# Sheet1.net
KiCad netlist of a schematic drawn in Altium Designer
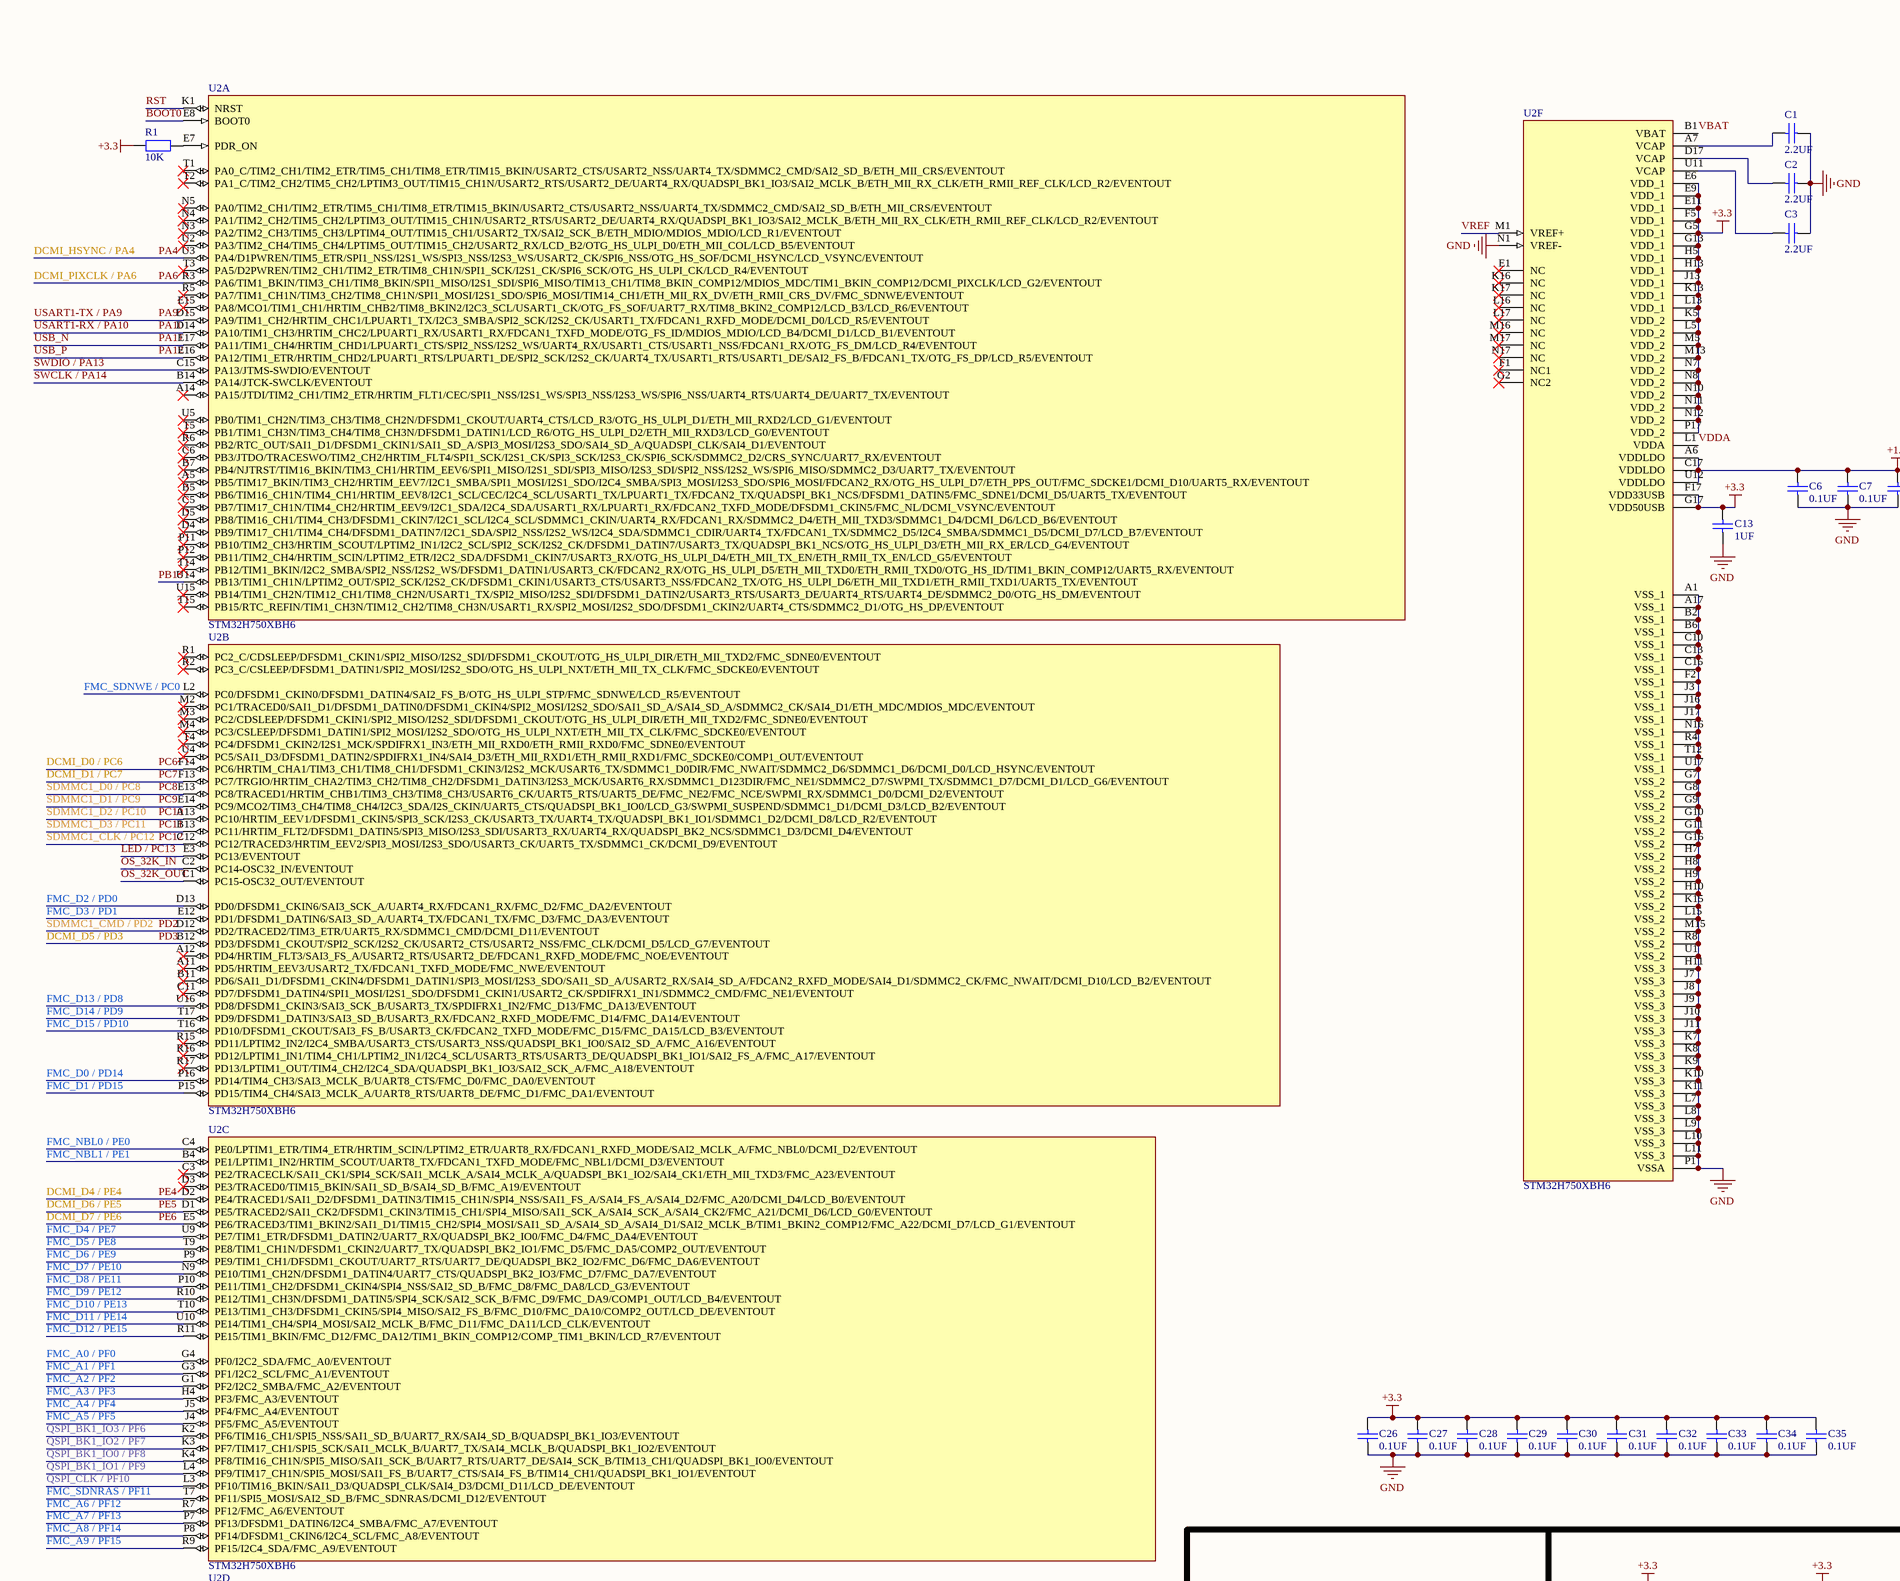
[diagram p0: Sheet1.SchDoc, top left]
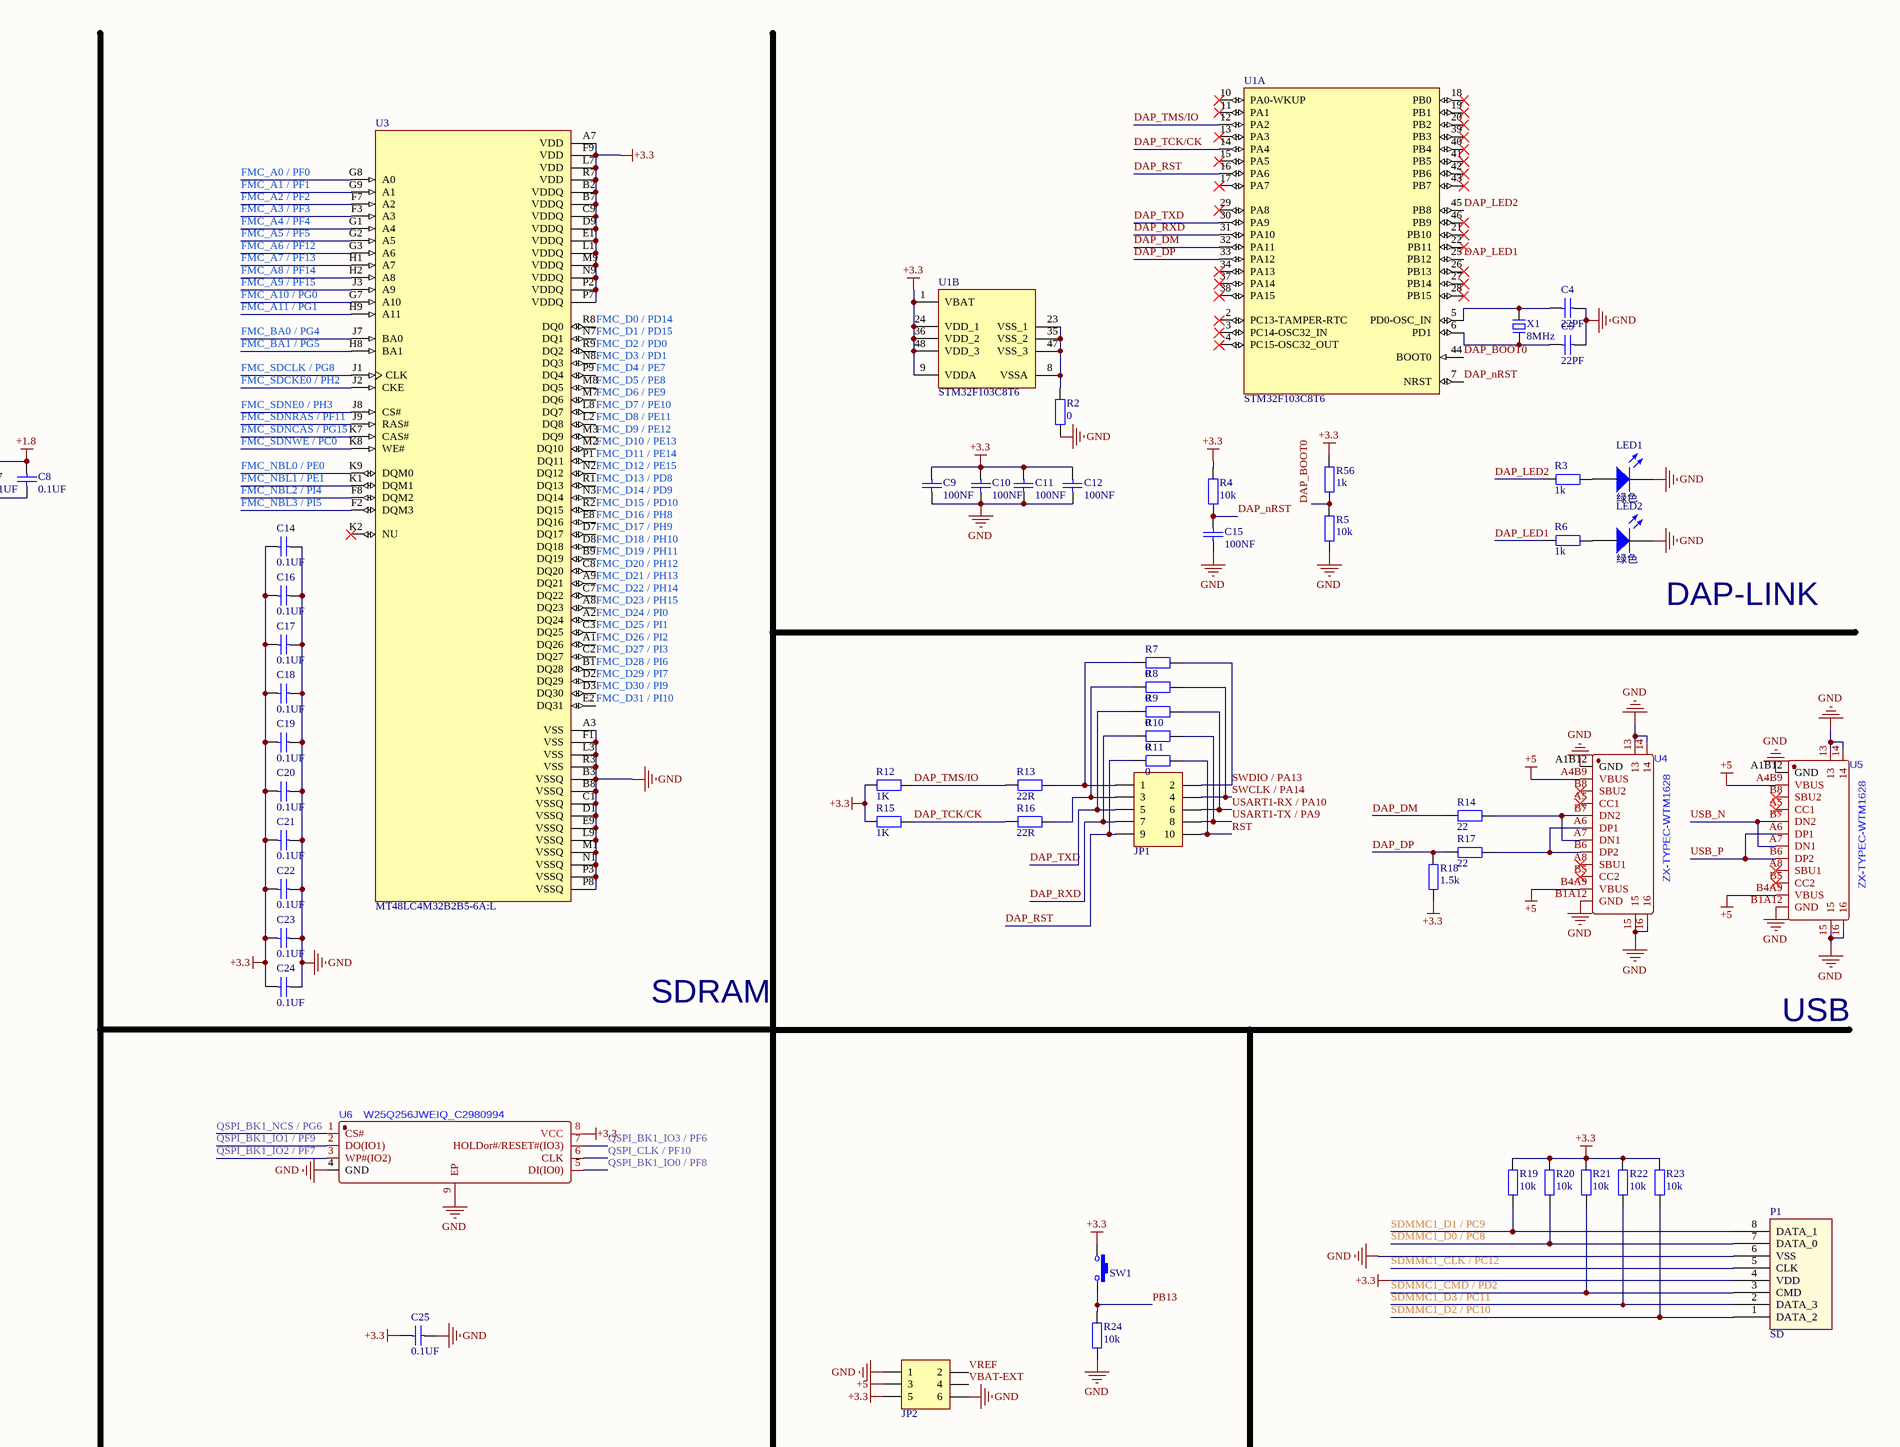
[diagram p1: Sheet1.SchDoc, top right]
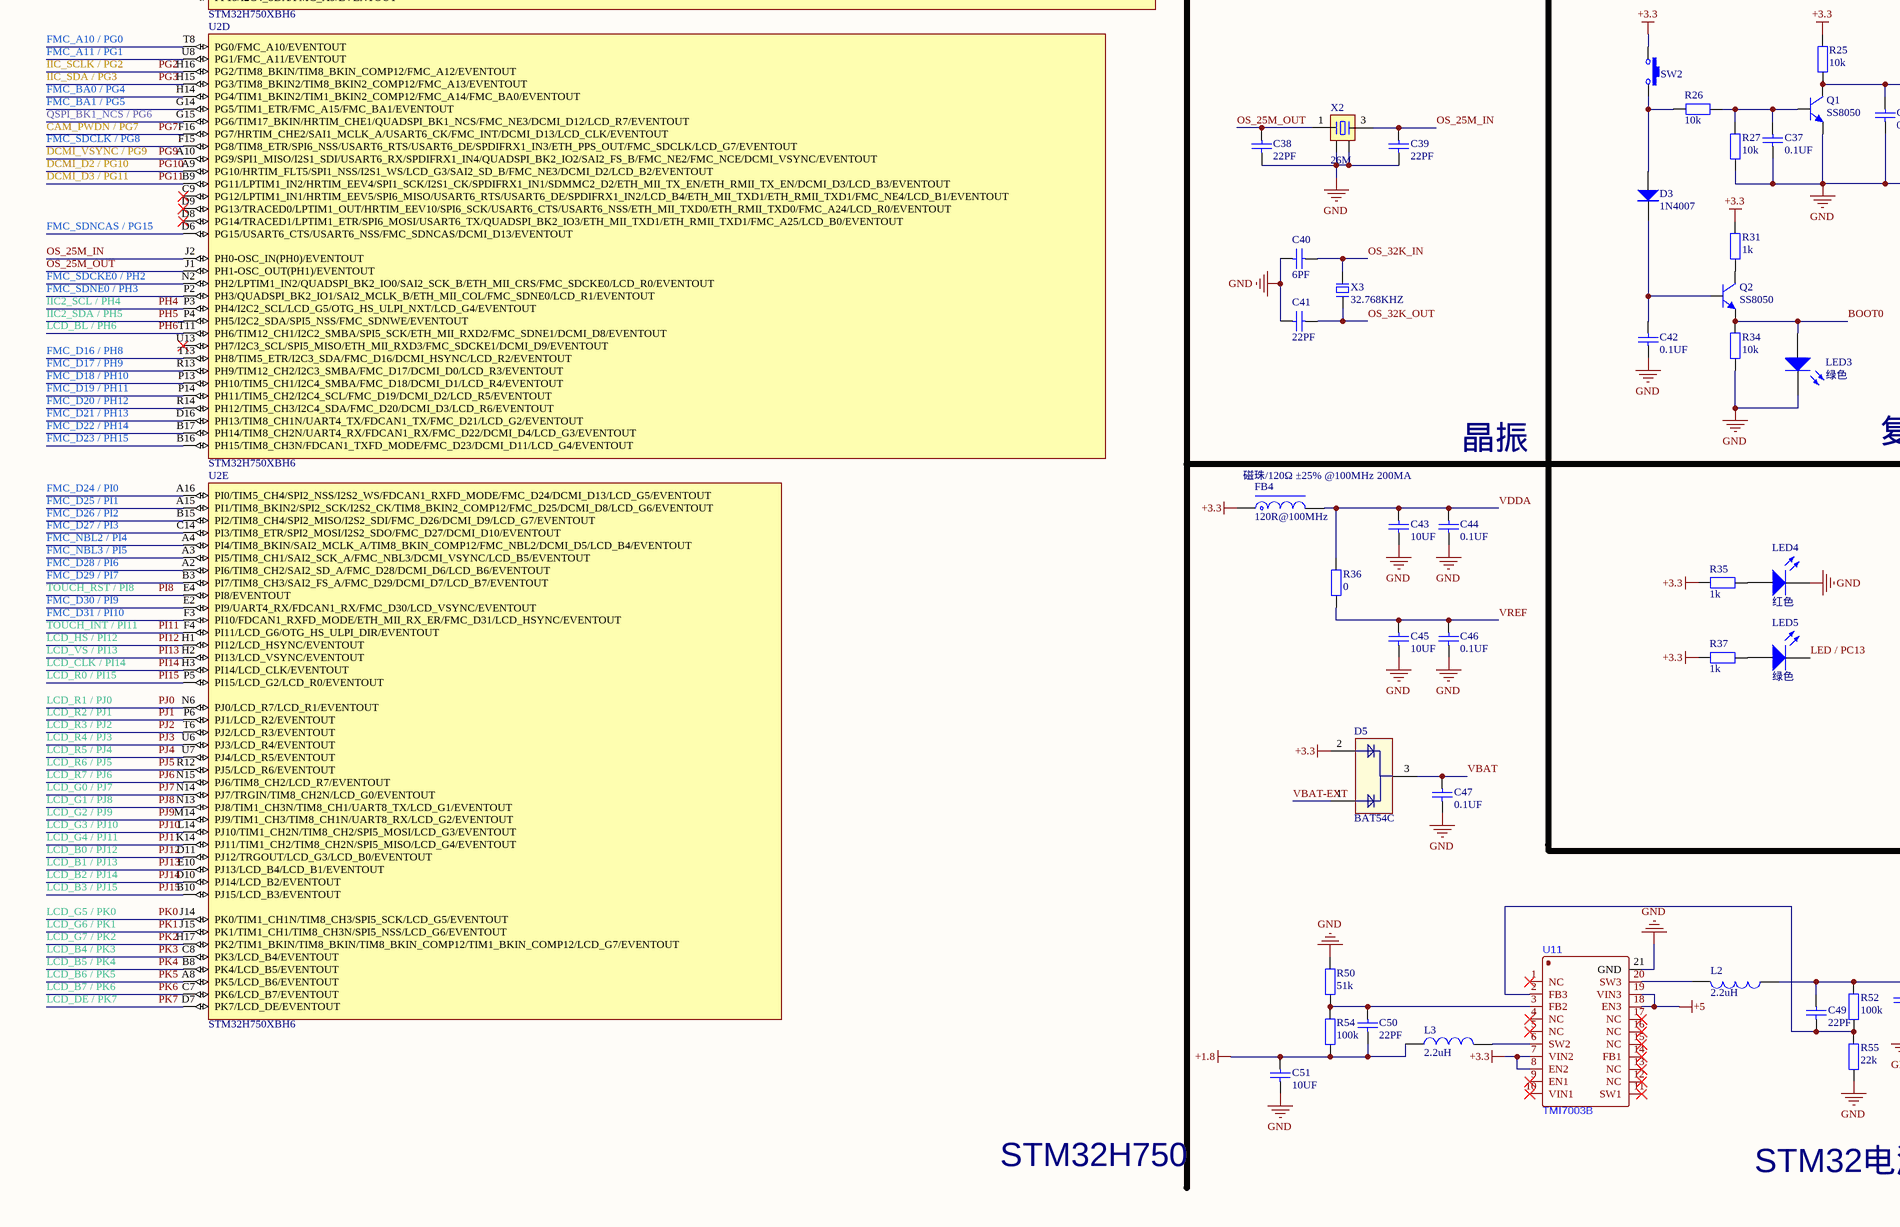
[diagram p2: Sheet1.SchDoc, bottom left]
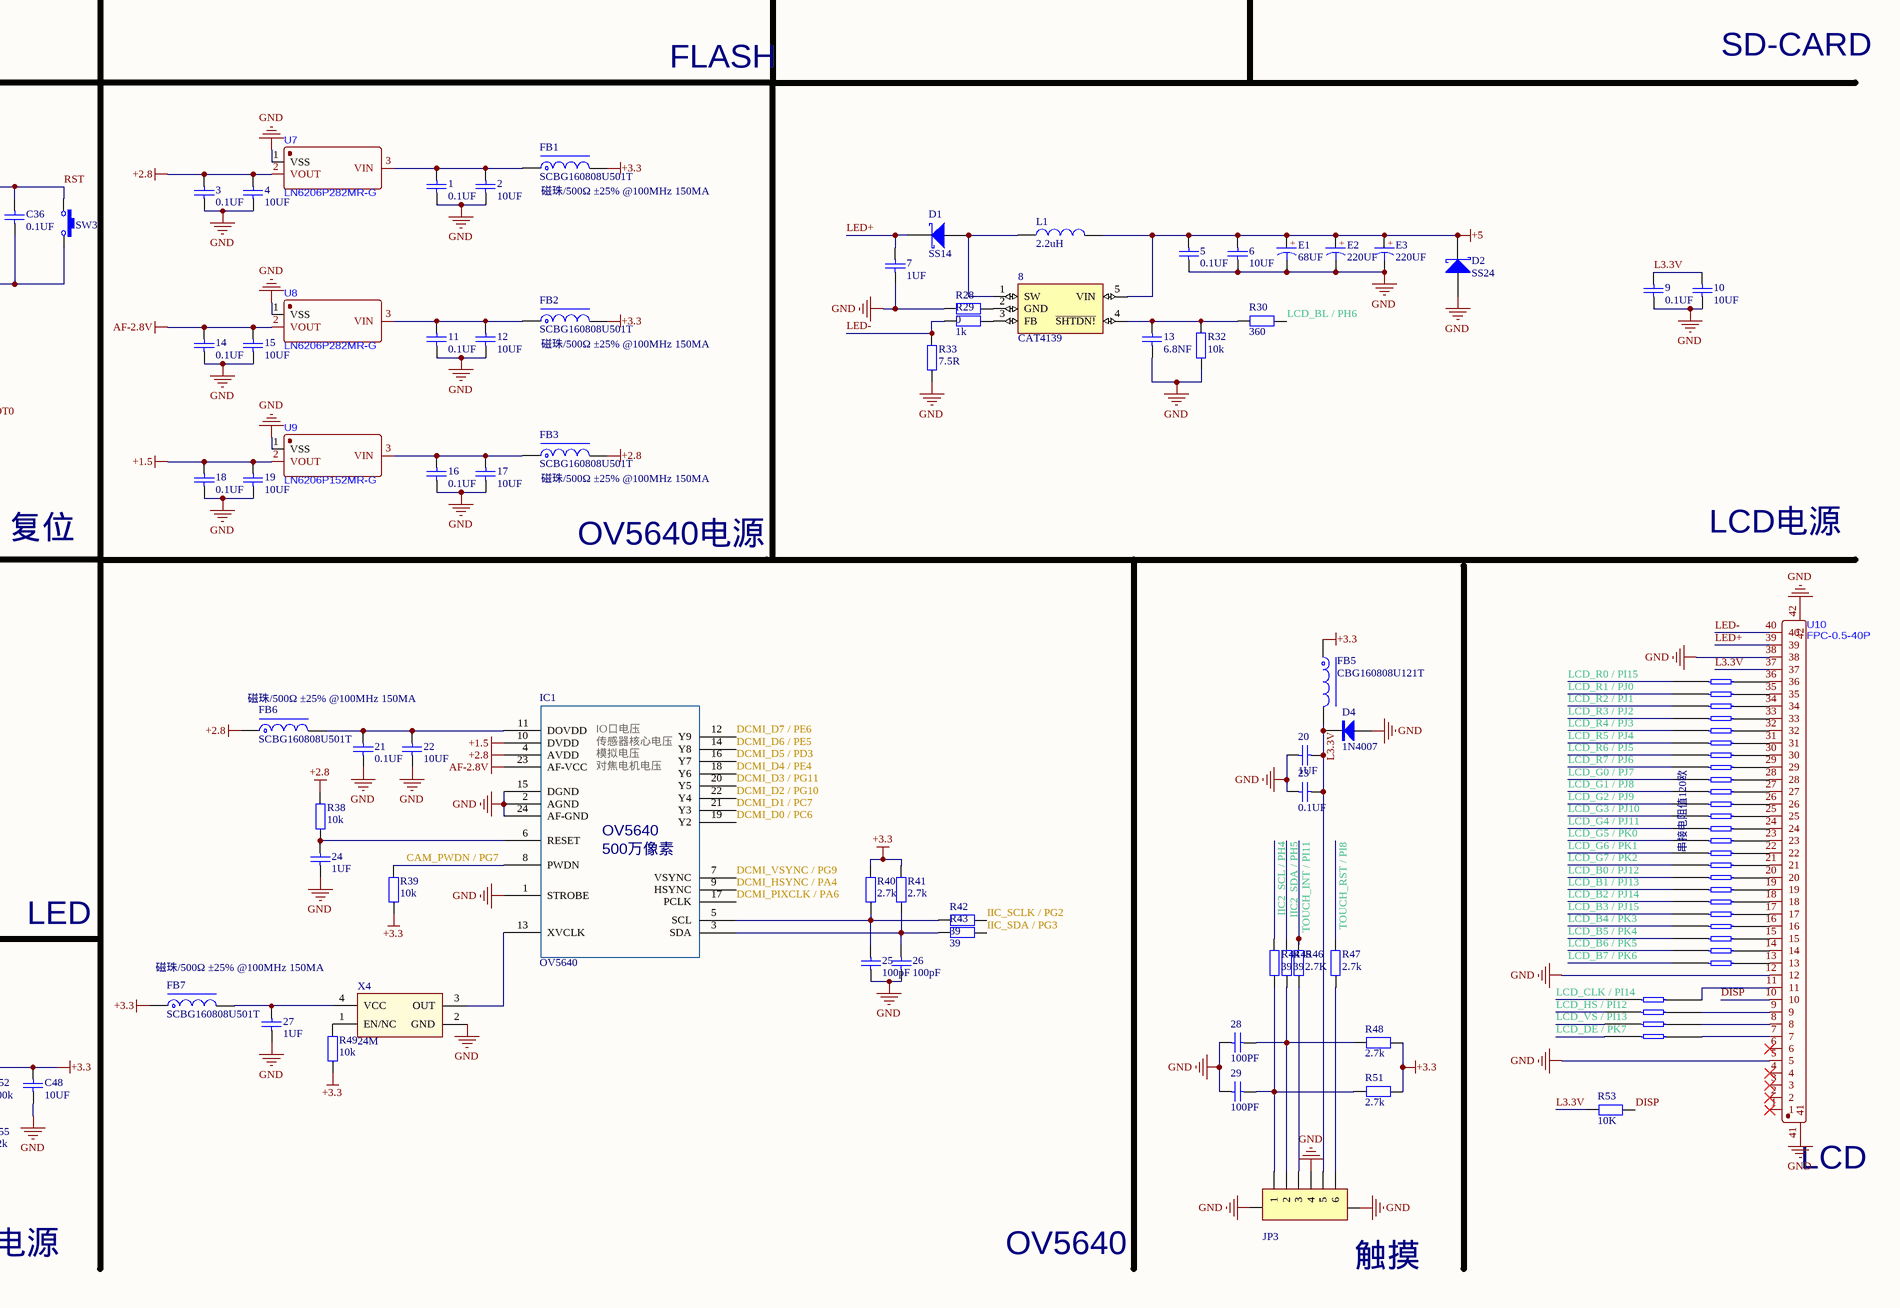
[diagram p3: Sheet1.SchDoc, bottom right]

(export (version "E")
  (design (tool "Eeschema 10.0.6"))
  (components
    (comp (ref "1")
      (value "0.1UF")
      (footprint "PCB1:C0603_L")
      (description "贴片电容/MLCC电容")
      (libsource (lib "屏幕一体板v2") (part "C"))
    )
    (comp (ref "2")
      (value "10UF")
      (footprint "PCB1:C0603_L")
      (description "贴片电容/MLCC电容")
      (libsource (lib "屏幕一体板v2") (part "C"))
    )
    (comp (ref "3")
      (value "0.1UF")
      (footprint "PCB1:C0603_L")
      (description "贴片电容/MLCC电容")
      (libsource (lib "屏幕一体板v2") (part "C"))
    )
    (comp (ref "4")
      (value "10UF")
      (footprint "PCB1:C0603_L")
      (description "贴片电容/MLCC电容")
      (libsource (lib "屏幕一体板v2") (part "C"))
    )
    (comp (ref "5")
      (value "0.1UF")
      (footprint "PCB1:C0603_L")
      (description "贴片电容/MLCC电容")
      (libsource (lib "屏幕一体板v2") (part "C"))
    )
    (comp (ref "6")
      (value "10UF")
      (footprint "PCB1:C0603_L")
      (description "贴片电容/MLCC电容")
      (libsource (lib "屏幕一体板v2") (part "C"))
    )
    (comp (ref "7")
      (value "1UF")
      (footprint "PCB1:C0603_L")
      (description "贴片电容/MLCC电容")
      (libsource (lib "屏幕一体板v2") (part "C"))
    )
    (comp (ref "8")
      (value "CAT4139")
      (footprint "PCB1:SOT-23(OT)5_LEAD")
      (libsource (lib "屏幕一体板v2") (part "CAT4139"))
    )
    (comp (ref "9")
      (value "0.1UF")
      (footprint "PCB1:C0603_L")
      (description "贴片电容/MLCC电容")
      (libsource (lib "屏幕一体板v2") (part "C"))
    )
    (comp (ref "10")
      (value "10UF")
      (footprint "PCB1:C0603_L")
      (description "贴片电容/MLCC电容")
      (libsource (lib "屏幕一体板v2") (part "C"))
    )
    (comp (ref "11")
      (value "0.1UF")
      (footprint "PCB1:C0603_L")
      (description "贴片电容/MLCC电容")
      (libsource (lib "屏幕一体板v2") (part "C"))
    )
    (comp (ref "12")
      (value "10UF")
      (footprint "PCB1:C0603_L")
      (description "贴片电容/MLCC电容")
      (libsource (lib "屏幕一体板v2") (part "C"))
    )
    (comp (ref "13")
      (value "6.8NF")
      (footprint "PCB1:C0603_L")
      (description "贴片电容/MLCC电容")
      (libsource (lib "屏幕一体板v2") (part "C"))
    )
    (comp (ref "14")
      (value "0.1UF")
      (footprint "PCB1:C0603_L")
      (description "贴片电容/MLCC电容")
      (libsource (lib "屏幕一体板v2") (part "C"))
    )
    (comp (ref "15")
      (value "10UF")
      (footprint "PCB1:C0603_L")
      (description "贴片电容/MLCC电容")
      (libsource (lib "屏幕一体板v2") (part "C"))
    )
    (comp (ref "16")
      (value "0.1UF")
      (footprint "PCB1:C0603_L")
      (description "贴片电容/MLCC电容")
      (libsource (lib "屏幕一体板v2") (part "C"))
    )
    (comp (ref "17")
      (value "10UF")
      (footprint "PCB1:C0603_L")
      (description "贴片电容/MLCC电容")
      (libsource (lib "屏幕一体板v2") (part "C"))
    )
    (comp (ref "18")
      (value "0.1UF")
      (footprint "PCB1:C0603_L")
      (description "贴片电容/MLCC电容")
      (libsource (lib "屏幕一体板v2") (part "C"))
    )
    (comp (ref "19")
      (value "10UF")
      (footprint "PCB1:C0603_L")
      (description "贴片电容/MLCC电容")
      (libsource (lib "屏幕一体板v2") (part "C"))
    )
    (comp (ref "20")
      (value "1UF")
      (footprint "PCB1:C0603_L")
      (description "贴片电容/MLCC电容")
      (libsource (lib "屏幕一体板v2") (part "C"))
    )
    (comp (ref "21")
      (value "0.1UF")
      (footprint "PCB1:C0603_L")
      (description "贴片电容/MLCC电容")
      (libsource (lib "屏幕一体板v2") (part "C"))
    )
    (comp (ref "22")
      (value "10UF")
      (footprint "PCB1:C0603_L")
      (description "贴片电容/MLCC电容")
      (libsource (lib "屏幕一体板v2") (part "C"))
    )
    (comp (ref "23")
      (value "0.1UF")
      (footprint "PCB1:C0603_L")
      (description "贴片电容/MLCC电容")
      (libsource (lib "屏幕一体板v2") (part "C"))
    )
    (comp (ref "24")
      (value "1UF")
      (footprint "PCB1:C0603_L")
      (description "贴片电容/MLCC电容")
      (libsource (lib "屏幕一体板v2") (part "C"))
    )
    (comp (ref "25")
      (value "100pF")
      (footprint "PCB1:C0603_L")
      (description "贴片电容/MLCC电容")
      (libsource (lib "屏幕一体板v2") (part "C"))
    )
    (comp (ref "26")
      (value "100pF")
      (footprint "PCB1:C0603_L")
      (description "贴片电容/MLCC电容")
      (libsource (lib "屏幕一体板v2") (part "C"))
    )
    (comp (ref "27")
      (value "1UF")
      (footprint "PCB1:C0603_L")
      (description "贴片电容/MLCC电容")
      (libsource (lib "屏幕一体板v2") (part "C"))
    )
    (comp (ref "28")
      (value "100PF")
      (footprint "PCB1:C0603_L")
      (description "贴片电容/MLCC电容")
      (libsource (lib "屏幕一体板v2") (part "C"))
    )
    (comp (ref "29")
      (value "100PF")
      (footprint "PCB1:C0603_L")
      (description "贴片电容/MLCC电容")
      (libsource (lib "屏幕一体板v2") (part "C"))
    )
    (comp (ref "C1")
      (value "2.2UF")
      (footprint "PCB1:C0603_L")
      (description "贴片电容/MLCC电容")
      (libsource (lib "屏幕一体板v2") (part "C"))
    )
    (comp (ref "C2")
      (value "2.2UF")
      (footprint "PCB1:C0603_L")
      (description "贴片电容/MLCC电容")
      (libsource (lib "屏幕一体板v2") (part "C"))
    )
    (comp (ref "C3")
      (value "2.2UF")
      (footprint "PCB1:C0603_L")
      (description "贴片电容/MLCC电容")
      (libsource (lib "屏幕一体板v2") (part "C"))
    )
    (comp (ref "C4")
      (value "22PF")
      (footprint "PCB1:C0603_L")
      (description "贴片电容/MLCC电容")
      (libsource (lib "屏幕一体板v2") (part "C"))
    )
    (comp (ref "C5")
      (value "22PF")
      (footprint "PCB1:C0603_L")
      (description "贴片电容/MLCC电容")
      (libsource (lib "屏幕一体板v2") (part "C"))
    )
    (comp (ref "C6")
      (value "0.1UF")
      (footprint "PCB1:C0603_L")
      (description "贴片电容/MLCC电容")
      (libsource (lib "屏幕一体板v2") (part "C"))
    )
    (comp (ref "C7")
      (value "0.1UF")
      (footprint "PCB1:C0603_L")
      (description "贴片电容/MLCC电容")
      (libsource (lib "屏幕一体板v2") (part "C"))
    )
    (comp (ref "C8")
      (value "0.1UF")
      (footprint "PCB1:C0603_L")
      (description "贴片电容/MLCC电容")
      (libsource (lib "屏幕一体板v2") (part "C"))
    )
    (comp (ref "C9")
      (value "100NF")
      (footprint "PCB1:C0603_L")
      (description "贴片电容/MLCC电容")
      (libsource (lib "屏幕一体板v2") (part "C"))
    )
    (comp (ref "C10")
      (value "100NF")
      (footprint "PCB1:C0603_L")
      (description "贴片电容/MLCC电容")
      (libsource (lib "屏幕一体板v2") (part "C"))
    )
    (comp (ref "C11")
      (value "100NF")
      (footprint "PCB1:C0603_L")
      (description "贴片电容/MLCC电容")
      (libsource (lib "屏幕一体板v2") (part "C"))
    )
    (comp (ref "C12")
      (value "100NF")
      (footprint "PCB1:C0603_L")
      (description "贴片电容/MLCC电容")
      (libsource (lib "屏幕一体板v2") (part "C"))
    )
    (comp (ref "C13")
      (value "1UF")
      (footprint "PCB1:C0603_L")
      (description "贴片电容/MLCC电容")
      (libsource (lib "屏幕一体板v2") (part "C"))
    )
    (comp (ref "C14")
      (value "0.1UF")
      (footprint "PCB1:C0402_M")
      (description "贴片电容/MLCC电容")
      (libsource (lib "屏幕一体板v2") (part "C"))
    )
    (comp (ref "C15")
      (value "100NF")
      (footprint "PCB1:C0603_L")
      (description "贴片电容/MLCC电容")
      (libsource (lib "屏幕一体板v2") (part "C"))
    )
    (comp (ref "C16")
      (value "0.1UF")
      (footprint "PCB1:C0402_M")
      (description "贴片电容/MLCC电容")
      (libsource (lib "屏幕一体板v2") (part "C"))
    )
    (comp (ref "C17")
      (value "0.1UF")
      (footprint "PCB1:C0402_M")
      (description "贴片电容/MLCC电容")
      (libsource (lib "屏幕一体板v2") (part "C"))
    )
    (comp (ref "C18")
      (value "0.1UF")
      (footprint "PCB1:C0402_M")
      (description "贴片电容/MLCC电容")
      (libsource (lib "屏幕一体板v2") (part "C"))
    )
    (comp (ref "C19")
      (value "0.1UF")
      (footprint "PCB1:C0402_M")
      (description "贴片电容/MLCC电容")
      (libsource (lib "屏幕一体板v2") (part "C"))
    )
    (comp (ref "C20")
      (value "0.1UF")
      (footprint "PCB1:C0402_M")
      (description "贴片电容/MLCC电容")
      (libsource (lib "屏幕一体板v2") (part "C"))
    )
    (comp (ref "C21")
      (value "0.1UF")
      (footprint "PCB1:C0402_M")
      (description "贴片电容/MLCC电容")
      (libsource (lib "屏幕一体板v2") (part "C"))
    )
    (comp (ref "C22")
      (value "0.1UF")
      (footprint "PCB1:C0402_M")
      (description "贴片电容/MLCC电容")
      (libsource (lib "屏幕一体板v2") (part "C"))
    )
    (comp (ref "C23")
      (value "0.1UF")
      (footprint "PCB1:C0402_M")
      (description "贴片电容/MLCC电容")
      (libsource (lib "屏幕一体板v2") (part "C"))
    )
    (comp (ref "C24")
      (value "0.1UF")
      (footprint "PCB1:C0402_M")
      (description "贴片电容/MLCC电容")
      (libsource (lib "屏幕一体板v2") (part "C"))
    )
    (comp (ref "C25")
      (value "0.1UF")
      (footprint "PCB1:C0603_L")
      (description "贴片电容/MLCC电容")
      (libsource (lib "屏幕一体板v2") (part "C"))
    )
    (comp (ref "C26")
      (value "0.1UF")
      (footprint "PCB1:C0402_M")
      (description "贴片电容/MLCC电容")
      (libsource (lib "屏幕一体板v2") (part "C"))
    )
    (comp (ref "C27")
      (value "0.1UF")
      (footprint "PCB1:C0402_M")
      (description "贴片电容/MLCC电容")
      (libsource (lib "屏幕一体板v2") (part "C"))
    )
    (comp (ref "C28")
      (value "0.1UF")
      (footprint "PCB1:C0603_L")
      (description "贴片电容/MLCC电容")
      (libsource (lib "屏幕一体板v2") (part "C"))
    )
    (comp (ref "C29")
      (value "0.1UF")
      (footprint "PCB1:C0402_M")
      (description "贴片电容/MLCC电容")
      (libsource (lib "屏幕一体板v2") (part "C"))
    )
    (comp (ref "C30")
      (value "0.1UF")
      (footprint "PCB1:C0402_M")
      (description "贴片电容/MLCC电容")
      (libsource (lib "屏幕一体板v2") (part "C"))
    )
    (comp (ref "C31")
      (value "0.1UF")
      (footprint "PCB1:C0402_M")
      (description "贴片电容/MLCC电容")
      (libsource (lib "屏幕一体板v2") (part "C"))
    )
    (comp (ref "C32")
      (value "0.1UF")
      (footprint "PCB1:C0402_M")
      (description "贴片电容/MLCC电容")
      (libsource (lib "屏幕一体板v2") (part "C"))
    )
    (comp (ref "C33")
      (value "0.1UF")
      (footprint "PCB1:C0402_M")
      (description "贴片电容/MLCC电容")
      (libsource (lib "屏幕一体板v2") (part "C"))
    )
    (comp (ref "C34")
      (value "0.1UF")
      (footprint "PCB1:C0402_M")
      (description "贴片电容/MLCC电容")
      (libsource (lib "屏幕一体板v2") (part "C"))
    )
    (comp (ref "C35")
      (value "0.1UF")
      (footprint "PCB1:C0402_M")
      (description "贴片电容/MLCC电容")
      (libsource (lib "屏幕一体板v2") (part "C"))
    )
    (comp (ref "C36")
      (value "0.1UF")
      (footprint "PCB1:C0603_L")
      (description "贴片电容/MLCC电容")
      (libsource (lib "屏幕一体板v2") (part "C"))
    )
    (comp (ref "C37")
      (value "0.1UF")
      (footprint "PCB1:C0603_L")
      (description "贴片电容/MLCC电容")
      (libsource (lib "屏幕一体板v2") (part "C"))
    )
    (comp (ref "C38")
      (value "22PF")
      (footprint "PCB1:C0603_L")
      (description "贴片电容/MLCC电容")
      (libsource (lib "屏幕一体板v2") (part "C"))
    )
    (comp (ref "C39")
      (value "22PF")
      (footprint "PCB1:C0603_L")
      (description "贴片电容/MLCC电容")
      (libsource (lib "屏幕一体板v2") (part "C"))
    )
    (comp (ref "C40")
      (value "6PF")
      (footprint "PCB1:C0603_L")
      (description "贴片电容/MLCC电容")
      (libsource (lib "屏幕一体板v2") (part "C"))
    )
    (comp (ref "C41")
      (value "22PF")
      (footprint "PCB1:C0603_L")
      (description "贴片电容/MLCC电容")
      (libsource (lib "屏幕一体板v2") (part "C"))
    )
    (comp (ref "C42")
      (value "0.1UF")
      (footprint "PCB1:C0603_L")
      (description "贴片电容/MLCC电容")
      (libsource (lib "屏幕一体板v2") (part "C"))
    )
    (comp (ref "C43")
      (value "10UF")
      (footprint "PCB1:C0603_L")
      (description "贴片电容/MLCC电容")
      (libsource (lib "屏幕一体板v2") (part "C"))
    )
    (comp (ref "C44")
      (value "0.1UF")
      (footprint "PCB1:C0603_L")
      (description "贴片电容/MLCC电容")
      (libsource (lib "屏幕一体板v2") (part "C"))
    )
    (comp (ref "C45")
      (value "10UF")
      (footprint "PCB1:C0603_L")
      (description "贴片电容/MLCC电容")
      (libsource (lib "屏幕一体板v2") (part "C"))
    )
    (comp (ref "C46")
      (value "0.1UF")
      (footprint "PCB1:C0603_L")
      (description "贴片电容/MLCC电容")
      (libsource (lib "屏幕一体板v2") (part "C"))
    )
    (comp (ref "C47")
      (value "0.1UF")
      (footprint "PCB1:C0603_L")
      (description "贴片电容/MLCC电容")
      (libsource (lib "屏幕一体板v2") (part "C"))
    )
    (comp (ref "C48")
      (value "10UF")
      (footprint "PCB1:C0603_L")
      (description "贴片电容/MLCC电容")
      (libsource (lib "屏幕一体板v2") (part "C"))
    )
    (comp (ref "C49")
      (value "22PF")
      (footprint "PCB1:C0603_L")
      (description "贴片电容/MLCC电容")
      (libsource (lib "屏幕一体板v2") (part "C"))
    )
    (comp (ref "C50")
      (value "22PF")
      (footprint "PCB1:C0603_L")
      (description "贴片电容/MLCC电容")
      (libsource (lib "屏幕一体板v2") (part "C"))
    )
    (comp (ref "C51")
      (value "10UF")
      (footprint "PCB1:C0603_L")
      (description "贴片电容/MLCC电容")
      (libsource (lib "屏幕一体板v2") (part "C"))
    )
    (comp (ref "D1")
      (value "SS14")
      (footprint "PCB1:SMA")
      (description "肖特基二极管")
      (libsource (lib "屏幕一体板v2") (part "SS14"))
    )
    (comp (ref "D2")
      (value "SS24")
      (footprint "PCB1:SMA")
      (description "肖特基二极管")
      (libsource (lib "屏幕一体板v2") (part "SS14"))
    )
    (comp (ref "D3")
      (value "1N4007")
      (footprint "PCB1:SMA")
      (description "整流二极管")
      (libsource (lib "屏幕一体板v2") (part "1N4007"))
    )
    (comp (ref "D4")
      (value "1N4007")
      (footprint "PCB1:SMA")
      (description "整流二极管")
      (libsource (lib "屏幕一体板v2") (part "1N4007"))
    )
    (comp (ref "D5")
      (value "BAT54C")
      (footprint "PCB1:SOT23-3N")
      (description "两路肖特基二极管")
      (libsource (lib "屏幕一体板v2") (part "BAT54C"))
    )
    (comp (ref "E1")
      (value "68UF")
      (footprint "PCB1:CE A(3*5.4)")
      (description "贴片电解电容")
      (libsource (lib "屏幕一体板v2") (part "CE_SMD"))
    )
    (comp (ref "E2")
      (value "220UF")
      (footprint "PCB1:CE A(3*5.4)")
      (description "贴片电解电容")
      (libsource (lib "屏幕一体板v2") (part "CE_SMD"))
    )
    (comp (ref "E3")
      (value "220UF")
      (footprint "PCB1:CE A(3*5.4)")
      (description "贴片电解电容")
      (libsource (lib "屏幕一体板v2") (part "CE_SMD"))
    )
    (comp (ref "FB1")
      (value "SCBG160808U501T")
      (footprint "PCB1:FB0603")
      (description "贴片磁珠")
      (libsource (lib "屏幕一体板v2") (part "FB"))
    )
    (comp (ref "FB2")
      (value "SCBG160808U501T")
      (footprint "PCB1:FB0603")
      (description "贴片磁珠")
      (libsource (lib "屏幕一体板v2") (part "FB"))
    )
    (comp (ref "FB3")
      (value "SCBG160808U501T")
      (footprint "PCB1:FB0603")
      (description "贴片磁珠")
      (libsource (lib "屏幕一体板v2") (part "FB"))
    )
    (comp (ref "FB4")
      (value "120R@100MHz")
      (footprint "PCB1:FB0603")
      (description "贴片磁珠")
      (libsource (lib "屏幕一体板v2") (part "FB"))
    )
    (comp (ref "FB5")
      (value "CBG160808U121T")
      (footprint "PCB1:FB0805")
      (description "贴片磁珠")
      (libsource (lib "") (part "FB_1"))
    )
    (comp (ref "FB6")
      (value "SCBG160808U501T")
      (footprint "PCB1:FB0603")
      (description "贴片磁珠")
      (libsource (lib "屏幕一体板v2") (part "FB"))
    )
    (comp (ref "FB7")
      (value "SCBG160808U501T")
      (footprint "PCB1:FB0603")
      (description "贴片磁珠")
      (libsource (lib "屏幕一体板v2") (part "FB"))
    )
    (comp (ref "IC1") (value "OV5640") (footprint "PCB1:OV2640") (libsource (lib "屏幕一体板v2") (part "OV5640")))
    (comp (ref "JP1")
      (value "Header 5X2")
      (footprint "PCB1:HDR2.54-M-LS-2x5P")
      (description "5*2P接插件")
      (libsource (lib "屏幕一体板v2") (part "Header 5X2"))
    )
    (comp (ref "JP2")
      (value "Header3X2")
      (footprint "PCB1:HDR2.54-M-LS-2x3P")
      (description "3*2P接插件")
      (libsource (lib "屏幕一体板v2") (part "Header 3X2"))
    )
    (comp (ref "JP3")
      (value "CON-6P")
      (footprint "PCB1:FPC0.5-WT-6P")
      (description "6P连接器")
      (libsource (lib "屏幕一体板v2") (part "Header 6"))
    )
    (comp (ref "L1")
      (value "2.2uH")
      (footprint "PCB1:L0805")
      (description "贴片小功率电感")
      (libsource (lib "屏幕一体板v2") (part "L"))
    )
    (comp (ref "L2")
      (value "2.2uH")
      (footprint "PCB1:L0805")
      (description "贴片小功率电感")
      (libsource (lib "屏幕一体板v2") (part "L"))
    )
    (comp (ref "L3")
      (value "2.2uH")
      (footprint "PCB1:L0805")
      (description "贴片小功率电感")
      (libsource (lib "屏幕一体板v2") (part "L"))
    )
    (comp (ref "LED1")
      (value "绿色")
      (footprint "PCB1:LED0805_G")
      (description "贴片LED")
      (libsource (lib "屏幕一体板v2") (part "LED"))
    )
    (comp (ref "LED2")
      (value "绿色")
      (footprint "PCB1:LED0805_G")
      (description "贴片LED")
      (libsource (lib "屏幕一体板v2") (part "LED"))
    )
    (comp (ref "LED3")
      (value "绿色")
      (footprint "PCB1:LED0805_G")
      (description "贴片LED")
      (libsource (lib "屏幕一体板v2") (part "LED"))
    )
    (comp (ref "LED4")
      (value "红色")
      (footprint "PCB1:LED0603_R")
      (description "贴片LED")
      (libsource (lib "屏幕一体板v2") (part "LED"))
    )
    (comp (ref "LED5")
      (value "绿色")
      (footprint "PCB1:LED0805_G")
      (description "贴片LED")
      (libsource (lib "屏幕一体板v2") (part "LED"))
    )
    (comp (ref "P1")
      (value "SD")
      (footprint "PCB1:MICRO SD")
      (description "自弹式TF卡座")
      (libsource (lib "屏幕一体板v2") (part "Micro SD_SD"))
    )
    (comp (ref "Q1")
      (value "SS8050")
      (footprint "PCB1:SOT23-3N")
      (description "高频放大-NPN型")
      (libsource (lib "屏幕一体板v2") (part "8050-SMD"))
    )
    (comp (ref "Q2")
      (value "SS8050")
      (footprint "PCB1:SOT23-3N")
      (description "高频放大-NPN型")
      (libsource (lib "屏幕一体板v2") (part "8050-SMD"))
    )
    (comp (ref "R1")
      (value "10K")
      (footprint "PCB1:R0603_L")
      (description "贴片电阻")
      (libsource (lib "屏幕一体板v2") (part "R"))
    )
    (comp (ref "R2")
      (value "0")
      (footprint "PCB1:R0603_L")
      (description "贴片电阻")
      (libsource (lib "屏幕一体板v2") (part "R"))
    )
    (comp (ref "R3")
      (value "1k")
      (footprint "PCB1:R0603_L")
      (description "贴片电阻")
      (libsource (lib "屏幕一体板v2") (part "R"))
    )
    (comp (ref "R4")
      (value "10k")
      (footprint "PCB1:R0603_L")
      (description "贴片电阻")
      (libsource (lib "屏幕一体板v2") (part "R"))
    )
    (comp (ref "R5")
      (value "10k")
      (footprint "PCB1:R0603_L")
      (description "贴片电阻")
      (libsource (lib "屏幕一体板v2") (part "R"))
    )
    (comp (ref "R6")
      (value "1k")
      (footprint "PCB1:R0603_L")
      (description "贴片电阻")
      (libsource (lib "屏幕一体板v2") (part "R"))
    )
    (comp (ref "R7")
      (value "0")
      (footprint "PCB1:R0603_L")
      (description "贴片电阻")
      (libsource (lib "屏幕一体板v2") (part "R"))
    )
    (comp (ref "R8")
      (value "0")
      (footprint "PCB1:R0603_L")
      (description "贴片电阻")
      (libsource (lib "屏幕一体板v2") (part "R"))
    )
    (comp (ref "R9")
      (value "0")
      (footprint "PCB1:R0603_L")
      (description "贴片电阻")
      (libsource (lib "屏幕一体板v2") (part "R"))
    )
    (comp (ref "R10")
      (value "0")
      (footprint "PCB1:R0603_L")
      (description "贴片电阻")
      (libsource (lib "屏幕一体板v2") (part "R"))
    )
    (comp (ref "R11")
      (value "0")
      (footprint "PCB1:R0603_L")
      (description "贴片电阻")
      (libsource (lib "屏幕一体板v2") (part "R"))
    )
    (comp (ref "R12")
      (value "1K")
      (footprint "PCB1:R0805_L")
      (description "贴片电阻")
      (libsource (lib "屏幕一体板v2") (part "R"))
    )
    (comp (ref "R13")
      (value "22R")
      (footprint "PCB1:R0805_L")
      (description "贴片电阻")
      (libsource (lib "屏幕一体板v2") (part "R"))
    )
    (comp (ref "R14")
      (value "22")
      (footprint "PCB1:R0603_L")
      (description "贴片电阻")
      (libsource (lib "屏幕一体板v2") (part "R"))
    )
    (comp (ref "R15")
      (value "1K")
      (footprint "PCB1:R0805_L")
      (description "贴片电阻")
      (libsource (lib "屏幕一体板v2") (part "R"))
    )
    (comp (ref "R16")
      (value "22R")
      (footprint "PCB1:R0805_L")
      (description "贴片电阻")
      (libsource (lib "屏幕一体板v2") (part "R"))
    )
    (comp (ref "R17")
      (value "22")
      (footprint "PCB1:R0603_L")
      (description "贴片电阻")
      (libsource (lib "屏幕一体板v2") (part "R"))
    )
    (comp (ref "R18")
      (value "1.5k")
      (footprint "PCB1:R0603_L")
      (description "贴片电阻")
      (libsource (lib "屏幕一体板v2") (part "R"))
    )
    (comp (ref "R19")
      (value "10k")
      (footprint "PCB1:R0603_L")
      (description "贴片电阻")
      (libsource (lib "屏幕一体板v2") (part "R"))
    )
    (comp (ref "R20")
      (value "10k")
      (footprint "PCB1:R0603_L")
      (description "贴片电阻")
      (libsource (lib "屏幕一体板v2") (part "R"))
    )
    (comp (ref "R21")
      (value "10k")
      (footprint "PCB1:R0603_L")
      (description "贴片电阻")
      (libsource (lib "屏幕一体板v2") (part "R"))
    )
    (comp (ref "R22")
      (value "10k")
      (footprint "PCB1:R0603_L")
      (description "贴片电阻")
      (libsource (lib "屏幕一体板v2") (part "R"))
    )
    (comp (ref "R23")
      (value "10k")
      (footprint "PCB1:R0603_L")
      (description "贴片电阻")
      (libsource (lib "屏幕一体板v2") (part "R"))
    )
    (comp (ref "R24")
      (value "10k")
      (footprint "PCB1:R0603_L")
      (description "贴片电阻")
      (libsource (lib "屏幕一体板v2") (part "R"))
    )
    (comp (ref "R25")
      (value "10k")
      (footprint "PCB1:R0603_L")
      (description "贴片电阻")
      (libsource (lib "屏幕一体板v2") (part "R"))
    )
    (comp (ref "R26")
      (value "10k")
      (footprint "PCB1:R0603_L")
      (description "贴片电阻")
      (libsource (lib "屏幕一体板v2") (part "R"))
    )
    (comp (ref "R27")
      (value "10k")
      (footprint "PCB1:R0603_L")
      (description "贴片电阻")
      (libsource (lib "屏幕一体板v2") (part "R"))
    )
    (comp (ref "R28")
      (value "0")
      (footprint "PCB1:R0603_L")
      (description "贴片电阻")
      (libsource (lib "屏幕一体板v2") (part "R"))
    )
    (comp (ref "R29")
      (value "1k")
      (footprint "PCB1:R0603_L")
      (description "贴片电阻")
      (libsource (lib "屏幕一体板v2") (part "R"))
    )
    (comp (ref "R30")
      (value "360")
      (footprint "PCB1:R0603_L")
      (description "贴片电阻")
      (libsource (lib "屏幕一体板v2") (part "R"))
    )
    (comp (ref "R31")
      (value "1k")
      (footprint "PCB1:R0603_L")
      (description "贴片电阻")
      (libsource (lib "屏幕一体板v2") (part "R"))
    )
    (comp (ref "R32")
      (value "10k")
      (footprint "PCB1:R0603_L")
      (description "贴片电阻")
      (libsource (lib "屏幕一体板v2") (part "R"))
    )
    (comp (ref "R33")
      (value "7.5R")
      (footprint "PCB1:R0603_L")
      (description "贴片电阻")
      (libsource (lib "屏幕一体板v2") (part "R"))
    )
    (comp (ref "R34")
      (value "10k")
      (footprint "PCB1:R0603_L")
      (description "贴片电阻")
      (libsource (lib "屏幕一体板v2") (part "R"))
    )
    (comp (ref "R35")
      (value "1k")
      (footprint "PCB1:R0603_L")
      (description "贴片电阻")
      (libsource (lib "屏幕一体板v2") (part "R"))
    )
    (comp (ref "R36")
      (value "0")
      (footprint "PCB1:R0603_L")
      (description "贴片电阻")
      (libsource (lib "屏幕一体板v2") (part "R"))
    )
    (comp (ref "R37")
      (value "1k")
      (footprint "PCB1:R0603_L")
      (description "贴片电阻")
      (libsource (lib "屏幕一体板v2") (part "R"))
    )
    (comp (ref "R38")
      (value "10k")
      (footprint "PCB1:R0603_L")
      (description "贴片电阻")
      (libsource (lib "屏幕一体板v2") (part "R"))
    )
    (comp (ref "R39")
      (value "10k")
      (footprint "PCB1:R0603_L")
      (description "贴片电阻")
      (libsource (lib "屏幕一体板v2") (part "R"))
    )
    (comp (ref "R40")
      (value "2.7k")
      (footprint "PCB1:R0603_L")
      (description "贴片电阻")
      (libsource (lib "屏幕一体板v2") (part "R"))
    )
    (comp (ref "R41")
      (value "2.7k")
      (footprint "PCB1:R0603_L")
      (description "贴片电阻")
      (libsource (lib "屏幕一体板v2") (part "R"))
    )
    (comp (ref "R42")
      (value "39")
      (footprint "PCB1:R0603_L")
      (description "贴片电阻")
      (libsource (lib "屏幕一体板v2") (part "R"))
    )
    (comp (ref "R43")
      (value "39")
      (footprint "PCB1:R0603_L")
      (description "贴片电阻")
      (libsource (lib "屏幕一体板v2") (part "R"))
    )
    (comp (ref "R44")
      (value "39")
      (footprint "PCB1:R0603_L")
      (description "贴片电阻")
      (libsource (lib "屏幕一体板v2") (part "R"))
    )
    (comp (ref "R45")
      (value "39")
      (footprint "PCB1:R0603_L")
      (description "贴片电阻")
      (libsource (lib "屏幕一体板v2") (part "R"))
    )
    (comp (ref "R46")
      (value "2.7K")
      (footprint "PCB1:R0603_L")
      (description "贴片电阻")
      (libsource (lib "屏幕一体板v2") (part "R"))
    )
    (comp (ref "R47")
      (value "2.7k")
      (footprint "PCB1:R0603_L")
      (description "贴片电阻")
      (libsource (lib "屏幕一体板v2") (part "R"))
    )
    (comp (ref "R48")
      (value "2.7k")
      (footprint "PCB1:R0603_L")
      (description "贴片电阻")
      (libsource (lib "屏幕一体板v2") (part "R"))
    )
    (comp (ref "R49")
      (value "10k")
      (footprint "PCB1:R0603_L")
      (description "贴片电阻")
      (libsource (lib "屏幕一体板v2") (part "R"))
    )
    (comp (ref "R50")
      (value "51k")
      (footprint "PCB1:R0603_L")
      (description "贴片电阻")
      (libsource (lib "屏幕一体板v2") (part "R"))
    )
    (comp (ref "R51")
      (value "2.7k")
      (footprint "PCB1:R0603_L")
      (description "贴片电阻")
      (libsource (lib "屏幕一体板v2") (part "R"))
    )
    (comp (ref "R52")
      (value "100k")
      (footprint "PCB1:R0603_L")
      (description "贴片电阻")
      (libsource (lib "屏幕一体板v2") (part "R"))
    )
    (comp (ref "R53")
      (value "10K")
      (footprint "PCB1:R0603_L")
      (description "贴片电阻")
      (libsource (lib "屏幕一体板v2") (part "R"))
    )
    (comp (ref "R54")
      (value "100k")
      (footprint "PCB1:R0603_L")
      (description "贴片电阻")
      (libsource (lib "屏幕一体板v2") (part "R"))
    )
    (comp (ref "R55")
      (value "22k")
      (footprint "PCB1:R0603_L")
      (description "贴片电阻")
      (libsource (lib "屏幕一体板v2") (part "R"))
    )
    (comp (ref "R56")
      (value "1k")
      (footprint "PCB1:R0603_L")
      (description "贴片电阻")
      (libsource (lib "屏幕一体板v2") (part "R"))
    )
    (comp (ref "RP1") (value "120R排阻") (footprint "PCB1:0603_4P") (libsource (lib "屏幕一体板v2") (part "RES_4P")))
    (comp (ref "RP2") (value "120R排阻") (footprint "PCB1:0603_4P") (libsource (lib "屏幕一体板v2") (part "RES_4P")))
    (comp (ref "RP3") (value "120R排阻") (footprint "PCB1:0603_4P") (libsource (lib "屏幕一体板v2") (part "RES_4P")))
    (comp (ref "RP4") (value "120R排阻") (footprint "PCB1:0603_4P") (libsource (lib "屏幕一体板v2") (part "RES_4P")))
    (comp (ref "RP5") (value "120R排阻") (footprint "PCB1:0603_4P") (libsource (lib "屏幕一体板v2") (part "RES_4P")))
    (comp (ref "RP6") (value "120R排阻") (footprint "PCB1:0603_4P") (libsource (lib "屏幕一体板v2") (part "RES_4P")))
    (comp (ref "RP7") (value "120R排阻") (footprint "PCB1:0603_4P") (libsource (lib "屏幕一体板v2") (part "RES_4P")))
    (comp (ref "SW1")
      (value "3x6x5")
      (footprint "PCB1:SW SMD-3*6*2.5")
      (description "3x6轻触开关")
      (libsource (lib "屏幕一体板v2") (part "SW 3x6"))
    )
    (comp (ref "SW2")
      (value "3x6x5")
      (footprint "PCB1:SW SMD-3*6*2.5")
      (description "3x6轻触开关")
      (libsource (lib "屏幕一体板v2") (part "SW 3x6"))
    )
    (comp (ref "SW3")
      (value "3x6x5")
      (footprint "PCB1:SW SMD-3*6*2.5")
      (description "3x6轻触开关")
      (libsource (lib "屏幕一体板v2") (part "SW 3x6"))
    )
    (comp (ref "U1")
      (value "STM32F103C8T6")
      (footprint "PCB1:LQFP48_N")
      (libsource (lib "屏幕一体板v2") (part "STM32F103C8T6"))
    )
    (comp (ref "U2")
      (value "STM32H750XBH6")
      (footprint "PCB1:IC_STM32H750XBH6")
      (libsource (lib "屏幕一体板v2") (part "STM32H750XBH6"))
    )
    (comp (ref "U3")
      (value "MT48LC4M32B2B5-6A:L")
      (footprint "PCB1:BGA90C80P9X15_800X1300X100N")
      (description "SDRAM Memory IC 128Mb _4M x 32_ Parallel 167MHz 5.4ns 90-VFBGA _8x13_")
      (libsource (lib "屏幕一体板v2") (part "MT48LC4M32B2B5-6A{colon}L"))
    )
    (comp (ref "U4")
      (value "ZX-TYPEC-WTM1628")
      (footprint "PCB1:USB-C-SMD_ZX-TYPEC-WTM1628")
      (libsource (lib "屏幕一体板v2") (part "ZX-TYPEC-WTM1628"))
    )
    (comp (ref "U5")
      (value "ZX-TYPEC-WTM1628")
      (footprint "PCB1:USB-C-SMD_ZX-TYPEC-WTM1628")
      (libsource (lib "屏幕一体板v2") (part "ZX-TYPEC-WTM1628"))
    )
    (comp (ref "U6")
      (value "W25Q256JWEIQ_C2980994")
      (footprint "PCB1:WSON-8_L8.0-W6.0-P1.27-TL-EP-1")
      (libsource (lib "屏幕一体板v2") (part "W25Q256JWEIQ_C2980994"))
    )
    (comp (ref "U7")
      (value "LN6206P282MR-G")
      (footprint "PCB1:SOT-23-3_L2.9-W1.3-P1.90-LS2.4-BR")
      (libsource (lib "屏幕一体板v2") (part "LN6206P282MR-G"))
    )
    (comp (ref "U8")
      (value "LN6206P282MR-G")
      (footprint "PCB1:SOT-23-3_L2.9-W1.3-P1.90-LS2.4-BR")
      (libsource (lib "屏幕一体板v2") (part "LN6206P282MR-G"))
    )
    (comp (ref "U9")
      (value "LN6206P152MR-G")
      (footprint "PCB1:SOT-23-3_L2.9-W1.3-P1.90-LS2.4-BR")
      (libsource (lib "屏幕一体板v2") (part "LN6206P282MR-G"))
    )
    (comp (ref "U10")
      (value "FPC-0.5-40P")
      (footprint "PCB1:CONN-SMD_FPC-0.5-40P")
      (libsource (lib "屏幕一体板v2") (part "FPC-0.5-40P"))
    )
    (comp (ref "U11")
      (value "TMI7003B")
      (footprint "PCB1:QFN-20_L3.0-W3.0-P0.40-BL-EP1.7")
      (libsource (lib "屏幕一体板v2") (part "TMI7003B"))
    )
    (comp (ref "X1")
      (value "8MHz")
      (footprint "PCB1:XTAL-3215-2P")
      (description "2脚无源晶振(谐振器）")
      (libsource (lib "屏幕一体板v2") (part "XTAL-2P"))
    )
    (comp (ref "X2")
      (value "26M")
      (footprint "PCB1:XTAL-3225-4P")
      (description "4脚无源晶振(谐振器）")
      (libsource (lib "屏幕一体板v2") (part "XTAL-4P"))
    )
    (comp (ref "X3")
      (value "32.768KHZ")
      (footprint "PCB1:XTAL-3215-2P")
      (description "2脚无源晶振(谐振器）")
      (libsource (lib "屏幕一体板v2") (part "XTAL-2P"))
    )
    (comp (ref "X4")
      (value "24M")
      (footprint "PCB1:OSC-3225-4P")
      (description "4脚有源晶振(振荡器)")
      (libsource (lib "屏幕一体板v2") (part "XTAL-ACT-4P"))
    )
  )
  (nets
    (net (code "1") (name "+1.5") (class "Default")
      (node (ref "18") (pin "2") (pinfunction "2_2") (pintype "passive"))
      (node (ref "19") (pin "2") (pinfunction "2_2") (pintype "passive"))
      (node (ref "IC1") (pin "10") (pinfunction "DVDD_10") (pintype "passive"))
      (node (ref "U9") (pin "2") (pinfunction "VOUT_2") (pintype "passive"))
    )
    (net (code "2") (name "+1.8") (class "Default")
      (node (ref "C50") (pin "2") (pinfunction "2_2") (pintype "passive"))
      (node (ref "C51") (pin "1") (pinfunction "1_1") (pintype "passive"))
      (node (ref "C6") (pin "1") (pinfunction "1_1") (pintype "passive"))
      (node (ref "C7") (pin "1") (pinfunction "1_1") (pintype "passive"))
      (node (ref "C8") (pin "1") (pinfunction "1_1") (pintype "passive"))
      (node (ref "L3") (pin "1") (pinfunction "1_1") (pintype "passive"))
      (node (ref "R54") (pin "1") (pinfunction "1_1") (pintype "passive"))
      (node (ref "U2") (pin "A6") (pinfunction "VDDLDO_A6") (pintype "power_in"))
      (node (ref "U2") (pin "C17") (pinfunction "VDDLDO_C17") (pintype "power_in"))
      (node (ref "U2") (pin "U12") (pinfunction "VDDLDO_U12") (pintype "power_in"))
    )
    (net (code "3") (name "+2.8") (class "Default")
      (node (ref "3") (pin "2") (pinfunction "2_2") (pintype "passive"))
      (node (ref "4") (pin "2") (pinfunction "2_2") (pintype "passive"))
      (node (ref "FB3") (pin "2") (pinfunction "2_2") (pintype "passive"))
      (node (ref "FB6") (pin "1") (pinfunction "1_1") (pintype "passive"))
      (node (ref "IC1") (pin "4") (pinfunction "AVDD_4") (pintype "passive"))
      (node (ref "R38") (pin "1") (pinfunction "1_1") (pintype "passive"))
      (node (ref "U7") (pin "2") (pinfunction "VOUT_2") (pintype "passive"))
    )
    (net (code "4") (name "+3.3") (class "Default")
      (node (ref "C10") (pin "2") (pinfunction "2_2") (pintype "passive"))
      (node (ref "C11") (pin "2") (pinfunction "2_2") (pintype "passive"))
      (node (ref "C12") (pin "2") (pinfunction "2_2") (pintype "passive"))
      (node (ref "C13") (pin "2") (pinfunction "2_2") (pintype "passive"))
      (node (ref "C14") (pin "2") (pinfunction "2_2") (pintype "passive"))
      (node (ref "C16") (pin "2") (pinfunction "2_2") (pintype "passive"))
      (node (ref "C17") (pin "2") (pinfunction "2_2") (pintype "passive"))
      (node (ref "C18") (pin "2") (pinfunction "2_2") (pintype "passive"))
      (node (ref "C19") (pin "2") (pinfunction "2_2") (pintype "passive"))
      (node (ref "C20") (pin "2") (pinfunction "2_2") (pintype "passive"))
      (node (ref "C21") (pin "2") (pinfunction "2_2") (pintype "passive"))
      (node (ref "C22") (pin "2") (pinfunction "2_2") (pintype "passive"))
      (node (ref "C23") (pin "2") (pinfunction "2_2") (pintype "passive"))
      (node (ref "C24") (pin "2") (pinfunction "2_2") (pintype "passive"))
      (node (ref "C25") (pin "2") (pinfunction "2_2") (pintype "passive"))
      (node (ref "C26") (pin "2") (pinfunction "2_2") (pintype "passive"))
      (node (ref "C27") (pin "2") (pinfunction "2_2") (pintype "passive"))
      (node (ref "C28") (pin "2") (pinfunction "2_2") (pintype "passive"))
      (node (ref "C29") (pin "2") (pinfunction "2_2") (pintype "passive"))
      (node (ref "C30") (pin "2") (pinfunction "2_2") (pintype "passive"))
      (node (ref "C31") (pin "2") (pinfunction "2_2") (pintype "passive"))
      (node (ref "C32") (pin "2") (pinfunction "2_2") (pintype "passive"))
      (node (ref "C33") (pin "2") (pinfunction "2_2") (pintype "passive"))
      (node (ref "C34") (pin "2") (pinfunction "2_2") (pintype "passive"))
      (node (ref "C35") (pin "2") (pinfunction "2_2") (pintype "passive"))
      (node (ref "C48") (pin "2") (pinfunction "2_2") (pintype "passive"))
      (node (ref "C49") (pin "2") (pinfunction "2_2") (pintype "passive"))
      (node (ref "C9") (pin "2") (pinfunction "2_2") (pintype "passive"))
      (node (ref "D5") (pin "2") (pinfunction "2_2") (pintype "passive"))
      (node (ref "FB1") (pin "2") (pinfunction "2_2") (pintype "passive"))
      (node (ref "FB2") (pin "2") (pinfunction "2_2") (pintype "passive"))
      (node (ref "FB4") (pin "1") (pinfunction "1_1") (pintype "passive"))
      (node (ref "FB5") (pin "1") (pinfunction "1_1") (pintype "passive"))
      (node (ref "FB7") (pin "1") (pinfunction "1_1") (pintype "passive"))
      (node (ref "JP2") (pin "5") (pinfunction "5_5") (pintype "passive"))
      (node (ref "L2") (pin "1") (pinfunction "1_1") (pintype "passive"))
      (node (ref "P1") (pin "4") (pinfunction "VDD_4") (pintype "passive"))
      (node (ref "R1") (pin "1") (pinfunction "1_1") (pintype "passive"))
      (node (ref "R12") (pin "1") (pinfunction "1_1") (pintype "passive"))
      (node (ref "R15") (pin "1") (pinfunction "1_1") (pintype "passive"))
      (node (ref "R18") (pin "1") (pinfunction "1_1") (pintype "passive"))
      (node (ref "R19") (pin "1") (pinfunction "1_1") (pintype "passive"))
      (node (ref "R20") (pin "1") (pinfunction "1_1") (pintype "passive"))
      (node (ref "R21") (pin "1") (pinfunction "1_1") (pintype "passive"))
      (node (ref "R22") (pin "1") (pinfunction "1_1") (pintype "passive"))
      (node (ref "R23") (pin "1") (pinfunction "1_1") (pintype "passive"))
      (node (ref "R25") (pin "2") (pinfunction "2_2") (pintype "passive"))
      (node (ref "R31") (pin "2") (pinfunction "2_2") (pintype "passive"))
      (node (ref "R35") (pin "1") (pinfunction "1_1") (pintype "passive"))
      (node (ref "R37") (pin "1") (pinfunction "1_1") (pintype "passive"))
      (node (ref "R39") (pin "2") (pinfunction "2_2") (pintype "passive"))
      (node (ref "R4") (pin "2") (pinfunction "2_2") (pintype "passive"))
      (node (ref "R40") (pin "2") (pinfunction "2_2") (pintype "passive"))
      (node (ref "R41") (pin "2") (pinfunction "2_2") (pintype "passive"))
      (node (ref "R48") (pin "2") (pinfunction "2_2") (pintype "passive"))
      (node (ref "R49") (pin "2") (pinfunction "2_2") (pintype "passive"))
      (node (ref "R51") (pin "2") (pinfunction "2_2") (pintype "passive"))
      (node (ref "R52") (pin "1") (pinfunction "1_1") (pintype "passive"))
      (node (ref "R56") (pin "2") (pinfunction "2_2") (pintype "passive"))
      (node (ref "SW1") (pin "1") (pinfunction "1_1") (pintype "passive"))
      (node (ref "SW2") (pin "1") (pinfunction "1_1") (pintype "passive"))
      (node (ref "U1") (pin "1") (pinfunction "VBAT_1") (pintype "power_in"))
      (node (ref "U1") (pin "24") (pinfunction "VDD_1_24") (pintype "power_in"))
      (node (ref "U1") (pin "36") (pinfunction "VDD_2_36") (pintype "power_in"))
      (node (ref "U1") (pin "48") (pinfunction "VDD_3_48") (pintype "power_in"))
      (node (ref "U1") (pin "9") (pinfunction "VDDA_9") (pintype "power_in"))
      (node (ref "U11") (pin "7") (pinfunction "VIN2_7") (pintype "passive"))
      (node (ref "U11") (pin "8") (pinfunction "EN2_8") (pintype "passive"))
      (node (ref "U2") (pin "E11") (pinfunction "VDD_1_E11") (pintype "power_in"))
      (node (ref "U2") (pin "E6") (pinfunction "VDD_1_E6") (pintype "power_in"))
      (node (ref "U2") (pin "E9") (pinfunction "VDD_1_E9") (pintype "power_in"))
      (node (ref "U2") (pin "F17") (pinfunction "VDD33USB_F17") (pintype "power_in"))
      (node (ref "U2") (pin "F5") (pinfunction "VDD_1_F5") (pintype "power_in"))
      (node (ref "U2") (pin "G13") (pinfunction "VDD_1_G13") (pintype "power_in"))
      (node (ref "U2") (pin "G17") (pinfunction "VDD50USB_G17") (pintype "power_in"))
      (node (ref "U2") (pin "G5") (pinfunction "VDD_1_G5") (pintype "power_in"))
      (node (ref "U2") (pin "H13") (pinfunction "VDD_1_H13") (pintype "power_in"))
      (node (ref "U2") (pin "H5") (pinfunction "VDD_1_H5") (pintype "power_in"))
      (node (ref "U2") (pin "J13") (pinfunction "VDD_1_J13") (pintype "power_in"))
      (node (ref "U2") (pin "K13") (pinfunction "VDD_1_K13") (pintype "power_in"))
      (node (ref "U2") (pin "K5") (pinfunction "VDD_2_K5") (pintype "power_in"))
      (node (ref "U2") (pin "L13") (pinfunction "VDD_1_L13") (pintype "power_in"))
      (node (ref "U2") (pin "L5") (pinfunction "VDD_2_L5") (pintype "power_in"))
      (node (ref "U2") (pin "M13") (pinfunction "VDD_2_M13") (pintype "power_in"))
      (node (ref "U2") (pin "M5") (pinfunction "VDD_2_M5") (pintype "power_in"))
      (node (ref "U2") (pin "N10") (pinfunction "VDD_2_N10") (pintype "power_in"))
      (node (ref "U2") (pin "N11") (pinfunction "VDD_2_N11") (pintype "power_in"))
      (node (ref "U2") (pin "N12") (pinfunction "VDD_2_N12") (pintype "power_in"))
      (node (ref "U2") (pin "N7") (pinfunction "VDD_2_N7") (pintype "power_in"))
      (node (ref "U2") (pin "N8") (pinfunction "VDD_2_N8") (pintype "power_in"))
      (node (ref "U2") (pin "P17") (pinfunction "VDD_2_P17") (pintype "power_in"))
      (node (ref "U3") (pin "A7") (pinfunction "VDD_A7") (pintype "power_in"))
      (node (ref "U3") (pin "B2") (pinfunction "VDDQ_B2") (pintype "power_in"))
      (node (ref "U3") (pin "B7") (pinfunction "VDDQ_B7") (pintype "power_in"))
      (node (ref "U3") (pin "C9") (pinfunction "VDDQ_C9") (pintype "power_in"))
      (node (ref "U3") (pin "D9") (pinfunction "VDDQ_D9") (pintype "power_in"))
      (node (ref "U3") (pin "E1") (pinfunction "VDDQ_E1") (pintype "power_in"))
      (node (ref "U3") (pin "F9") (pinfunction "VDD_F9") (pintype "power_in"))
      (node (ref "U3") (pin "L1") (pinfunction "VDDQ_L1") (pintype "power_in"))
      (node (ref "U3") (pin "L7") (pinfunction "VDD_L7") (pintype "power_in"))
      (node (ref "U3") (pin "M9") (pinfunction "VDDQ_M9") (pintype "power_in"))
      (node (ref "U3") (pin "N9") (pinfunction "VDDQ_N9") (pintype "power_in"))
      (node (ref "U3") (pin "P2") (pinfunction "VDDQ_P2") (pintype "power_in"))
      (node (ref "U3") (pin "P7") (pinfunction "VDDQ_P7") (pintype "power_in"))
      (node (ref "U3") (pin "R7") (pinfunction "VDD_R7") (pintype "power_in"))
      (node (ref "U6") (pin "8") (pinfunction "VCC_8") (pintype "passive"))
    )
    (net (code "5") (name "+5") (class "Default")
      (node (ref "5") (pin "2") (pinfunction "2_2") (pintype "passive"))
      (node (ref "6") (pin "2") (pinfunction "2_2") (pintype "passive"))
      (node (ref "8") (pin "5") (pinfunction "VIN_5") (pintype "bidirectional"))
      (node (ref "D2") (pin "2") (pinfunction "K_2") (pintype "passive"))
      (node (ref "E1") (pin "1") (pinfunction "1_1") (pintype "passive"))
      (node (ref "E2") (pin "1") (pinfunction "1_1") (pintype "passive"))
      (node (ref "E3") (pin "1") (pinfunction "1_1") (pintype "passive"))
      (node (ref "JP2") (pin "3") (pinfunction "3_3") (pintype "passive"))
      (node (ref "L1") (pin "2") (pinfunction "2_2") (pintype "passive"))
      (node (ref "U11") (pin "18") (pinfunction "EN3_18") (pintype "passive"))
      (node (ref "U11") (pin "19") (pinfunction "VIN3_19") (pintype "passive"))
      (node (ref "U4") (pin "A4B9") (pinfunction "VBUS_A4B9") (pintype "passive"))
      (node (ref "U4") (pin "B4A9") (pinfunction "VBUS_B4A9") (pintype "passive"))
      (node (ref "U5") (pin "A4B9") (pinfunction "VBUS_A4B9") (pintype "passive"))
      (node (ref "U5") (pin "B4A9") (pinfunction "VBUS_B4A9") (pintype "passive"))
    )
    (net (code "6") (name "/BOOT0") (class "Default")
      (node (ref "LED3") (pin "1") (pinfunction "A_1") (pintype "passive"))
      (node (ref "Q2") (pin "2") (pinfunction "E_2") (pintype "passive"))
      (node (ref "R34") (pin "2") (pinfunction "2_2") (pintype "passive"))
      (node (ref "U2") (pin "E8") (pinfunction "BOOT0_E8") (pintype "input"))
    )
    (net (code "7") (name "/CAM_PWDN {slash} PG7") (class "Default")
      (node (ref "IC1") (pin "8") (pinfunction "PWDN_8") (pintype "passive"))
      (node (ref "R39") (pin "1") (pinfunction "1_1") (pintype "passive"))
      (node (ref "U2") (pin "F16") (pinfunction "PG7/HRTIM_CHE2/SAI1_MCLK_A/USART6_CK/FMC_INT/DCMI_D13/LCD_CLK/EVENTOUT_F16") (pintype "bidirectional"))
    )
    (net (code "8") (name "/DAP_BOOT0") (class "Default")
      (node (ref "R5") (pin "2") (pinfunction "2_2") (pintype "passive"))
      (node (ref "R56") (pin "1") (pinfunction "1_1") (pintype "passive"))
      (node (ref "U1") (pin "44") (pinfunction "BOOT0_44") (pintype "input"))
    )
    (net (code "9") (name "/DAP_DM") (class "Default")
      (node (ref "R14") (pin "1") (pinfunction "1_1") (pintype "passive"))
      (node (ref "U1") (pin "32") (pinfunction "PA11_32") (pintype "bidirectional"))
    )
    (net (code "10") (name "/DAP_DP") (class "Default")
      (node (ref "R17") (pin "1") (pinfunction "1_1") (pintype "passive"))
      (node (ref "R18") (pin "2") (pinfunction "2_2") (pintype "passive"))
      (node (ref "U1") (pin "33") (pinfunction "PA12_33") (pintype "bidirectional"))
    )
    (net (code "11") (name "/DAP_LED1") (class "Default")
      (node (ref "R6") (pin "1") (pinfunction "1_1") (pintype "passive"))
      (node (ref "U1") (pin "25") (pinfunction "PB12_25") (pintype "bidirectional"))
    )
    (net (code "12") (name "/DAP_LED2") (class "Default")
      (node (ref "R3") (pin "1") (pinfunction "1_1") (pintype "passive"))
      (node (ref "U1") (pin "45") (pinfunction "PB8_45") (pintype "bidirectional"))
    )
    (net (code "13") (name "/DAP_RST") (class "Default")
      (node (ref "JP1") (pin "9") (pinfunction "9_9") (pintype "passive"))
      (node (ref "R11") (pin "1") (pinfunction "1_1") (pintype "passive"))
      (node (ref "U1") (pin "16") (pinfunction "PA6_16") (pintype "bidirectional"))
    )
    (net (code "14") (name "/DAP_RXD") (class "Default")
      (node (ref "JP1") (pin "7") (pinfunction "7_7") (pintype "passive"))
      (node (ref "R10") (pin "1") (pinfunction "1_1") (pintype "passive"))
      (node (ref "U1") (pin "31") (pinfunction "PA10_31") (pintype "bidirectional"))
    )
    (net (code "15") (name "/DAP_TCK{slash}CK") (class "Default")
      (node (ref "R15") (pin "2") (pinfunction "2_2") (pintype "passive"))
      (node (ref "R16") (pin "1") (pinfunction "1_1") (pintype "passive"))
      (node (ref "U1") (pin "14") (pinfunction "PA4_14") (pintype "bidirectional"))
    )
    (net (code "16") (name "/DAP_TMS{slash}IO") (class "Default")
      (node (ref "R12") (pin "2") (pinfunction "2_2") (pintype "passive"))
      (node (ref "R13") (pin "1") (pinfunction "1_1") (pintype "passive"))
      (node (ref "U1") (pin "12") (pinfunction "PA2_12") (pintype "bidirectional"))
    )
    (net (code "17") (name "/DAP_TXD") (class "Default")
      (node (ref "JP1") (pin "5") (pinfunction "5_5") (pintype "passive"))
      (node (ref "R9") (pin "1") (pinfunction "1_1") (pintype "passive"))
      (node (ref "U1") (pin "30") (pinfunction "PA9_30") (pintype "bidirectional"))
    )
    (net (code "18") (name "/DAP_nRST") (class "Default")
      (node (ref "C15") (pin "2") (pinfunction "2_2") (pintype "passive"))
      (node (ref "R4") (pin "1") (pinfunction "1_1") (pintype "passive"))
      (node (ref "U1") (pin "7") (pinfunction "NRST_7") (pintype "bidirectional"))
    )
    (net (code "19") (name "/DCMI_D0 {slash} PC6") (class "Default")
      (node (ref "IC1") (pin "19") (pinfunction "Y2_19") (pintype "passive"))
      (node (ref "U2") (pin "F14") (pinfunction "PC6/HRTIM_CHA1/TIM3_CH1/TIM8_CH1/DFSDM1_CKIN3/I2S2_MCK/USART6_TX/SDMMC1_D0DIR/FMC_NWAIT/SDMMC2_D6/SDMMC1_D6/DCMI_D0/LCD_HSYNC/EVENTOUT_F14") (pintype "bidirectional"))
    )
    (net (code "20") (name "/DCMI_D1 {slash} PC7") (class "Default")
      (node (ref "IC1") (pin "21") (pinfunction "Y3_21") (pintype "passive"))
      (node (ref "U2") (pin "F13") (pinfunction "PC7/TRGIO/HRTIM_CHA2/TIM3_CH2/TIM8_CH2/DFSDM1_DATIN3/I2S3_MCK/USART6_RX/SDMMC1_D123DIR/FMC_NE1/SDMMC2_D7/SWPMI_TX/SDMMC1_D7/DCMI_D1/LCD_G6/EVENTOUT_F13") (pintype "bidirectional"))
    )
    (net (code "21") (name "/DCMI_D2 {slash} PG10") (class "Default")
      (node (ref "IC1") (pin "22") (pinfunction "Y4_22") (pintype "passive"))
      (node (ref "U2") (pin "A9") (pinfunction "PG10/HRTIM_FLT5/SPI1_NSS/I2S1_WS/LCD_G3/SAI2_SD_B/FMC_NE3/DCMI_D2/LCD_B2/EVENTOUT_A9") (pintype "bidirectional"))
    )
    (net (code "22") (name "/DCMI_D3 {slash} PG11") (class "Default")
      (node (ref "IC1") (pin "20") (pinfunction "Y5_20") (pintype "passive"))
      (node (ref "U2") (pin "B9") (pinfunction "PG11/LPTIM1_IN2/HRTIM_EEV4/SPI1_SCK/I2S1_CK/SPDIFRX1_IN1/SDMMC2_D2/ETH_MII_TX_EN/ETH_RMII_TX_EN/DCMI_D3/LCD_B3/EVENTOUT_B9") (pintype "bidirectional"))
    )
    (net (code "23") (name "/DCMI_D4 {slash} PE4") (class "Default")
      (node (ref "IC1") (pin "18") (pinfunction "Y6_18") (pintype "passive"))
      (node (ref "U2") (pin "D2") (pinfunction "PE4/TRACED1/SAI1_D2/DFSDM1_DATIN3/TIM15_CH1N/SPI4_NSS/SAI1_FS_A/SAI4_FS_A/SAI4_D2/FMC_A20/DCMI_D4/LCD_B0/EVENTOUT_D2") (pintype "bidirectional"))
    )
    (net (code "24") (name "/DCMI_D5 {slash} PD3") (class "Default")
      (node (ref "IC1") (pin "16") (pinfunction "Y7_16") (pintype "passive"))
      (node (ref "U2") (pin "B12") (pinfunction "PD3/DFSDM1_CKOUT/SPI2_SCK/I2S2_CK/USART2_CTS/USART2_NSS/FMC_CLK/DCMI_D5/LCD_G7/EVENTOUT_B12") (pintype "bidirectional"))
    )
    (net (code "25") (name "/DCMI_D6 {slash} PE5") (class "Default")
      (node (ref "IC1") (pin "14") (pinfunction "Y8_14") (pintype "passive"))
      (node (ref "U2") (pin "D1") (pinfunction "PE5/TRACED2/SAI1_CK2/DFSDM1_CKIN3/TIM15_CH1/SPI4_MISO/SAI1_SCK_A/SAI4_SCK_A/SAI4_CK2/FMC_A21/DCMI_D6/LCD_G0/EVENTOUT_D1") (pintype "bidirectional"))
    )
    (net (code "26") (name "/DCMI_D7 {slash} PE6") (class "Default")
      (node (ref "IC1") (pin "12") (pinfunction "Y9_12") (pintype "passive"))
      (node (ref "U2") (pin "E5") (pinfunction "PE6/TRACED3/TIM1_BKIN2/SAI1_D1/TIM15_CH2/SPI4_MOSI/SAI1_SD_A/SAI4_SD_A/SAI4_D1/SAI2_MCLK_B/TIM1_BKIN2_COMP12/FMC_A22/DCMI_D7/LCD_G1/EVENTOUT_E5") (pintype "bidirectional"))
    )
    (net (code "27") (name "/DCMI_HSYNC {slash} PA4") (class "Default")
      (node (ref "IC1") (pin "9") (pinfunction "HSYNC_9") (pintype "passive"))
      (node (ref "U2") (pin "U3") (pinfunction "PA4/D1PWREN/TIM5_ETR/SPI1_NSS/I2S1_WS/SPI3_NSS/I2S3_WS/USART2_CK/SPI6_NSS/OTG_HS_SOF/DCMI_HSYNC/LCD_VSYNC/EVENTOUT_U3") (pintype "bidirectional"))
    )
    (net (code "28") (name "/DCMI_PIXCLK {slash} PA6") (class "Default")
      (node (ref "IC1") (pin "17") (pinfunction "PCLK_17") (pintype "passive"))
      (node (ref "U2") (pin "R3") (pinfunction "PA6/TIM1_BKIN/TIM3_CH1/TIM8_BKIN/SPI1_MISO/I2S1_SDI/SPI6_MISO/TIM13_CH1/TIM8_BKIN_COMP12/MDIOS_MDC/TIM1_BKIN_COMP12/DCMI_PIXCLK/LCD_G2/EVENTOUT_R3") (pintype "bidirectional"))
    )
    (net (code "29") (name "/DCMI_VSYNC {slash} PG9") (class "Default")
      (node (ref "IC1") (pin "7") (pinfunction "VSYNC_7") (pintype "passive"))
      (node (ref "U2") (pin "A10") (pinfunction "PG9/SPI1_MISO/I2S1_SDI/USART6_RX/SPDIFRX1_IN4/QUADSPI_BK2_IO2/SAI2_FS_B/FMC_NE2/FMC_NCE/DCMI_VSYNC/EVENTOUT_A10") (pintype "bidirectional"))
    )
    (net (code "30") (name "/DISP") (class "Default")
      (node (ref "R53") (pin "2") (pinfunction "2_2") (pintype "passive"))
      (node (ref "U10") (pin "10") (pinfunction "10_10") (pintype "passive"))
    )
    (net (code "31") (name "/FMC_A0 {slash} PF0") (class "Default")
      (node (ref "U2") (pin "G4") (pinfunction "PF0/I2C2_SDA/FMC_A0/EVENTOUT_G4") (pintype "bidirectional"))
      (node (ref "U3") (pin "G8") (pinfunction "A0_G8") (pintype "input"))
    )
    (net (code "32") (name "/FMC_A1 {slash} PF1") (class "Default")
      (node (ref "U2") (pin "G3") (pinfunction "PF1/I2C2_SCL/FMC_A1/EVENTOUT_G3") (pintype "bidirectional"))
      (node (ref "U3") (pin "G9") (pinfunction "A1_G9") (pintype "input"))
    )
    (net (code "33") (name "/FMC_A2 {slash} PF2") (class "Default")
      (node (ref "U2") (pin "G1") (pinfunction "PF2/I2C2_SMBA/FMC_A2/EVENTOUT_G1") (pintype "bidirectional"))
      (node (ref "U3") (pin "F7") (pinfunction "A2_F7") (pintype "input"))
    )
    (net (code "34") (name "/FMC_A3 {slash} PF3") (class "Default")
      (node (ref "U2") (pin "H4") (pinfunction "PF3/FMC_A3/EVENTOUT_H4") (pintype "bidirectional"))
      (node (ref "U3") (pin "F3") (pinfunction "A3_F3") (pintype "input"))
    )
    (net (code "35") (name "/FMC_A4 {slash} PF4") (class "Default")
      (node (ref "U2") (pin "J5") (pinfunction "PF4/FMC_A4/EVENTOUT_J5") (pintype "bidirectional"))
      (node (ref "U3") (pin "G1") (pinfunction "A4_G1") (pintype "input"))
    )
    (net (code "36") (name "/FMC_A5 {slash} PF5") (class "Default")
      (node (ref "U2") (pin "J4") (pinfunction "PF5/FMC_A5/EVENTOUT_J4") (pintype "bidirectional"))
      (node (ref "U3") (pin "G2") (pinfunction "A5_G2") (pintype "input"))
    )
    (net (code "37") (name "/FMC_A6 {slash} PF12") (class "Default")
      (node (ref "U2") (pin "R7") (pinfunction "PF12/FMC_A6/EVENTOUT_R7") (pintype "bidirectional"))
      (node (ref "U3") (pin "G3") (pinfunction "A6_G3") (pintype "input"))
    )
    (net (code "38") (name "/FMC_A7 {slash} PF13") (class "Default")
      (node (ref "U2") (pin "P7") (pinfunction "PF13/DFSDM1_DATIN6/I2C4_SMBA/FMC_A7/EVENTOUT_P7") (pintype "bidirectional"))
      (node (ref "U3") (pin "H1") (pinfunction "A7_H1") (pintype "input"))
    )
    (net (code "39") (name "/FMC_A8 {slash} PF14") (class "Default")
      (node (ref "U2") (pin "P8") (pinfunction "PF14/DFSDM1_CKIN6/I2C4_SCL/FMC_A8/EVENTOUT_P8") (pintype "bidirectional"))
      (node (ref "U3") (pin "H2") (pinfunction "A8_H2") (pintype "input"))
    )
    (net (code "40") (name "/FMC_A9 {slash} PF15") (class "Default")
      (node (ref "U2") (pin "R9") (pinfunction "PF15/I2C4_SDA/FMC_A9/EVENTOUT_R9") (pintype "bidirectional"))
      (node (ref "U3") (pin "J3") (pinfunction "A9_J3") (pintype "input"))
    )
    (net (code "41") (name "/FMC_A10 {slash} PG0") (class "Default")
      (node (ref "U2") (pin "T8") (pinfunction "PG0/FMC_A10/EVENTOUT_T8") (pintype "bidirectional"))
      (node (ref "U3") (pin "G7") (pinfunction "A10_G7") (pintype "input"))
    )
    (net (code "42") (name "/FMC_A11 {slash} PG1") (class "Default")
      (node (ref "U2") (pin "U8") (pinfunction "PG1/FMC_A11/EVENTOUT_U8") (pintype "bidirectional"))
      (node (ref "U3") (pin "H9") (pinfunction "A11_H9") (pintype "input"))
    )
    (net (code "43") (name "/FMC_BA0 {slash} PG4") (class "Default")
      (node (ref "U2") (pin "H14") (pinfunction "PG4/TIM1_BKIN2/TIM1_BKIN2_COMP12/FMC_A14/FMC_BA0/EVENTOUT_H14") (pintype "bidirectional"))
      (node (ref "U3") (pin "J7") (pinfunction "BA0_J7") (pintype "input"))
    )
    (net (code "44") (name "/FMC_BA1 {slash} PG5") (class "Default")
      (node (ref "U2") (pin "G14") (pinfunction "PG5/TIM1_ETR/FMC_A15/FMC_BA1/EVENTOUT_G14") (pintype "bidirectional"))
      (node (ref "U3") (pin "H8") (pinfunction "BA1_H8") (pintype "input"))
    )
    (net (code "45") (name "/FMC_D0 {slash} PD14") (class "Default")
      (node (ref "U2") (pin "P16") (pinfunction "PD14/TIM4_CH3/SAI3_MCLK_B/UART8_CTS/FMC_D0/FMC_DA0/EVENTOUT_P16") (pintype "bidirectional"))
      (node (ref "U3") (pin "R8") (pinfunction "DQ0_R8") (pintype "bidirectional"))
    )
    (net (code "46") (name "/FMC_D1 {slash} PD15") (class "Default")
      (node (ref "U2") (pin "P15") (pinfunction "PD15/TIM4_CH4/SAI3_MCLK_A/UART8_RTS/UART8_DE/FMC_D1/FMC_DA1/EVENTOUT_P15") (pintype "bidirectional"))
      (node (ref "U3") (pin "N7") (pinfunction "DQ1_N7") (pintype "bidirectional"))
    )
    (net (code "47") (name "/FMC_D2 {slash} PD0") (class "Default")
      (node (ref "U2") (pin "D13") (pinfunction "PD0/DFSDM1_CKIN6/SAI3_SCK_A/UART4_RX/FDCAN1_RX/FMC_D2/FMC_DA2/EVENTOUT_D13") (pintype "bidirectional"))
      (node (ref "U3") (pin "R9") (pinfunction "DQ2_R9") (pintype "bidirectional"))
    )
    (net (code "48") (name "/FMC_D3 {slash} PD1") (class "Default")
      (node (ref "U2") (pin "E12") (pinfunction "PD1/DFSDM1_DATIN6/SAI3_SD_A/UART4_TX/FDCAN1_TX/FMC_D3/FMC_DA3/EVENTOUT_E12") (pintype "bidirectional"))
      (node (ref "U3") (pin "N8") (pinfunction "DQ3_N8") (pintype "bidirectional"))
    )
    (net (code "49") (name "/FMC_D4 {slash} PE7") (class "Default")
      (node (ref "U2") (pin "U9") (pinfunction "PE7/TIM1_ETR/DFSDM1_DATIN2/UART7_RX/QUADSPI_BK2_IO0/FMC_D4/FMC_DA4/EVENTOUT_U9") (pintype "bidirectional"))
      (node (ref "U3") (pin "P9") (pinfunction "DQ4_P9") (pintype "bidirectional"))
    )
    (net (code "50") (name "/FMC_D5 {slash} PE8") (class "Default")
      (node (ref "U2") (pin "T9") (pinfunction "PE8/TIM1_CH1N/DFSDM1_CKIN2/UART7_TX/QUADSPI_BK2_IO1/FMC_D5/FMC_DA5/COMP2_OUT/EVENTOUT_T9") (pintype "bidirectional"))
      (node (ref "U3") (pin "M8") (pinfunction "DQ5_M8") (pintype "bidirectional"))
    )
    (net (code "51") (name "/FMC_D6 {slash} PE9") (class "Default")
      (node (ref "U2") (pin "P9") (pinfunction "PE9/TIM1_CH1/DFSDM1_CKOUT/UART7_RTS/UART7_DE/QUADSPI_BK2_IO2/FMC_D6/FMC_DA6/EVENTOUT_P9") (pintype "bidirectional"))
      (node (ref "U3") (pin "M7") (pinfunction "DQ6_M7") (pintype "bidirectional"))
    )
    (net (code "52") (name "/FMC_D7 {slash} PE10") (class "Default")
      (node (ref "U2") (pin "N9") (pinfunction "PE10/TIM1_CH2N/DFSDM1_DATIN4/UART7_CTS/QUADSPI_BK2_IO3/FMC_D7/FMC_DA7/EVENTOUT_N9") (pintype "bidirectional"))
      (node (ref "U3") (pin "L8") (pinfunction "DQ7_L8") (pintype "bidirectional"))
    )
    (net (code "53") (name "/FMC_D8 {slash} PE11") (class "Default")
      (node (ref "U2") (pin "P10") (pinfunction "PE11/TIM1_CH2/DFSDM1_CKIN4/SPI4_NSS/SAI2_SD_B/FMC_D8/FMC_DA8/LCD_G3/EVENTOUT_P10") (pintype "bidirectional"))
      (node (ref "U3") (pin "L2") (pinfunction "DQ8_L2") (pintype "bidirectional"))
    )
    (net (code "54") (name "/FMC_D9 {slash} PE12") (class "Default")
      (node (ref "U2") (pin "R10") (pinfunction "PE12/TIM1_CH3N/DFSDM1_DATIN5/SPI4_SCK/SAI2_SCK_B/FMC_D9/FMC_DA9/COMP1_OUT/LCD_B4/EVENTOUT_R10") (pintype "bidirectional"))
      (node (ref "U3") (pin "M3") (pinfunction "DQ9_M3") (pintype "bidirectional"))
    )
    (net (code "55") (name "/FMC_D10 {slash} PE13") (class "Default")
      (node (ref "U2") (pin "T10") (pinfunction "PE13/TIM1_CH3/DFSDM1_CKIN5/SPI4_MISO/SAI2_FS_B/FMC_D10/FMC_DA10/COMP2_OUT/LCD_DE/EVENTOUT_T10") (pintype "bidirectional"))
      (node (ref "U3") (pin "M2") (pinfunction "DQ10_M2") (pintype "bidirectional"))
    )
    (net (code "56") (name "/FMC_D11 {slash} PE14") (class "Default")
      (node (ref "U2") (pin "U10") (pinfunction "PE14/TIM1_CH4/SPI4_MOSI/SAI2_MCLK_B/FMC_D11/FMC_DA11/LCD_CLK/EVENTOUT_U10") (pintype "bidirectional"))
      (node (ref "U3") (pin "P1") (pinfunction "DQ11_P1") (pintype "bidirectional"))
    )
    (net (code "57") (name "/FMC_D12 {slash} PE15") (class "Default")
      (node (ref "U2") (pin "R11") (pinfunction "PE15/TIM1_BKIN/FMC_D12/FMC_DA12/TIM1_BKIN_COMP12/COMP_TIM1_BKIN/LCD_R7/EVENTOUT_R11") (pintype "bidirectional"))
      (node (ref "U3") (pin "N2") (pinfunction "DQ12_N2") (pintype "bidirectional"))
    )
    (net (code "58") (name "/FMC_D13 {slash} PD8") (class "Default")
      (node (ref "U2") (pin "U16") (pinfunction "PD8/DFSDM1_CKIN3/SAI3_SCK_B/USART3_TX/SPDIFRX1_IN2/FMC_D13/FMC_DA13/EVENTOUT_U16") (pintype "bidirectional"))
      (node (ref "U3") (pin "R1") (pinfunction "DQ13_R1") (pintype "bidirectional"))
    )
    (net (code "59") (name "/FMC_D14 {slash} PD9") (class "Default")
      (node (ref "U2") (pin "T17") (pinfunction "PD9/DFSDM1_DATIN3/SAI3_SD_B/USART3_RX/FDCAN2_RXFD_MODE/FMC_D14/FMC_DA14/EVENTOUT_T17") (pintype "bidirectional"))
      (node (ref "U3") (pin "N3") (pinfunction "DQ14_N3") (pintype "bidirectional"))
    )
    (net (code "60") (name "/FMC_D15 {slash} PD10") (class "Default")
      (node (ref "U2") (pin "T16") (pinfunction "PD10/DFSDM1_CKOUT/SAI3_FS_B/USART3_CK/FDCAN2_TXFD_MODE/FMC_D15/FMC_DA15/LCD_B3/EVENTOUT_T16") (pintype "bidirectional"))
      (node (ref "U3") (pin "R2") (pinfunction "DQ15_R2") (pintype "bidirectional"))
    )
    (net (code "61") (name "/FMC_D16 {slash} PH8") (class "Default")
      (node (ref "U2") (pin "T13") (pinfunction "PH8/TIM5_ETR/I2C3_SDA/FMC_D16/DCMI_HSYNC/LCD_R2/EVENTOUT_T13") (pintype "bidirectional"))
      (node (ref "U3") (pin "E8") (pinfunction "DQ16_E8") (pintype "bidirectional"))
    )
    (net (code "62") (name "/FMC_D17 {slash} PH9") (class "Default")
      (node (ref "U2") (pin "R13") (pinfunction "PH9/TIM12_CH2/I2C3_SMBA/FMC_D17/DCMI_D0/LCD_R3/EVENTOUT_R13") (pintype "bidirectional"))
      (node (ref "U3") (pin "D7") (pinfunction "DQ17_D7") (pintype "bidirectional"))
    )
    (net (code "63") (name "/FMC_D18 {slash} PH10") (class "Default")
      (node (ref "U2") (pin "P13") (pinfunction "PH10/TIM5_CH1/I2C4_SMBA/FMC_D18/DCMI_D1/LCD_R4/EVENTOUT_P13") (pintype "bidirectional"))
      (node (ref "U3") (pin "D8") (pinfunction "DQ18_D8") (pintype "bidirectional"))
    )
    (net (code "64") (name "/FMC_D19 {slash} PH11") (class "Default")
      (node (ref "U2") (pin "P14") (pinfunction "PH11/TIM5_CH2/I2C4_SCL/FMC_D19/DCMI_D2/LCD_R5/EVENTOUT_P14") (pintype "bidirectional"))
      (node (ref "U3") (pin "B9") (pinfunction "DQ19_B9") (pintype "bidirectional"))
    )
    (net (code "65") (name "/FMC_D20 {slash} PH12") (class "Default")
      (node (ref "U2") (pin "R14") (pinfunction "PH12/TIM5_CH3/I2C4_SDA/FMC_D20/DCMI_D3/LCD_R6/EVENTOUT_R14") (pintype "bidirectional"))
      (node (ref "U3") (pin "C8") (pinfunction "DQ20_C8") (pintype "bidirectional"))
    )
    (net (code "66") (name "/FMC_D21 {slash} PH13") (class "Default")
      (node (ref "U2") (pin "D16") (pinfunction "PH13/TIM8_CH1N/UART4_TX/FDCAN1_TX/FMC_D21/LCD_G2/EVENTOUT_D16") (pintype "bidirectional"))
      (node (ref "U3") (pin "A9") (pinfunction "DQ21_A9") (pintype "bidirectional"))
    )
    (net (code "67") (name "/FMC_D22 {slash} PH14") (class "Default")
      (node (ref "U2") (pin "B17") (pinfunction "PH14/TIM8_CH2N/UART4_RX/FDCAN1_RX/FMC_D22/DCMI_D4/LCD_G3/EVENTOUT_B17") (pintype "bidirectional"))
      (node (ref "U3") (pin "C7") (pinfunction "DQ22_C7") (pintype "bidirectional"))
    )
    (net (code "68") (name "/FMC_D23 {slash} PH15") (class "Default")
      (node (ref "U2") (pin "B16") (pinfunction "PH15/TIM8_CH3N/FDCAN1_TXFD_MODE/FMC_D23/DCMI_D11/LCD_G4/EVENTOUT_B16") (pintype "bidirectional"))
      (node (ref "U3") (pin "A8") (pinfunction "DQ23_A8") (pintype "bidirectional"))
    )
    (net (code "69") (name "/FMC_D24 {slash} PI0") (class "Default")
      (node (ref "U2") (pin "A16") (pinfunction "PI0/TIM5_CH4/SPI2_NSS/I2S2_WS/FDCAN1_RXFD_MODE/FMC_D24/DCMI_D13/LCD_G5/EVENTOUT_A16") (pintype "bidirectional"))
      (node (ref "U3") (pin "A2") (pinfunction "DQ24_A2") (pintype "bidirectional"))
    )
    (net (code "70") (name "/FMC_D25 {slash} PI1") (class "Default")
      (node (ref "U2") (pin "A15") (pinfunction "PI1/TIM8_BKIN2/SPI2_SCK/I2S2_CK/TIM8_BKIN2_COMP12/FMC_D25/DCMI_D8/LCD_G6/EVENTOUT_A15") (pintype "bidirectional"))
      (node (ref "U3") (pin "C3") (pinfunction "DQ25_C3") (pintype "bidirectional"))
    )
    (net (code "71") (name "/FMC_D26 {slash} PI2") (class "Default")
      (node (ref "U2") (pin "B15") (pinfunction "PI2/TIM8_CH4/SPI2_MISO/I2S2_SDI/FMC_D26/DCMI_D9/LCD_G7/EVENTOUT_B15") (pintype "bidirectional"))
      (node (ref "U3") (pin "A1") (pinfunction "DQ26_A1") (pintype "bidirectional"))
    )
    (net (code "72") (name "/FMC_D27 {slash} PI3") (class "Default")
      (node (ref "U2") (pin "C14") (pinfunction "PI3/TIM8_ETR/SPI2_MOSI/I2S2_SDO/FMC_D27/DCMI_D10/EVENTOUT_C14") (pintype "bidirectional"))
      (node (ref "U3") (pin "C2") (pinfunction "DQ27_C2") (pintype "bidirectional"))
    )
    (net (code "73") (name "/FMC_D28 {slash} PI6") (class "Default")
      (node (ref "U2") (pin "A2") (pinfunction "PI6/TIM8_CH2/SAI2_SD_A/FMC_D28/DCMI_D6/LCD_B6/EVENTOUT_A2") (pintype "bidirectional"))
      (node (ref "U3") (pin "B1") (pinfunction "DQ28_B1") (pintype "bidirectional"))
    )
    (net (code "74") (name "/FMC_D29 {slash} PI7") (class "Default")
      (node (ref "U2") (pin "B3") (pinfunction "PI7/TIM8_CH3/SAI2_FS_A/FMC_D29/DCMI_D7/LCD_B7/EVENTOUT_B3") (pintype "bidirectional"))
      (node (ref "U3") (pin "D2") (pinfunction "DQ29_D2") (pintype "bidirectional"))
    )
    (net (code "75") (name "/FMC_D30 {slash} PI9") (class "Default")
      (node (ref "U2") (pin "E2") (pinfunction "PI9/UART4_RX/FDCAN1_RX/FMC_D30/LCD_VSYNC/EVENTOUT_E2") (pintype "bidirectional"))
      (node (ref "U3") (pin "D3") (pinfunction "DQ30_D3") (pintype "bidirectional"))
    )
    (net (code "76") (name "/FMC_D31 {slash} PI10") (class "Default")
      (node (ref "U2") (pin "F3") (pinfunction "PI10/FDCAN1_RXFD_MODE/ETH_MII_RX_ER/FMC_D31/LCD_HSYNC/EVENTOUT_F3") (pintype "bidirectional"))
      (node (ref "U3") (pin "E2") (pinfunction "DQ31_E2") (pintype "bidirectional"))
    )
    (net (code "77") (name "/FMC_NBL0 {slash} PE0") (class "Default")
      (node (ref "U2") (pin "C4") (pinfunction "PE0/LPTIM1_ETR/TIM4_ETR/HRTIM_SCIN/LPTIM2_ETR/UART8_RX/FDCAN1_RXFD_MODE/SAI2_MCLK_A/FMC_NBL0/DCMI_D2/EVENTOUT_C4") (pintype "bidirectional"))
      (node (ref "U3") (pin "K9") (pinfunction "DQM0_K9") (pintype "bidirectional"))
    )
    (net (code "78") (name "/FMC_NBL1 {slash} PE1") (class "Default")
      (node (ref "U2") (pin "B4") (pinfunction "PE1/LPTIM1_IN2/HRTIM_SCOUT/UART8_TX/FDCAN1_TXFD_MODE/FMC_NBL1/DCMI_D3/EVENTOUT_B4") (pintype "bidirectional"))
      (node (ref "U3") (pin "K1") (pinfunction "DQM1_K1") (pintype "bidirectional"))
    )
    (net (code "79") (name "/FMC_NBL2 {slash} PI4") (class "Default")
      (node (ref "U2") (pin "A4") (pinfunction "PI4/TIM8_BKIN/SAI2_MCLK_A/TIM8_BKIN_COMP12/FMC_NBL2/DCMI_D5/LCD_B4/EVENTOUT_A4") (pintype "bidirectional"))
      (node (ref "U3") (pin "F8") (pinfunction "DQM2_F8") (pintype "bidirectional"))
    )
    (net (code "80") (name "/FMC_NBL3 {slash} PI5") (class "Default")
      (node (ref "U2") (pin "A3") (pinfunction "PI5/TIM8_CH1/SAI2_SCK_A/FMC_NBL3/DCMI_VSYNC/LCD_B5/EVENTOUT_A3") (pintype "bidirectional"))
      (node (ref "U3") (pin "F2") (pinfunction "DQM3_F2") (pintype "bidirectional"))
    )
    (net (code "81") (name "/FMC_SDCKE0 {slash} PH2") (class "Default")
      (node (ref "U2") (pin "N2") (pinfunction "PH2/LPTIM1_IN2/QUADSPI_BK2_IO0/SAI2_SCK_B/ETH_MII_CRS/FMC_SDCKE0/LCD_R0/EVENTOUT_N2") (pintype "bidirectional"))
      (node (ref "U3") (pin "J2") (pinfunction "CKE_J2") (pintype "input"))
    )
    (net (code "82") (name "/FMC_SDCLK {slash} PG8") (class "Default")
      (node (ref "U2") (pin "F15") (pinfunction "PG8/TIM8_ETR/SPI6_NSS/USART6_RTS/USART6_DE/SPDIFRX1_IN3/ETH_PPS_OUT/FMC_SDCLK/LCD_G7/EVENTOUT_F15") (pintype "bidirectional"))
      (node (ref "U3") (pin "J1") (pinfunction "CLK_J1") (pintype "input"))
    )
    (net (code "83") (name "/FMC_SDNCAS {slash} PG15") (class "Default")
      (node (ref "U2") (pin "D6") (pinfunction "PG15/USART6_CTS/USART6_NSS/FMC_SDNCAS/DCMI_D13/EVENTOUT_D6") (pintype "bidirectional"))
      (node (ref "U3") (pin "K7") (pinfunction "CAS#_K7") (pintype "input"))
    )
    (net (code "84") (name "/FMC_SDNE0 {slash} PH3") (class "Default")
      (node (ref "U2") (pin "P2") (pinfunction "PH3/QUADSPI_BK2_IO1/SAI2_MCLK_B/ETH_MII_COL/FMC_SDNE0/LCD_R1/EVENTOUT_P2") (pintype "bidirectional"))
      (node (ref "U3") (pin "J8") (pinfunction "CS#_J8") (pintype "input"))
    )
    (net (code "85") (name "/FMC_SDNRAS {slash} PF11") (class "Default")
      (node (ref "U2") (pin "T7") (pinfunction "PF11/SPI5_MOSI/SAI2_SD_B/FMC_SDNRAS/DCMI_D12/EVENTOUT_T7") (pintype "bidirectional"))
      (node (ref "U3") (pin "J9") (pinfunction "RAS#_J9") (pintype "input"))
    )
    (net (code "86") (name "/FMC_SDNWE {slash} PC0") (class "Default")
      (node (ref "U2") (pin "L2") (pinfunction "PC0/DFSDM1_CKIN0/DFSDM1_DATIN4/SAI2_FS_B/OTG_HS_ULPI_STP/FMC_SDNWE/LCD_R5/EVENTOUT_L2") (pintype "bidirectional"))
      (node (ref "U3") (pin "K8") (pinfunction "WE#_K8") (pintype "input"))
    )
    (net (code "87") (name "/IIC2_SCL {slash} PH4") (class "Default")
      (node (ref "R44") (pin "1") (pinfunction "1_1") (pintype "passive"))
      (node (ref "U2") (pin "P3") (pinfunction "PH4/I2C2_SCL/LCD_G5/OTG_HS_ULPI_NXT/LCD_G4/EVENTOUT_P3") (pintype "bidirectional"))
    )
    (net (code "88") (name "/IIC2_SDA {slash} PH5") (class "Default")
      (node (ref "R45") (pin "1") (pinfunction "1_1") (pintype "passive"))
      (node (ref "U2") (pin "P4") (pinfunction "PH5/I2C2_SDA/SPI5_NSS/FMC_SDNWE/EVENTOUT_P4") (pintype "bidirectional"))
    )
    (net (code "89") (name "/IIC_SCLK {slash} PG2") (class "Default")
      (node (ref "R42") (pin "2") (pinfunction "2_2") (pintype "passive"))
      (node (ref "U2") (pin "H16") (pinfunction "PG2/TIM8_BKIN/TIM8_BKIN_COMP12/FMC_A12/EVENTOUT_H16") (pintype "bidirectional"))
    )
    (net (code "90") (name "/IIC_SDA {slash} PG3") (class "Default")
      (node (ref "R43") (pin "2") (pinfunction "2_2") (pintype "passive"))
      (node (ref "U2") (pin "H15") (pinfunction "PG3/TIM8_BKIN2/TIM8_BKIN2_COMP12/FMC_A13/EVENTOUT_H15") (pintype "bidirectional"))
    )
    (net (code "91") (name "/L3.3V") (class "Default")
      (node (ref "10") (pin "2") (pinfunction "2_2") (pintype "passive"))
      (node (ref "20") (pin "2") (pinfunction "2_2") (pintype "passive"))
      (node (ref "23") (pin "2") (pinfunction "2_2") (pintype "passive"))
      (node (ref "9") (pin "2") (pinfunction "2_2") (pintype "passive"))
      (node (ref "D4") (pin "2") (pinfunction "K_2") (pintype "passive"))
      (node (ref "FB5") (pin "2") (pinfunction "2_2") (pintype "passive"))
      (node (ref "JP3") (pin "5") (pinfunction "5_5") (pintype "passive"))
      (node (ref "R53") (pin "1") (pinfunction "1_1") (pintype "passive"))
      (node (ref "U10") (pin "37") (pinfunction "37_37") (pintype "passive"))
    )
    (net (code "92") (name "/LCD_B0 {slash} PJ12") (class "Default")
      (node (ref "RP5") (pin "1") (pintype "passive"))
      (node (ref "U2") (pin "D11") (pinfunction "PJ12/TRGOUT/LCD_G3/LCD_B0/EVENTOUT_D11") (pintype "bidirectional"))
    )
    (net (code "93") (name "/LCD_B1 {slash} PJ13") (class "Default")
      (node (ref "RP5") (pin "2") (pintype "passive"))
      (node (ref "U2") (pin "E10") (pinfunction "PJ13/LCD_B4/LCD_B1/EVENTOUT_E10") (pintype "bidirectional"))
    )
    (net (code "94") (name "/LCD_B2 {slash} PJ14") (class "Default")
      (node (ref "RP5") (pin "3") (pintype "passive"))
      (node (ref "U2") (pin "D10") (pinfunction "PJ14/LCD_B2/EVENTOUT_D10") (pintype "bidirectional"))
    )
    (net (code "95") (name "/LCD_B3 {slash} PJ15") (class "Default")
      (node (ref "RP5") (pin "4") (pintype "passive"))
      (node (ref "U2") (pin "B10") (pinfunction "PJ15/LCD_B3/EVENTOUT_B10") (pintype "bidirectional"))
    )
    (net (code "96") (name "/LCD_B4 {slash} PK3") (class "Default")
      (node (ref "RP6") (pin "1") (pintype "passive"))
      (node (ref "U2") (pin "C8") (pinfunction "PK3/LCD_B4/EVENTOUT_C8") (pintype "bidirectional"))
    )
    (net (code "97") (name "/LCD_B5 {slash} PK4") (class "Default")
      (node (ref "RP6") (pin "2") (pintype "passive"))
      (node (ref "U2") (pin "B8") (pinfunction "PK4/LCD_B5/EVENTOUT_B8") (pintype "bidirectional"))
    )
    (net (code "98") (name "/LCD_B6 {slash} PK5") (class "Default")
      (node (ref "RP6") (pin "3") (pintype "passive"))
      (node (ref "U2") (pin "A8") (pinfunction "PK5/LCD_B6/EVENTOUT_A8") (pintype "bidirectional"))
    )
    (net (code "99") (name "/LCD_B7 {slash} PK6") (class "Default")
      (node (ref "RP6") (pin "4") (pintype "passive"))
      (node (ref "U2") (pin "C7") (pinfunction "PK6/LCD_B7/EVENTOUT_C7") (pintype "bidirectional"))
    )
    (net (code "100") (name "/LCD_BL {slash} PH6") (class "Default")
      (node (ref "R30") (pin "2") (pinfunction "2_2") (pintype "passive"))
      (node (ref "U2") (pin "T11") (pinfunction "PH6/TIM12_CH1/I2C2_SMBA/SPI5_SCK/ETH_MII_RXD2/FMC_SDNE1/DCMI_D8/EVENTOUT_T11") (pintype "bidirectional"))
    )
    (net (code "101") (name "/LCD_CLK {slash} PI14") (class "Default")
      (node (ref "RP7") (pin "1") (pintype "passive"))
      (node (ref "U2") (pin "H3") (pinfunction "PI14/LCD_CLK/EVENTOUT_H3") (pintype "bidirectional"))
    )
    (net (code "102") (name "/LCD_DE {slash} PK7") (class "Default")
      (node (ref "RP7") (pin "4") (pintype "passive"))
      (node (ref "U2") (pin "D7") (pinfunction "PK7/LCD_DE/EVENTOUT_D7") (pintype "bidirectional"))
    )
    (net (code "103") (name "/LCD_G0 {slash} PJ7") (class "Default")
      (node (ref "RP3") (pin "1") (pintype "passive"))
      (node (ref "U2") (pin "N14") (pinfunction "PJ7/TRGIN/TIM8_CH2N/LCD_G0/EVENTOUT_N14") (pintype "bidirectional"))
    )
    (net (code "104") (name "/LCD_G1 {slash} PJ8") (class "Default")
      (node (ref "RP3") (pin "2") (pintype "passive"))
      (node (ref "U2") (pin "N13") (pinfunction "PJ8/TIM1_CH3N/TIM8_CH1/UART8_TX/LCD_G1/EVENTOUT_N13") (pintype "bidirectional"))
    )
    (net (code "105") (name "/LCD_G2 {slash} PJ9") (class "Default")
      (node (ref "RP3") (pin "3") (pintype "passive"))
      (node (ref "U2") (pin "M14") (pinfunction "PJ9/TIM1_CH3/TIM8_CH1N/UART8_RX/LCD_G2/EVENTOUT_M14") (pintype "bidirectional"))
    )
    (net (code "106") (name "/LCD_G3 {slash} PJ10") (class "Default")
      (node (ref "RP3") (pin "4") (pintype "passive"))
      (node (ref "U2") (pin "L14") (pinfunction "PJ10/TIM1_CH2N/TIM8_CH2/SPI5_MOSI/LCD_G3/EVENTOUT_L14") (pintype "bidirectional"))
    )
    (net (code "107") (name "/LCD_G4 {slash} PJ11") (class "Default")
      (node (ref "RP4") (pin "1") (pintype "passive"))
      (node (ref "U2") (pin "K14") (pinfunction "PJ11/TIM1_CH2/TIM8_CH2N/SPI5_MISO/LCD_G4/EVENTOUT_K14") (pintype "bidirectional"))
    )
    (net (code "108") (name "/LCD_G5 {slash} PK0") (class "Default")
      (node (ref "RP4") (pin "2") (pintype "passive"))
      (node (ref "U2") (pin "J14") (pinfunction "PK0/TIM1_CH1N/TIM8_CH3/SPI5_SCK/LCD_G5/EVENTOUT_J14") (pintype "bidirectional"))
    )
    (net (code "109") (name "/LCD_G6 {slash} PK1") (class "Default")
      (node (ref "RP4") (pin "3") (pintype "passive"))
      (node (ref "U2") (pin "J15") (pinfunction "PK1/TIM1_CH1/TIM8_CH3N/SPI5_NSS/LCD_G6/EVENTOUT_J15") (pintype "bidirectional"))
    )
    (net (code "110") (name "/LCD_G7 {slash} PK2") (class "Default")
      (node (ref "RP4") (pin "4") (pintype "passive"))
      (node (ref "U2") (pin "H17") (pinfunction "PK2/TIM1_BKIN/TIM8_BKIN/TIM8_BKIN_COMP12/TIM1_BKIN_COMP12/LCD_G7/EVENTOUT_H17") (pintype "bidirectional"))
    )
    (net (code "111") (name "/LCD_HS {slash} PI12") (class "Default")
      (node (ref "RP7") (pin "2") (pintype "passive"))
      (node (ref "U2") (pin "H1") (pinfunction "PI12/LCD_HSYNC/EVENTOUT_H1") (pintype "bidirectional"))
    )
    (net (code "112") (name "/LCD_R0 {slash} PI15") (class "Default")
      (node (ref "RP1") (pin "1") (pintype "passive"))
      (node (ref "U2") (pin "P5") (pinfunction "PI15/LCD_G2/LCD_R0/EVENTOUT_P5") (pintype "bidirectional"))
    )
    (net (code "113") (name "/LCD_R1 {slash} PJ0") (class "Default")
      (node (ref "RP1") (pin "2") (pintype "passive"))
      (node (ref "U2") (pin "N6") (pinfunction "PJ0/LCD_R7/LCD_R1/EVENTOUT_N6") (pintype "bidirectional"))
    )
    (net (code "114") (name "/LCD_R2 {slash} PJ1") (class "Default")
      (node (ref "RP1") (pin "3") (pintype "passive"))
      (node (ref "U2") (pin "P6") (pinfunction "PJ1/LCD_R2/EVENTOUT_P6") (pintype "bidirectional"))
    )
    (net (code "115") (name "/LCD_R3 {slash} PJ2") (class "Default")
      (node (ref "RP1") (pin "4") (pintype "passive"))
      (node (ref "U2") (pin "T6") (pinfunction "PJ2/LCD_R3/EVENTOUT_T6") (pintype "bidirectional"))
    )
    (net (code "116") (name "/LCD_R4 {slash} PJ3") (class "Default")
      (node (ref "RP2") (pin "1") (pintype "passive"))
      (node (ref "U2") (pin "U6") (pinfunction "PJ3/LCD_R4/EVENTOUT_U6") (pintype "bidirectional"))
    )
    (net (code "117") (name "/LCD_R5 {slash} PJ4") (class "Default")
      (node (ref "RP2") (pin "2") (pintype "passive"))
      (node (ref "U2") (pin "U7") (pinfunction "PJ4/LCD_R5/EVENTOUT_U7") (pintype "bidirectional"))
    )
    (net (code "118") (name "/LCD_R6 {slash} PJ5") (class "Default")
      (node (ref "RP2") (pin "3") (pintype "passive"))
      (node (ref "U2") (pin "R12") (pinfunction "PJ5/LCD_R6/EVENTOUT_R12") (pintype "bidirectional"))
    )
    (net (code "119") (name "/LCD_R7 {slash} PJ6") (class "Default")
      (node (ref "RP2") (pin "4") (pintype "passive"))
      (node (ref "U2") (pin "N15") (pinfunction "PJ6/TIM8_CH2/LCD_R7/EVENTOUT_N15") (pintype "bidirectional"))
    )
    (net (code "120") (name "/LCD_VS {slash} PI13") (class "Default")
      (node (ref "RP7") (pin "3") (pintype "passive"))
      (node (ref "U2") (pin "H2") (pinfunction "PI13/LCD_VSYNC/EVENTOUT_H2") (pintype "bidirectional"))
    )
    (net (code "121") (name "/LED {slash} PC13") (class "Default")
      (node (ref "LED5") (pin "2") (pinfunction "K_2") (pintype "passive"))
      (node (ref "U2") (pin "E3") (pinfunction "PC13/EVENTOUT_E3") (pintype "bidirectional"))
    )
    (net (code "122") (name "/LED+") (class "Default")
      (node (ref "7") (pin "2") (pinfunction "2_2") (pintype "passive"))
      (node (ref "D1") (pin "2") (pinfunction "K_2") (pintype "passive"))
      (node (ref "U10") (pin "39") (pinfunction "39_39") (pintype "passive"))
    )
    (net (code "123") (name "/LED-") (class "Default")
      (node (ref "R29") (pin "1") (pinfunction "1_1") (pintype "passive"))
      (node (ref "R33") (pin "1") (pinfunction "1_1") (pintype "passive"))
      (node (ref "U10") (pin "40") (pinfunction "40_40") (pintype "passive"))
    )
    (net (code "124") (name "/OS_25M_IN") (class "Default")
      (node (ref "C39") (pin "2") (pinfunction "2_2") (pintype "passive"))
      (node (ref "U2") (pin "J2") (pinfunction "PH0-OSC_IN(PH0)/EVENTOUT_J2") (pintype "bidirectional"))
      (node (ref "X2") (pin "3") (pinfunction "3_3") (pintype "passive"))
    )
    (net (code "125") (name "/OS_25M_OUT") (class "Default")
      (node (ref "C38") (pin "2") (pinfunction "2_2") (pintype "passive"))
      (node (ref "U2") (pin "J1") (pinfunction "PH1-OSC_OUT(PH1)/EVENTOUT_J1") (pintype "bidirectional"))
      (node (ref "X2") (pin "1") (pinfunction "1_1") (pintype "passive"))
    )
    (net (code "126") (name "/OS_32K_IN") (class "Default")
      (node (ref "C40") (pin "1") (pinfunction "1_1") (pintype "passive"))
      (node (ref "U2") (pin "C2") (pinfunction "PC14-OSC32_IN/EVENTOUT_C2") (pintype "bidirectional"))
      (node (ref "X3") (pin "2") (pinfunction "2_2") (pintype "passive"))
    )
    (net (code "127") (name "/OS_32K_OUT") (class "Default")
      (node (ref "C41") (pin "1") (pinfunction "1_1") (pintype "passive"))
      (node (ref "U2") (pin "C1") (pinfunction "PC15-OSC32_OUT/EVENTOUT_C1") (pintype "bidirectional"))
      (node (ref "X3") (pin "1") (pinfunction "1_1") (pintype "passive"))
    )
    (net (code "128") (name "/PA9") (class "Default")
      (node (ref "JP1") (pin "8") (pinfunction "8_8") (pintype "passive"))
      (node (ref "R10") (pin "2") (pinfunction "2_2") (pintype "passive"))
      (node (ref "U2") (pin "D15") (pinfunction "PA9/TIM1_CH2/HRTIM_CHC1/LPUART1_TX/I2C3_SMBA/SPI2_SCK/I2S2_CK/USART1_TX/FDCAN1_RXFD_MODE/DCMI_D0/LCD_R5/EVENTOUT_D15") (pintype "bidirectional"))
    )
    (net (code "129") (name "/PA10") (class "Default")
      (node (ref "JP1") (pin "6") (pinfunction "6_6") (pintype "passive"))
      (node (ref "R9") (pin "2") (pinfunction "2_2") (pintype "passive"))
      (node (ref "U2") (pin "D14") (pinfunction "PA10/TIM1_CH3/HRTIM_CHC2/LPUART1_RX/USART1_RX/FDCAN1_TXFD_MODE/OTG_FS_ID/MDIOS_MDIO/LCD_B4/DCMI_D1/LCD_B1/EVENTOUT_D14") (pintype "bidirectional"))
    )
    (net (code "130") (name "/PA11") (class "Default")
      (node (ref "U2") (pin "E17") (pinfunction "PA11/TIM1_CH4/HRTIM_CHD1/LPUART1_CTS/SPI2_NSS/I2S2_WS/UART4_RX/USART1_CTS/USART1_NSS/FDCAN1_RX/OTG_FS_DM/LCD_R4/EVENTOUT_E17") (pintype "bidirectional"))
      (node (ref "U5") (pin "A7") (pinfunction "DN1_A7") (pintype "passive"))
      (node (ref "U5") (pin "B7") (pinfunction "DN2_B7") (pintype "passive"))
    )
    (net (code "131") (name "/PA12") (class "Default")
      (node (ref "U2") (pin "E16") (pinfunction "PA12/TIM1_ETR/HRTIM_CHD2/LPUART1_RTS/LPUART1_DE/SPI2_SCK/I2S2_CK/UART4_TX/USART1_RTS/USART1_DE/SAI2_FS_B/FDCAN1_TX/OTG_FS_DP/LCD_R5/EVENTOUT_E16") (pintype "bidirectional"))
      (node (ref "U5") (pin "A6") (pinfunction "DP1_A6") (pintype "passive"))
      (node (ref "U5") (pin "B6") (pinfunction "DP2_B6") (pintype "passive"))
    )
    (net (code "132") (name "/PB13") (class "Default")
      (node (ref "R24") (pin "2") (pinfunction "2_2") (pintype "passive"))
      (node (ref "SW1") (pin "2") (pinfunction "2_2") (pintype "passive"))
      (node (ref "U2") (pin "U14") (pinfunction "PB13/TIM1_CH1N/LPTIM2_OUT/SPI2_SCK/I2S2_CK/DFSDM1_CKIN1/USART3_CTS/USART3_NSS/FDCAN2_TX/OTG_HS_ULPI_D6/ETH_MII_TXD1/ETH_RMII_TXD1/UART5_TX/EVENTOUT_U14") (pintype "bidirectional"))
    )
    (net (code "133") (name "/PC8") (class "Default")
      (node (ref "P1") (pin "7") (pinfunction "DATA_0_7") (pintype "passive"))
      (node (ref "R20") (pin "2") (pinfunction "2_2") (pintype "passive"))
      (node (ref "U2") (pin "E13") (pinfunction "PC8/TRACED1/HRTIM_CHB1/TIM3_CH3/TIM8_CH3/USART6_CK/UART5_RTS/UART5_DE/FMC_NE2/FMC_NCE/SWPMI_RX/SDMMC1_D0/DCMI_D2/EVENTOUT_E13") (pintype "bidirectional"))
    )
    (net (code "134") (name "/PC9") (class "Default")
      (node (ref "P1") (pin "8") (pinfunction "DATA_1_8") (pintype "passive"))
      (node (ref "R19") (pin "2") (pinfunction "2_2") (pintype "passive"))
      (node (ref "U2") (pin "E14") (pinfunction "PC9/MCO2/TIM3_CH4/TIM8_CH4/I2C3_SDA/I2S_CKIN/UART5_CTS/QUADSPI_BK1_IO0/LCD_G3/SWPMI_SUSPEND/SDMMC1_D1/DCMI_D3/LCD_B2/EVENTOUT_E14") (pintype "bidirectional"))
    )
    (net (code "135") (name "/PC10") (class "Default")
      (node (ref "P1") (pin "1") (pinfunction "DATA_2_1") (pintype "passive"))
      (node (ref "R23") (pin "2") (pinfunction "2_2") (pintype "passive"))
      (node (ref "U2") (pin "A13") (pinfunction "PC10/HRTIM_EEV1/DFSDM1_CKIN5/SPI3_SCK/I2S3_CK/USART3_TX/UART4_TX/QUADSPI_BK1_IO1/SDMMC1_D2/DCMI_D8/LCD_R2/EVENTOUT_A13") (pintype "bidirectional"))
    )
    (net (code "136") (name "/PC11") (class "Default")
      (node (ref "P1") (pin "2") (pinfunction "DATA_3_2") (pintype "passive"))
      (node (ref "R22") (pin "2") (pinfunction "2_2") (pintype "passive"))
      (node (ref "U2") (pin "B13") (pinfunction "PC11/HRTIM_FLT2/DFSDM1_DATIN5/SPI3_MISO/I2S3_SDI/USART3_RX/UART4_RX/QUADSPI_BK2_NCS/SDMMC1_D3/DCMI_D4/EVENTOUT_B13") (pintype "bidirectional"))
    )
    (net (code "137") (name "/PC12") (class "Default")
      (node (ref "P1") (pin "5") (pinfunction "CLK_5") (pintype "passive"))
      (node (ref "U2") (pin "C12") (pinfunction "PC12/TRACED3/HRTIM_EEV2/SPI3_MOSI/I2S3_SDO/USART3_CK/UART5_TX/SDMMC1_CK/DCMI_D9/EVENTOUT_C12") (pintype "bidirectional"))
    )
    (net (code "138") (name "/PD2") (class "Default")
      (node (ref "P1") (pin "3") (pinfunction "CMD_3") (pintype "passive"))
      (node (ref "R21") (pin "2") (pinfunction "2_2") (pintype "passive"))
      (node (ref "U2") (pin "D12") (pinfunction "PD2/TRACED2/TIM3_ETR/UART5_RX/SDMMC1_CMD/DCMI_D11/EVENTOUT_D12") (pintype "bidirectional"))
    )
    (net (code "139") (name "/PI8") (class "Default")
      (node (ref "R47") (pin "1") (pinfunction "1_1") (pintype "passive"))
      (node (ref "U2") (pin "E4") (pinfunction "PI8/EVENTOUT_E4") (pintype "bidirectional"))
    )
    (net (code "140") (name "/PI11") (class "Default")
      (node (ref "R46") (pin "1") (pinfunction "1_1") (pintype "passive"))
      (node (ref "U2") (pin "F4") (pinfunction "PI11/LCD_G6/OTG_HS_ULPI_DIR/EVENTOUT_F4") (pintype "bidirectional"))
    )
    (net (code "141") (name "/QSPI_BK1_IO0 {slash} PF8") (class "Default")
      (node (ref "U2") (pin "K4") (pinfunction "PF8/TIM16_CH1N/SPI5_MISO/SAI1_SCK_B/UART7_RTS/UART7_DE/SAI4_SCK_B/TIM13_CH1/QUADSPI_BK1_IO0/EVENTOUT_K4") (pintype "bidirectional"))
      (node (ref "U6") (pin "5") (pinfunction "DI(IO0)_5") (pintype "passive"))
    )
    (net (code "142") (name "/QSPI_BK1_IO1 {slash} PF9") (class "Default")
      (node (ref "U2") (pin "L4") (pinfunction "PF9/TIM17_CH1N/SPI5_MOSI/SAI1_FS_B/UART7_CTS/SAI4_FS_B/TIM14_CH1/QUADSPI_BK1_IO1/EVENTOUT_L4") (pintype "bidirectional"))
      (node (ref "U6") (pin "2") (pinfunction "DO(IO1)_2") (pintype "passive"))
    )
    (net (code "143") (name "/QSPI_BK1_IO2 {slash} PF7") (class "Default")
      (node (ref "U2") (pin "K3") (pinfunction "PF7/TIM17_CH1/SPI5_SCK/SAI1_MCLK_B/UART7_TX/SAI4_MCLK_B/QUADSPI_BK1_IO2/EVENTOUT_K3") (pintype "bidirectional"))
      (node (ref "U6") (pin "3") (pinfunction "WP#(IO2)_3") (pintype "passive"))
    )
    (net (code "144") (name "/QSPI_BK1_IO3 {slash} PF6") (class "Default")
      (node (ref "U2") (pin "K2") (pinfunction "PF6/TIM16_CH1/SPI5_NSS/SAI1_SD_B/UART7_RX/SAI4_SD_B/QUADSPI_BK1_IO3/EVENTOUT_K2") (pintype "bidirectional"))
      (node (ref "U6") (pin "7") (pinfunction "HOLDor#/RESET#(IO3)_7") (pintype "passive"))
    )
    (net (code "145") (name "/QSPI_BK1_NCS {slash} PG6") (class "Default")
      (node (ref "U2") (pin "G15") (pinfunction "PG6/TIM17_BKIN/HRTIM_CHE1/QUADSPI_BK1_NCS/FMC_NE3/DCMI_D12/LCD_R7/EVENTOUT_G15") (pintype "bidirectional"))
      (node (ref "U6") (pin "1") (pinfunction "CS#_1") (pintype "passive"))
    )
    (net (code "146") (name "/QSPI_CLK {slash} PF10") (class "Default")
      (node (ref "U2") (pin "L3") (pinfunction "PF10/TIM16_BKIN/SAI1_D3/QUADSPI_CLK/SAI4_D3/DCMI_D11/LCD_DE/EVENTOUT_L3") (pintype "bidirectional"))
      (node (ref "U6") (pin "6") (pinfunction "CLK_6") (pintype "passive"))
    )
    (net (code "147") (name "/RST") (class "Default")
      (node (ref "C36") (pin "1") (pinfunction "1_1") (pintype "passive"))
      (node (ref "JP1") (pin "10") (pinfunction "10_10") (pintype "passive"))
      (node (ref "Q1") (pin "3") (pinfunction "C_3") (pintype "passive"))
      (node (ref "R11") (pin "2") (pinfunction "2_2") (pintype "passive"))
      (node (ref "R25") (pin "1") (pinfunction "1_1") (pintype "passive"))
      (node (ref "SW3") (pin "1") (pinfunction "1_1") (pintype "passive"))
      (node (ref "U2") (pin "K1") (pinfunction "NRST_K1") (pintype "bidirectional"))
    )
    (net (code "148") (name "/SWCLK {slash} PA14") (class "Default")
      (node (ref "JP1") (pin "4") (pinfunction "4_4") (pintype "passive"))
      (node (ref "R8") (pin "2") (pinfunction "2_2") (pintype "passive"))
      (node (ref "U2") (pin "B14") (pinfunction "PA14/JTCK-SWCLK/EVENTOUT_B14") (pintype "bidirectional"))
    )
    (net (code "149") (name "/SWDIO {slash} PA13") (class "Default")
      (node (ref "JP1") (pin "2") (pinfunction "2_2") (pintype "passive"))
      (node (ref "R7") (pin "2") (pinfunction "2_2") (pintype "passive"))
      (node (ref "U2") (pin "C15") (pinfunction "PA13/JTMS-SWDIO/EVENTOUT_C15") (pintype "bidirectional"))
    )
    (net (code "150") (name "/VBAT") (class "Default")
      (node (ref "C47") (pin "1") (pinfunction "1_1") (pintype "passive"))
      (node (ref "D5") (pin "3") (pinfunction "3_3") (pintype "passive"))
      (node (ref "U2") (pin "B1") (pinfunction "VBAT_B1") (pintype "power_in"))
    )
    (net (code "151") (name "/VBAT-EXT") (class "Default")
      (node (ref "D5") (pin "1") (pinfunction "1_1") (pintype "passive"))
      (node (ref "JP2") (pin "4") (pinfunction "4_4") (pintype "passive"))
    )
    (net (code "152") (name "/VDDA") (class "Default")
      (node (ref "C43") (pin "2") (pinfunction "2_2") (pintype "passive"))
      (node (ref "C44") (pin "2") (pinfunction "2_2") (pintype "passive"))
      (node (ref "FB4") (pin "2") (pinfunction "2_2") (pintype "passive"))
      (node (ref "R36") (pin "1") (pinfunction "1_1") (pintype "passive"))
      (node (ref "U2") (pin "L1") (pinfunction "VDDA_L1") (pintype "power_in"))
    )
    (net (code "153") (name "/VREF") (class "Default")
      (node (ref "C45") (pin "2") (pinfunction "2_2") (pintype "passive"))
      (node (ref "C46") (pin "2") (pinfunction "2_2") (pintype "passive"))
      (node (ref "JP2") (pin "2") (pinfunction "2_2") (pintype "passive"))
      (node (ref "R36") (pin "2") (pinfunction "2_2") (pintype "passive"))
      (node (ref "U2") (pin "M1") (pinfunction "VREF+_M1") (pintype "input"))
    )
    (net (code "154") (name "AF-2.8V") (class "Default")
      (node (ref "14") (pin "2") (pinfunction "2_2") (pintype "passive"))
      (node (ref "15") (pin "2") (pinfunction "2_2") (pintype "passive"))
      (node (ref "IC1") (pin "23") (pinfunction "AF-VCC_23") (pintype "passive"))
      (node (ref "U8") (pin "2") (pinfunction "VOUT_2") (pintype "passive"))
    )
    (net (code "155") (name "GND") (class "Default")
      (node (ref "1") (pin "1") (pinfunction "1_1") (pintype "passive"))
      (node (ref "10") (pin "1") (pinfunction "1_1") (pintype "passive"))
      (node (ref "11") (pin "1") (pinfunction "1_1") (pintype "passive"))
      (node (ref "12") (pin "1") (pinfunction "1_1") (pintype "passive"))
      (node (ref "13") (pin "1") (pinfunction "1_1") (pintype "passive"))
      (node (ref "14") (pin "1") (pinfunction "1_1") (pintype "passive"))
      (node (ref "15") (pin "1") (pinfunction "1_1") (pintype "passive"))
      (node (ref "16") (pin "1") (pinfunction "1_1") (pintype "passive"))
      (node (ref "17") (pin "1") (pinfunction "1_1") (pintype "passive"))
      (node (ref "18") (pin "1") (pinfunction "1_1") (pintype "passive"))
      (node (ref "19") (pin "1") (pinfunction "1_1") (pintype "passive"))
      (node (ref "2") (pin "1") (pinfunction "1_1") (pintype "passive"))
      (node (ref "20") (pin "1") (pinfunction "1_1") (pintype "passive"))
      (node (ref "21") (pin "1") (pinfunction "1_1") (pintype "passive"))
      (node (ref "22") (pin "1") (pinfunction "1_1") (pintype "passive"))
      (node (ref "23") (pin "1") (pinfunction "1_1") (pintype "passive"))
      (node (ref "24") (pin "1") (pinfunction "1_1") (pintype "passive"))
      (node (ref "25") (pin "1") (pinfunction "1_1") (pintype "passive"))
      (node (ref "26") (pin "1") (pinfunction "1_1") (pintype "passive"))
      (node (ref "27") (pin "1") (pinfunction "1_1") (pintype "passive"))
      (node (ref "28") (pin "1") (pinfunction "1_1") (pintype "passive"))
      (node (ref "29") (pin "1") (pinfunction "1_1") (pintype "passive"))
      (node (ref "3") (pin "1") (pinfunction "1_1") (pintype "passive"))
      (node (ref "4") (pin "1") (pinfunction "1_1") (pintype "passive"))
      (node (ref "5") (pin "1") (pinfunction "1_1") (pintype "passive"))
      (node (ref "6") (pin "1") (pinfunction "1_1") (pintype "passive"))
      (node (ref "7") (pin "1") (pinfunction "1_1") (pintype "passive"))
      (node (ref "9") (pin "1") (pinfunction "1_1") (pintype "passive"))
      (node (ref "C1") (pin "1") (pinfunction "1_1") (pintype "passive"))
      (node (ref "C10") (pin "1") (pinfunction "1_1") (pintype "passive"))
      (node (ref "C11") (pin "1") (pinfunction "1_1") (pintype "passive"))
      (node (ref "C12") (pin "1") (pinfunction "1_1") (pintype "passive"))
      (node (ref "C13") (pin "1") (pinfunction "1_1") (pintype "passive"))
      (node (ref "C14") (pin "1") (pinfunction "1_1") (pintype "passive"))
      (node (ref "C15") (pin "1") (pinfunction "1_1") (pintype "passive"))
      (node (ref "C16") (pin "1") (pinfunction "1_1") (pintype "passive"))
      (node (ref "C17") (pin "1") (pinfunction "1_1") (pintype "passive"))
      (node (ref "C18") (pin "1") (pinfunction "1_1") (pintype "passive"))
      (node (ref "C19") (pin "1") (pinfunction "1_1") (pintype "passive"))
      (node (ref "C2") (pin "1") (pinfunction "1_1") (pintype "passive"))
      (node (ref "C20") (pin "1") (pinfunction "1_1") (pintype "passive"))
      (node (ref "C21") (pin "1") (pinfunction "1_1") (pintype "passive"))
      (node (ref "C22") (pin "1") (pinfunction "1_1") (pintype "passive"))
      (node (ref "C23") (pin "1") (pinfunction "1_1") (pintype "passive"))
      (node (ref "C24") (pin "1") (pinfunction "1_1") (pintype "passive"))
      (node (ref "C25") (pin "1") (pinfunction "1_1") (pintype "passive"))
      (node (ref "C26") (pin "1") (pinfunction "1_1") (pintype "passive"))
      (node (ref "C27") (pin "1") (pinfunction "1_1") (pintype "passive"))
      (node (ref "C28") (pin "1") (pinfunction "1_1") (pintype "passive"))
      (node (ref "C29") (pin "1") (pinfunction "1_1") (pintype "passive"))
      (node (ref "C3") (pin "1") (pinfunction "1_1") (pintype "passive"))
      (node (ref "C30") (pin "1") (pinfunction "1_1") (pintype "passive"))
      (node (ref "C31") (pin "1") (pinfunction "1_1") (pintype "passive"))
      (node (ref "C32") (pin "1") (pinfunction "1_1") (pintype "passive"))
      (node (ref "C33") (pin "1") (pinfunction "1_1") (pintype "passive"))
      (node (ref "C34") (pin "1") (pinfunction "1_1") (pintype "passive"))
      (node (ref "C35") (pin "1") (pinfunction "1_1") (pintype "passive"))
      (node (ref "C36") (pin "2") (pinfunction "2_2") (pintype "passive"))
      (node (ref "C37") (pin "2") (pinfunction "2_2") (pintype "passive"))
      (node (ref "C38") (pin "1") (pinfunction "1_1") (pintype "passive"))
      (node (ref "C39") (pin "1") (pinfunction "1_1") (pintype "passive"))
      (node (ref "C4") (pin "2") (pinfunction "2_2") (pintype "passive"))
      (node (ref "C40") (pin "2") (pinfunction "2_2") (pintype "passive"))
      (node (ref "C41") (pin "2") (pinfunction "2_2") (pintype "passive"))
      (node (ref "C42") (pin "2") (pinfunction "2_2") (pintype "passive"))
      (node (ref "C43") (pin "1") (pinfunction "1_1") (pintype "passive"))
      (node (ref "C44") (pin "1") (pinfunction "1_1") (pintype "passive"))
      (node (ref "C45") (pin "1") (pinfunction "1_1") (pintype "passive"))
      (node (ref "C46") (pin "1") (pinfunction "1_1") (pintype "passive"))
      (node (ref "C47") (pin "2") (pinfunction "2_2") (pintype "passive"))
      (node (ref "C48") (pin "1") (pinfunction "1_1") (pintype "passive"))
      (node (ref "C5") (pin "2") (pinfunction "2_2") (pintype "passive"))
      (node (ref "C51") (pin "2") (pinfunction "2_2") (pintype "passive"))
      (node (ref "C6") (pin "2") (pinfunction "2_2") (pintype "passive"))
      (node (ref "C7") (pin "2") (pinfunction "2_2") (pintype "passive"))
      (node (ref "C8") (pin "2") (pinfunction "2_2") (pintype "passive"))
      (node (ref "C9") (pin "1") (pinfunction "1_1") (pintype "passive"))
      (node (ref "D2") (pin "1") (pinfunction "A_1") (pintype "passive"))
      (node (ref "D4") (pin "1") (pinfunction "A_1") (pintype "passive"))
      (node (ref "E1") (pin "2") (pinfunction "2_2") (pintype "passive"))
      (node (ref "E2") (pin "2") (pinfunction "2_2") (pintype "passive"))
      (node (ref "E3") (pin "2") (pinfunction "2_2") (pintype "passive"))
      (node (ref "IC1") (pin "1") (pinfunction "STROBE_1") (pintype "passive"))
      (node (ref "IC1") (pin "15") (pinfunction "DGND_15") (pintype "passive"))
      (node (ref "IC1") (pin "2") (pinfunction "AGND_2") (pintype "passive"))
      (node (ref "IC1") (pin "24") (pinfunction "AF-GND_24") (pintype "passive"))
      (node (ref "JP2") (pin "1") (pinfunction "1_1") (pintype "passive"))
      (node (ref "JP2") (pin "6") (pinfunction "6_6") (pintype "passive"))
      (node (ref "JP3") (pin "0") (pinfunction "0_0") (pintype "passive"))
      (node (ref "JP3") (pin "4") (pinfunction "4_4") (pintype "passive"))
      (node (ref "LED1") (pin "2") (pinfunction "K_2") (pintype "passive"))
      (node (ref "LED2") (pin "2") (pinfunction "K_2") (pintype "passive"))
      (node (ref "LED3") (pin "2") (pinfunction "K_2") (pintype "passive"))
      (node (ref "LED4") (pin "2") (pinfunction "K_2") (pintype "passive"))
      (node (ref "P1") (pin "6") (pinfunction "VSS_6") (pintype "passive"))
      (node (ref "Q1") (pin "2") (pinfunction "E_2") (pintype "passive"))
      (node (ref "R2") (pin "1") (pinfunction "1_1") (pintype "passive"))
      (node (ref "R24") (pin "1") (pinfunction "1_1") (pintype "passive"))
      (node (ref "R27") (pin "1") (pinfunction "1_1") (pintype "passive"))
      (node (ref "R28") (pin "1") (pinfunction "1_1") (pintype "passive"))
      (node (ref "R32") (pin "2") (pinfunction "2_2") (pintype "passive"))
      (node (ref "R33") (pin "2") (pinfunction "2_2") (pintype "passive"))
      (node (ref "R34") (pin "1") (pinfunction "1_1") (pintype "passive"))
      (node (ref "R5") (pin "1") (pinfunction "1_1") (pintype "passive"))
      (node (ref "R50") (pin "2") (pinfunction "2_2") (pintype "passive"))
      (node (ref "R55") (pin "2") (pinfunction "2_2") (pintype "passive"))
      (node (ref "SW3") (pin "2") (pinfunction "2_2") (pintype "passive"))
      (node (ref "U10") (pin "12") (pinfunction "12_12") (pintype "passive"))
      (node (ref "U10") (pin "38") (pinfunction "38_38") (pintype "passive"))
      (node (ref "U10") (pin "41") (pinfunction "41_41") (pintype "passive"))
      (node (ref "U10") (pin "42") (pinfunction "42_42") (pintype "passive"))
      (node (ref "U10") (pin "5") (pinfunction "5_5") (pintype "passive"))
      (node (ref "U11") (pin "21") (pinfunction "GND_21") (pintype "passive"))
      (node (ref "U2") (pin "A1") (pinfunction "VSS_1_A1") (pintype "power_in"))
      (node (ref "U2") (pin "A17") (pinfunction "VSS_1_A17") (pintype "power_in"))
      (node (ref "U2") (pin "B2") (pinfunction "VSS_1_B2") (pintype "power_in"))
      (node (ref "U2") (pin "B6") (pinfunction "VSS_1_B6") (pintype "power_in"))
      (node (ref "U2") (pin "C10") (pinfunction "VSS_1_C10") (pintype "power_in"))
      (node (ref "U2") (pin "C13") (pinfunction "VSS_1_C13") (pintype "power_in"))
      (node (ref "U2") (pin "C16") (pinfunction "VSS_1_C16") (pintype "power_in"))
      (node (ref "U2") (pin "F2") (pinfunction "VSS_1_F2") (pintype "power_in"))
      (node (ref "U2") (pin "G10") (pinfunction "VSS_2_G10") (pintype "power_in"))
      (node (ref "U2") (pin "G11") (pinfunction "VSS_2_G11") (pintype "power_in"))
      (node (ref "U2") (pin "G16") (pinfunction "VSS_2_G16") (pintype "power_in"))
      (node (ref "U2") (pin "G7") (pinfunction "VSS_2_G7") (pintype "power_in"))
      (node (ref "U2") (pin "G8") (pinfunction "VSS_2_G8") (pintype "power_in"))
      (node (ref "U2") (pin "G9") (pinfunction "VSS_2_G9") (pintype "power_in"))
      (node (ref "U2") (pin "H10") (pinfunction "VSS_2_H10") (pintype "power_in"))
      (node (ref "U2") (pin "H11") (pinfunction "VSS_3_H11") (pintype "power_in"))
      (node (ref "U2") (pin "H7") (pinfunction "VSS_2_H7") (pintype "power_in"))
      (node (ref "U2") (pin "H8") (pinfunction "VSS_2_H8") (pintype "power_in"))
      (node (ref "U2") (pin "H9") (pinfunction "VSS_2_H9") (pintype "power_in"))
      (node (ref "U2") (pin "J10") (pinfunction "VSS_3_J10") (pintype "power_in"))
      (node (ref "U2") (pin "J11") (pinfunction "VSS_3_J11") (pintype "power_in"))
      (node (ref "U2") (pin "J16") (pinfunction "VSS_1_J16") (pintype "power_in"))
      (node (ref "U2") (pin "J17") (pinfunction "VSS_1_J17") (pintype "power_in"))
      (node (ref "U2") (pin "J3") (pinfunction "VSS_1_J3") (pintype "power_in"))
      (node (ref "U2") (pin "J7") (pinfunction "VSS_3_J7") (pintype "power_in"))
      (node (ref "U2") (pin "J8") (pinfunction "VSS_3_J8") (pintype "power_in"))
      (node (ref "U2") (pin "J9") (pinfunction "VSS_3_J9") (pintype "power_in"))
      (node (ref "U2") (pin "K10") (pinfunction "VSS_3_K10") (pintype "power_in"))
      (node (ref "U2") (pin "K11") (pinfunction "VSS_3_K11") (pintype "power_in"))
      (node (ref "U2") (pin "K15") (pinfunction "VSS_2_K15") (pintype "power_in"))
      (node (ref "U2") (pin "K7") (pinfunction "VSS_3_K7") (pintype "power_in"))
      (node (ref "U2") (pin "K8") (pinfunction "VSS_3_K8") (pintype "power_in"))
      (node (ref "U2") (pin "K9") (pinfunction "VSS_3_K9") (pintype "power_in"))
      (node (ref "U2") (pin "L10") (pinfunction "VSS_3_L10") (pintype "power_in"))
      (node (ref "U2") (pin "L11") (pinfunction "VSS_3_L11") (pintype "power_in"))
      (node (ref "U2") (pin "L15") (pinfunction "VSS_2_L15") (pintype "power_in"))
      (node (ref "U2") (pin "L7") (pinfunction "VSS_3_L7") (pintype "power_in"))
      (node (ref "U2") (pin "L8") (pinfunction "VSS_3_L8") (pintype "power_in"))
      (node (ref "U2") (pin "L9") (pinfunction "VSS_3_L9") (pintype "power_in"))
      (node (ref "U2") (pin "M15") (pinfunction "VSS_2_M15") (pintype "power_in"))
      (node (ref "U2") (pin "N1") (pinfunction "VREF-_N1") (pintype "input"))
      (node (ref "U2") (pin "N16") (pinfunction "VSS_1_N16") (pintype "power_in"))
      (node (ref "U2") (pin "P1") (pinfunction "VSSA_P1") (pintype "power_in"))
      (node (ref "U2") (pin "R4") (pinfunction "VSS_1_R4") (pintype "power_in"))
      (node (ref "U2") (pin "R8") (pinfunction "VSS_2_R8") (pintype "power_in"))
      (node (ref "U2") (pin "T12") (pinfunction "VSS_1_T12") (pintype "power_in"))
      (node (ref "U2") (pin "U1") (pinfunction "VSS_2_U1") (pintype "power_in"))
      (node (ref "U2") (pin "U17") (pinfunction "VSS_1_U17") (pintype "power_in"))
      (node (ref "U3") (pin "A3") (pinfunction "VSS_A3") (pintype "power_in"))
      (node (ref "U3") (pin "B3") (pinfunction "VSSQ_B3") (pintype "power_in"))
      (node (ref "U3") (pin "B8") (pinfunction "VSSQ_B8") (pintype "power_in"))
      (node (ref "U3") (pin "C1") (pinfunction "VSSQ_C1") (pintype "power_in"))
      (node (ref "U3") (pin "D1") (pinfunction "VSSQ_D1") (pintype "power_in"))
      (node (ref "U3") (pin "E9") (pinfunction "VSSQ_E9") (pintype "power_in"))
      (node (ref "U3") (pin "F1") (pinfunction "VSS_F1") (pintype "power_in"))
      (node (ref "U3") (pin "L3") (pinfunction "VSS_L3") (pintype "power_in"))
      (node (ref "U3") (pin "L9") (pinfunction "VSSQ_L9") (pintype "power_in"))
      (node (ref "U3") (pin "M1") (pinfunction "VSSQ_M1") (pintype "power_in"))
      (node (ref "U3") (pin "N1") (pinfunction "VSSQ_N1") (pintype "power_in"))
      (node (ref "U3") (pin "P3") (pinfunction "VSSQ_P3") (pintype "power_in"))
      (node (ref "U3") (pin "P8") (pinfunction "VSSQ_P8") (pintype "power_in"))
      (node (ref "U3") (pin "R3") (pinfunction "VSS_R3") (pintype "power_in"))
      (node (ref "U4") (pin "13") (pinfunction "13_13") (pintype "passive"))
      (node (ref "U4") (pin "14") (pinfunction "14_14") (pintype "passive"))
      (node (ref "U4") (pin "15") (pinfunction "15_15") (pintype "passive"))
      (node (ref "U4") (pin "16") (pinfunction "16_16") (pintype "passive"))
      (node (ref "U4") (pin "A1B12") (pinfunction "GND_A1B12") (pintype "passive"))
      (node (ref "U4") (pin "B1A12") (pinfunction "GND_B1A12") (pintype "passive"))
      (node (ref "U5") (pin "13") (pinfunction "13_13") (pintype "passive"))
      (node (ref "U5") (pin "14") (pinfunction "14_14") (pintype "passive"))
      (node (ref "U5") (pin "15") (pinfunction "15_15") (pintype "passive"))
      (node (ref "U5") (pin "16") (pinfunction "16_16") (pintype "passive"))
      (node (ref "U5") (pin "A1B12") (pinfunction "GND_A1B12") (pintype "passive"))
      (node (ref "U5") (pin "B1A12") (pinfunction "GND_B1A12") (pintype "passive"))
      (node (ref "U6") (pin "4") (pinfunction "GND_4") (pintype "passive"))
      (node (ref "U6") (pin "9") (pinfunction "EP_9") (pintype "passive"))
      (node (ref "U7") (pin "1") (pinfunction "VSS_1") (pintype "passive"))
      (node (ref "U8") (pin "1") (pinfunction "VSS_1") (pintype "passive"))
      (node (ref "U9") (pin "1") (pinfunction "VSS_1") (pintype "passive"))
      (node (ref "X2") (pin "2") (pinfunction "2_2") (pintype "passive"))
      (node (ref "X2") (pin "4") (pinfunction "4_4") (pintype "passive"))
      (node (ref "X4") (pin "2") (pinfunction "GND_2") (pintype "passive"))
    )
    (net (code "156") (name "Net-(8-FB)") (class "Default")
      (node (ref "8") (pin "3") (pinfunction "FB_3") (pintype "bidirectional"))
      (node (ref "R29") (pin "2") (pinfunction "2_2") (pintype "passive"))
    )
    (net (code "157") (name "Net-(8-GND)") (class "Default")
      (node (ref "8") (pin "2") (pinfunction "GND_2") (pintype "bidirectional"))
      (node (ref "R28") (pin "2") (pinfunction "2_2") (pintype "passive"))
    )
    (net (code "158") (name "Net-(8-SW)") (class "Default")
      (node (ref "8") (pin "1") (pinfunction "SW_1") (pintype "bidirectional"))
      (node (ref "D1") (pin "1") (pinfunction "A_1") (pintype "passive"))
      (node (ref "L1") (pin "1") (pinfunction "1_1") (pintype "passive"))
    )
    (net (code "159") (name "Net-(8-~{SHTDN!})") (class "Default")
      (node (ref "13") (pin "2") (pinfunction "2_2") (pintype "passive"))
      (node (ref "8") (pin "4") (pinfunction "~{SHTDN!}_4") (pintype "bidirectional"))
      (node (ref "R30") (pin "1") (pinfunction "1_1") (pintype "passive"))
      (node (ref "R32") (pin "1") (pinfunction "1_1") (pintype "passive"))
    )
    (net (code "160") (name "Net-(28-Pad2)") (class "Default")
      (node (ref "28") (pin "2") (pinfunction "2_2") (pintype "passive"))
      (node (ref "JP3") (pin "2") (pinfunction "2_2") (pintype "passive"))
      (node (ref "R45") (pin "2") (pinfunction "2_2") (pintype "passive"))
      (node (ref "R48") (pin "1") (pinfunction "1_1") (pintype "passive"))
    )
    (net (code "161") (name "Net-(29-Pad2)") (class "Default")
      (node (ref "29") (pin "2") (pinfunction "2_2") (pintype "passive"))
      (node (ref "JP3") (pin "1") (pinfunction "1_1") (pintype "passive"))
      (node (ref "R44") (pin "2") (pinfunction "2_2") (pintype "passive"))
      (node (ref "R51") (pin "1") (pinfunction "1_1") (pintype "passive"))
    )
    (net (code "162") (name "Net-(C1-Pad2)") (class "Default")
      (node (ref "C1") (pin "2") (pinfunction "2_2") (pintype "passive"))
      (node (ref "U2") (pin "A7") (pinfunction "VCAP_A7") (pintype "power_in"))
    )
    (net (code "163") (name "Net-(C2-Pad2)") (class "Default")
      (node (ref "C2") (pin "2") (pinfunction "2_2") (pintype "passive"))
      (node (ref "U2") (pin "D17") (pinfunction "VCAP_D17") (pintype "power_in"))
    )
    (net (code "164") (name "Net-(C3-Pad2)") (class "Default")
      (node (ref "C3") (pin "2") (pinfunction "2_2") (pintype "passive"))
      (node (ref "U2") (pin "U11") (pinfunction "VCAP_U11") (pintype "power_in"))
    )
    (net (code "165") (name "Net-(D3-A)") (class "Default")
      (node (ref "D3") (pin "1") (pinfunction "A_1") (pintype "passive"))
      (node (ref "R26") (pin "1") (pinfunction "1_1") (pintype "passive"))
      (node (ref "SW2") (pin "2") (pinfunction "2_2") (pintype "passive"))
    )
    (net (code "166") (name "Net-(D3-K)") (class "Default")
      (node (ref "C42") (pin "1") (pinfunction "1_1") (pintype "passive"))
      (node (ref "D3") (pin "2") (pinfunction "K_2") (pintype "passive"))
      (node (ref "Q2") (pin "1") (pinfunction "B_1") (pintype "passive"))
    )
    (net (code "167") (name "Net-(IC1-DOVDD)") (class "Default")
      (node (ref "21") (pin "2") (pinfunction "2_2") (pintype "passive"))
      (node (ref "22") (pin "2") (pinfunction "2_2") (pintype "passive"))
      (node (ref "FB6") (pin "2") (pinfunction "2_2") (pintype "passive"))
      (node (ref "IC1") (pin "11") (pinfunction "DOVDD_11") (pintype "passive"))
    )
    (net (code "168") (name "Net-(IC1-RESET)") (class "Default")
      (node (ref "24") (pin "2") (pinfunction "2_2") (pintype "passive"))
      (node (ref "IC1") (pin "6") (pinfunction "RESET_6") (pintype "passive"))
      (node (ref "R38") (pin "2") (pinfunction "2_2") (pintype "passive"))
    )
    (net (code "169") (name "Net-(IC1-SCL)") (class "Default")
      (node (ref "25") (pin "2") (pinfunction "2_2") (pintype "passive"))
      (node (ref "IC1") (pin "5") (pinfunction "SCL_5") (pintype "passive"))
      (node (ref "R40") (pin "1") (pinfunction "1_1") (pintype "passive"))
      (node (ref "R42") (pin "1") (pinfunction "1_1") (pintype "passive"))
    )
    (net (code "170") (name "Net-(IC1-SDA)") (class "Default")
      (node (ref "26") (pin "2") (pinfunction "2_2") (pintype "passive"))
      (node (ref "IC1") (pin "3") (pinfunction "SDA_3") (pintype "passive"))
      (node (ref "R41") (pin "1") (pinfunction "1_1") (pintype "passive"))
      (node (ref "R43") (pin "1") (pinfunction "1_1") (pintype "passive"))
    )
    (net (code "171") (name "Net-(IC1-XVCLK)") (class "Default")
      (node (ref "IC1") (pin "13") (pinfunction "XVCLK_13") (pintype "passive"))
      (node (ref "X4") (pin "3") (pinfunction "OUT_3") (pintype "passive"))
    )
    (net (code "172") (name "Net-(JP1-Pad1)") (class "Default")
      (node (ref "JP1") (pin "1") (pinfunction "1_1") (pintype "passive"))
      (node (ref "R13") (pin "2") (pinfunction "2_2") (pintype "passive"))
      (node (ref "R7") (pin "1") (pinfunction "1_1") (pintype "passive"))
    )
    (net (code "173") (name "Net-(JP1-Pad3)") (class "Default")
      (node (ref "JP1") (pin "3") (pinfunction "3_3") (pintype "passive"))
      (node (ref "R16") (pin "2") (pinfunction "2_2") (pintype "passive"))
      (node (ref "R8") (pin "1") (pinfunction "1_1") (pintype "passive"))
    )
    (net (code "174") (name "Net-(JP3-Pad3)") (class "Default")
      (node (ref "JP3") (pin "3") (pinfunction "3_3") (pintype "passive"))
      (node (ref "R46") (pin "2") (pinfunction "2_2") (pintype "passive"))
    )
    (net (code "175") (name "Net-(JP3-Pad6)") (class "Default")
      (node (ref "JP3") (pin "6") (pinfunction "6_6") (pintype "passive"))
      (node (ref "R47") (pin "2") (pinfunction "2_2") (pintype "passive"))
    )
    (net (code "176") (name "Net-(LED1-A)") (class "Default")
      (node (ref "LED1") (pin "1") (pinfunction "A_1") (pintype "passive"))
      (node (ref "R3") (pin "2") (pinfunction "2_2") (pintype "passive"))
    )
    (net (code "177") (name "Net-(LED2-A)") (class "Default")
      (node (ref "LED2") (pin "1") (pinfunction "A_1") (pintype "passive"))
      (node (ref "R6") (pin "2") (pinfunction "2_2") (pintype "passive"))
    )
    (net (code "178") (name "Net-(LED4-A)") (class "Default")
      (node (ref "LED4") (pin "1") (pinfunction "A_1") (pintype "passive"))
      (node (ref "R35") (pin "2") (pinfunction "2_2") (pintype "passive"))
    )
    (net (code "179") (name "Net-(LED5-A)") (class "Default")
      (node (ref "LED5") (pin "1") (pinfunction "A_1") (pintype "passive"))
      (node (ref "R37") (pin "2") (pinfunction "2_2") (pintype "passive"))
    )
    (net (code "180") (name "Net-(Q1-B)") (class "Default")
      (node (ref "C37") (pin "1") (pinfunction "1_1") (pintype "passive"))
      (node (ref "Q1") (pin "1") (pinfunction "B_1") (pintype "passive"))
      (node (ref "R26") (pin "2") (pinfunction "2_2") (pintype "passive"))
      (node (ref "R27") (pin "2") (pinfunction "2_2") (pintype "passive"))
    )
    (net (code "181") (name "Net-(Q2-C)") (class "Default")
      (node (ref "Q2") (pin "3") (pinfunction "C_3") (pintype "passive"))
      (node (ref "R31") (pin "1") (pinfunction "1_1") (pintype "passive"))
    )
    (net (code "182") (name "Net-(RP1-Pad5)") (class "Default")
      (node (ref "RP1") (pin "5") (pintype "passive"))
      (node (ref "U10") (pin "33") (pinfunction "33_33") (pintype "passive"))
    )
    (net (code "183") (name "Net-(RP1-Pad6)") (class "Default")
      (node (ref "RP1") (pin "6") (pintype "passive"))
      (node (ref "U10") (pin "34") (pinfunction "34_34") (pintype "passive"))
    )
    (net (code "184") (name "Net-(RP1-Pad7)") (class "Default")
      (node (ref "RP1") (pin "7") (pintype "passive"))
      (node (ref "U10") (pin "35") (pinfunction "35_35") (pintype "passive"))
    )
    (net (code "185") (name "Net-(RP1-Pad8)") (class "Default")
      (node (ref "RP1") (pin "8") (pintype "passive"))
      (node (ref "U10") (pin "36") (pinfunction "36_36") (pintype "passive"))
    )
    (net (code "186") (name "Net-(RP2-Pad5)") (class "Default")
      (node (ref "RP2") (pin "5") (pintype "passive"))
      (node (ref "U10") (pin "29") (pinfunction "29_29") (pintype "passive"))
    )
    (net (code "187") (name "Net-(RP2-Pad6)") (class "Default")
      (node (ref "RP2") (pin "6") (pintype "passive"))
      (node (ref "U10") (pin "30") (pinfunction "30_30") (pintype "passive"))
    )
    (net (code "188") (name "Net-(RP2-Pad7)") (class "Default")
      (node (ref "RP2") (pin "7") (pintype "passive"))
      (node (ref "U10") (pin "31") (pinfunction "31_31") (pintype "passive"))
    )
    (net (code "189") (name "Net-(RP2-Pad8)") (class "Default")
      (node (ref "RP2") (pin "8") (pintype "passive"))
      (node (ref "U10") (pin "32") (pinfunction "32_32") (pintype "passive"))
    )
    (net (code "190") (name "Net-(RP3-Pad5)") (class "Default")
      (node (ref "RP3") (pin "5") (pintype "passive"))
      (node (ref "U10") (pin "25") (pinfunction "25_25") (pintype "passive"))
    )
    (net (code "191") (name "Net-(RP3-Pad6)") (class "Default")
      (node (ref "RP3") (pin "6") (pintype "passive"))
      (node (ref "U10") (pin "26") (pinfunction "26_26") (pintype "passive"))
    )
    (net (code "192") (name "Net-(RP3-Pad7)") (class "Default")
      (node (ref "RP3") (pin "7") (pintype "passive"))
      (node (ref "U10") (pin "27") (pinfunction "27_27") (pintype "passive"))
    )
    (net (code "193") (name "Net-(RP3-Pad8)") (class "Default")
      (node (ref "RP3") (pin "8") (pintype "passive"))
      (node (ref "U10") (pin "28") (pinfunction "28_28") (pintype "passive"))
    )
    (net (code "194") (name "Net-(RP4-Pad5)") (class "Default")
      (node (ref "RP4") (pin "5") (pintype "passive"))
      (node (ref "U10") (pin "21") (pinfunction "21_21") (pintype "passive"))
    )
    (net (code "195") (name "Net-(RP4-Pad6)") (class "Default")
      (node (ref "RP4") (pin "6") (pintype "passive"))
      (node (ref "U10") (pin "22") (pinfunction "22_22") (pintype "passive"))
    )
    (net (code "196") (name "Net-(RP4-Pad7)") (class "Default")
      (node (ref "RP4") (pin "7") (pintype "passive"))
      (node (ref "U10") (pin "23") (pinfunction "23_23") (pintype "passive"))
    )
    (net (code "197") (name "Net-(RP4-Pad8)") (class "Default")
      (node (ref "RP4") (pin "8") (pintype "passive"))
      (node (ref "U10") (pin "24") (pinfunction "24_24") (pintype "passive"))
    )
    (net (code "198") (name "Net-(RP5-Pad5)") (class "Default")
      (node (ref "RP5") (pin "5") (pintype "passive"))
      (node (ref "U10") (pin "17") (pinfunction "17_17") (pintype "passive"))
    )
    (net (code "199") (name "Net-(RP5-Pad6)") (class "Default")
      (node (ref "RP5") (pin "6") (pintype "passive"))
      (node (ref "U10") (pin "18") (pinfunction "18_18") (pintype "passive"))
    )
    (net (code "200") (name "Net-(RP5-Pad7)") (class "Default")
      (node (ref "RP5") (pin "7") (pintype "passive"))
      (node (ref "U10") (pin "19") (pinfunction "19_19") (pintype "passive"))
    )
    (net (code "201") (name "Net-(RP5-Pad8)") (class "Default")
      (node (ref "RP5") (pin "8") (pintype "passive"))
      (node (ref "U10") (pin "20") (pinfunction "20_20") (pintype "passive"))
    )
    (net (code "202") (name "Net-(RP6-Pad5)") (class "Default")
      (node (ref "RP6") (pin "5") (pintype "passive"))
      (node (ref "U10") (pin "13") (pinfunction "13_13") (pintype "passive"))
    )
    (net (code "203") (name "Net-(RP6-Pad6)") (class "Default")
      (node (ref "RP6") (pin "6") (pintype "passive"))
      (node (ref "U10") (pin "14") (pinfunction "14_14") (pintype "passive"))
    )
    (net (code "204") (name "Net-(RP6-Pad7)") (class "Default")
      (node (ref "RP6") (pin "7") (pintype "passive"))
      (node (ref "U10") (pin "15") (pinfunction "15_15") (pintype "passive"))
    )
    (net (code "205") (name "Net-(RP6-Pad8)") (class "Default")
      (node (ref "RP6") (pin "8") (pintype "passive"))
      (node (ref "U10") (pin "16") (pinfunction "16_16") (pintype "passive"))
    )
    (net (code "206") (name "Net-(RP7-Pad5)") (class "Default")
      (node (ref "RP7") (pin "5") (pintype "passive"))
      (node (ref "U10") (pin "7") (pinfunction "7_7") (pintype "passive"))
    )
    (net (code "207") (name "Net-(RP7-Pad6)") (class "Default")
      (node (ref "RP7") (pin "6") (pintype "passive"))
      (node (ref "U10") (pin "8") (pinfunction "8_8") (pintype "passive"))
    )
    (net (code "208") (name "Net-(RP7-Pad7)") (class "Default")
      (node (ref "RP7") (pin "7") (pintype "passive"))
      (node (ref "U10") (pin "9") (pinfunction "9_9") (pintype "passive"))
    )
    (net (code "209") (name "Net-(RP7-Pad8)") (class "Default")
      (node (ref "RP7") (pin "8") (pintype "passive"))
      (node (ref "U10") (pin "11") (pinfunction "11_11") (pintype "passive"))
    )
    (net (code "210") (name "Net-(U1A-PD0-OSC_IN)") (class "Default")
      (node (ref "C4") (pin "1") (pinfunction "1_1") (pintype "passive"))
      (node (ref "U1") (pin "5") (pinfunction "PD0-OSC_IN_5") (pintype "bidirectional"))
      (node (ref "X1") (pin "1") (pinfunction "1_1") (pintype "passive"))
    )
    (net (code "211") (name "Net-(U1A-PD1)") (class "Default")
      (node (ref "C5") (pin "1") (pinfunction "1_1") (pintype "passive"))
      (node (ref "U1") (pin "6") (pinfunction "PD1_6") (pintype "bidirectional"))
      (node (ref "X1") (pin "2") (pinfunction "2_2") (pintype "passive"))
    )
    (net (code "212") (name "Net-(U1B-VSSA)") (class "Default")
      (node (ref "R2") (pin "2") (pinfunction "2_2") (pintype "passive"))
      (node (ref "U1") (pin "23") (pinfunction "VSS_1_23") (pintype "power_in"))
      (node (ref "U1") (pin "35") (pinfunction "VSS_2_35") (pintype "power_in"))
      (node (ref "U1") (pin "47") (pinfunction "VSS_3_47") (pintype "power_in"))
      (node (ref "U1") (pin "8") (pinfunction "VSSA_8") (pintype "power_in"))
    )
    (net (code "213") (name "Net-(U2A-PDR_ON)") (class "Default")
      (node (ref "R1") (pin "2") (pinfunction "2_2") (pintype "passive"))
      (node (ref "U2") (pin "E7") (pinfunction "PDR_ON_E7") (pintype "input"))
    )
    (net (code "214") (name "Net-(U4-DN1)") (class "Default")
      (node (ref "R14") (pin "2") (pinfunction "2_2") (pintype "passive"))
      (node (ref "U4") (pin "A7") (pinfunction "DN1_A7") (pintype "passive"))
      (node (ref "U4") (pin "B7") (pinfunction "DN2_B7") (pintype "passive"))
    )
    (net (code "215") (name "Net-(U4-DP1)") (class "Default")
      (node (ref "R17") (pin "2") (pinfunction "2_2") (pintype "passive"))
      (node (ref "U4") (pin "A6") (pinfunction "DP1_A6") (pintype "passive"))
      (node (ref "U4") (pin "B6") (pinfunction "DP2_B6") (pintype "passive"))
    )
    (net (code "216") (name "Net-(U7-VIN)") (class "Default")
      (node (ref "1") (pin "2") (pinfunction "2_2") (pintype "passive"))
      (node (ref "2") (pin "2") (pinfunction "2_2") (pintype "passive"))
      (node (ref "FB1") (pin "1") (pinfunction "1_1") (pintype "passive"))
      (node (ref "U7") (pin "3") (pinfunction "VIN_3") (pintype "passive"))
    )
    (net (code "217") (name "Net-(U8-VIN)") (class "Default")
      (node (ref "11") (pin "2") (pinfunction "2_2") (pintype "passive"))
      (node (ref "12") (pin "2") (pinfunction "2_2") (pintype "passive"))
      (node (ref "FB2") (pin "1") (pinfunction "1_1") (pintype "passive"))
      (node (ref "U8") (pin "3") (pinfunction "VIN_3") (pintype "passive"))
    )
    (net (code "218") (name "Net-(U9-VIN)") (class "Default")
      (node (ref "16") (pin "2") (pinfunction "2_2") (pintype "passive"))
      (node (ref "17") (pin "2") (pinfunction "2_2") (pintype "passive"))
      (node (ref "FB3") (pin "1") (pinfunction "1_1") (pintype "passive"))
      (node (ref "U9") (pin "3") (pinfunction "VIN_3") (pintype "passive"))
    )
    (net (code "219") (name "Net-(U11-FB2)") (class "Default")
      (node (ref "C50") (pin "1") (pinfunction "1_1") (pintype "passive"))
      (node (ref "R50") (pin "1") (pinfunction "1_1") (pintype "passive"))
      (node (ref "R54") (pin "2") (pinfunction "2_2") (pintype "passive"))
      (node (ref "U11") (pin "3") (pinfunction "FB2_3") (pintype "passive"))
    )
    (net (code "220") (name "Net-(U11-FB3)") (class "Default")
      (node (ref "C49") (pin "1") (pinfunction "1_1") (pintype "passive"))
      (node (ref "R52") (pin "2") (pinfunction "2_2") (pintype "passive"))
      (node (ref "R55") (pin "1") (pinfunction "1_1") (pintype "passive"))
      (node (ref "U11") (pin "2") (pinfunction "FB3_2") (pintype "passive"))
    )
    (net (code "221") (name "Net-(U11-SW2)") (class "Default")
      (node (ref "L3") (pin "2") (pinfunction "2_2") (pintype "passive"))
      (node (ref "U11") (pin "6") (pinfunction "SW2_6") (pintype "passive"))
    )
    (net (code "222") (name "Net-(U11-SW3)") (class "Default")
      (node (ref "L2") (pin "2") (pinfunction "2_2") (pintype "passive"))
      (node (ref "U11") (pin "20") (pinfunction "SW3_20") (pintype "passive"))
    )
    (net (code "223") (name "Net-(X4-EN{slash}NC)") (class "Default")
      (node (ref "R49") (pin "1") (pinfunction "1_1") (pintype "passive"))
      (node (ref "X4") (pin "1") (pinfunction "EN/NC_1") (pintype "passive"))
    )
    (net (code "224") (name "Net-(X4-VCC)") (class "Default")
      (node (ref "27") (pin "2") (pinfunction "2_2") (pintype "passive"))
      (node (ref "FB7") (pin "2") (pinfunction "2_2") (pintype "passive"))
      (node (ref "X4") (pin "4") (pinfunction "VCC_4") (pintype "passive"))
    )
    (net (code "225") (name "unconnected-(U1A-PA0-WKUP-Pad10)") (class "Default")
      (node (ref "U1") (pin "10") (pinfunction "PA0-WKUP_10") (pintype "bidirectional+no_connect"))
    )
    (net (code "226") (name "unconnected-(U1A-PA1-Pad11)") (class "Default")
      (node (ref "U1") (pin "11") (pinfunction "PA1_11") (pintype "bidirectional+no_connect"))
    )
    (net (code "227") (name "unconnected-(U1A-PA3-Pad13)") (class "Default")
      (node (ref "U1") (pin "13") (pinfunction "PA3_13") (pintype "bidirectional+no_connect"))
    )
    (net (code "228") (name "unconnected-(U1A-PA5-Pad15)") (class "Default")
      (node (ref "U1") (pin "15") (pinfunction "PA5_15") (pintype "bidirectional+no_connect"))
    )
    (net (code "229") (name "unconnected-(U1A-PA7-Pad17)") (class "Default")
      (node (ref "U1") (pin "17") (pinfunction "PA7_17") (pintype "bidirectional+no_connect"))
    )
    (net (code "230") (name "unconnected-(U1A-PA8-Pad29)") (class "Default")
      (node (ref "U1") (pin "29") (pinfunction "PA8_29") (pintype "bidirectional+no_connect"))
    )
    (net (code "231") (name "unconnected-(U1A-PA13-Pad34)") (class "Default")
      (node (ref "U1") (pin "34") (pinfunction "PA13_34") (pintype "bidirectional+no_connect"))
    )
    (net (code "232") (name "unconnected-(U1A-PA14-Pad37)") (class "Default")
      (node (ref "U1") (pin "37") (pinfunction "PA14_37") (pintype "bidirectional+no_connect"))
    )
    (net (code "233") (name "unconnected-(U1A-PA15-Pad38)") (class "Default")
      (node (ref "U1") (pin "38") (pinfunction "PA15_38") (pintype "bidirectional+no_connect"))
    )
    (net (code "234") (name "unconnected-(U1A-PB0-Pad18)") (class "Default")
      (node (ref "U1") (pin "18") (pinfunction "PB0_18") (pintype "bidirectional+no_connect"))
    )
    (net (code "235") (name "unconnected-(U1A-PB1-Pad19)") (class "Default")
      (node (ref "U1") (pin "19") (pinfunction "PB1_19") (pintype "bidirectional+no_connect"))
    )
    (net (code "236") (name "unconnected-(U1A-PB2-Pad20)") (class "Default")
      (node (ref "U1") (pin "20") (pinfunction "PB2_20") (pintype "bidirectional+no_connect"))
    )
    (net (code "237") (name "unconnected-(U1A-PB3-Pad39)") (class "Default")
      (node (ref "U1") (pin "39") (pinfunction "PB3_39") (pintype "bidirectional+no_connect"))
    )
    (net (code "238") (name "unconnected-(U1A-PB4-Pad40)") (class "Default")
      (node (ref "U1") (pin "40") (pinfunction "PB4_40") (pintype "bidirectional+no_connect"))
    )
    (net (code "239") (name "unconnected-(U1A-PB5-Pad41)") (class "Default")
      (node (ref "U1") (pin "41") (pinfunction "PB5_41") (pintype "bidirectional+no_connect"))
    )
    (net (code "240") (name "unconnected-(U1A-PB6-Pad42)") (class "Default")
      (node (ref "U1") (pin "42") (pinfunction "PB6_42") (pintype "bidirectional+no_connect"))
    )
    (net (code "241") (name "unconnected-(U1A-PB7-Pad43)") (class "Default")
      (node (ref "U1") (pin "43") (pinfunction "PB7_43") (pintype "bidirectional+no_connect"))
    )
    (net (code "242") (name "unconnected-(U1A-PB9-Pad46)") (class "Default")
      (node (ref "U1") (pin "46") (pinfunction "PB9_46") (pintype "bidirectional+no_connect"))
    )
    (net (code "243") (name "unconnected-(U1A-PB10-Pad21)") (class "Default")
      (node (ref "U1") (pin "21") (pinfunction "PB10_21") (pintype "bidirectional+no_connect"))
    )
    (net (code "244") (name "unconnected-(U1A-PB11-Pad22)") (class "Default")
      (node (ref "U1") (pin "22") (pinfunction "PB11_22") (pintype "bidirectional+no_connect"))
    )
    (net (code "245") (name "unconnected-(U1A-PB13-Pad26)") (class "Default")
      (node (ref "U1") (pin "26") (pinfunction "PB13_26") (pintype "bidirectional+no_connect"))
    )
    (net (code "246") (name "unconnected-(U1A-PB14-Pad27)") (class "Default")
      (node (ref "U1") (pin "27") (pinfunction "PB14_27") (pintype "bidirectional+no_connect"))
    )
    (net (code "247") (name "unconnected-(U1A-PB15-Pad28)") (class "Default")
      (node (ref "U1") (pin "28") (pinfunction "PB15_28") (pintype "bidirectional+no_connect"))
    )
    (net (code "248") (name "unconnected-(U1A-PC13-TAMPER-RTC-Pad2)") (class "Default")
      (node (ref "U1") (pin "2") (pinfunction "PC13-TAMPER-RTC_2") (pintype "bidirectional+no_connect"))
    )
    (net (code "249") (name "unconnected-(U1A-PC14-OSC32_IN-Pad3)") (class "Default")
      (node (ref "U1") (pin "3") (pinfunction "PC14-OSC32_IN_3") (pintype "bidirectional+no_connect"))
    )
    (net (code "250") (name "unconnected-(U1A-PC15-OSC32_OUT-Pad4)") (class "Default")
      (node (ref "U1") (pin "4") (pinfunction "PC15-OSC32_OUT_4") (pintype "bidirectional+no_connect"))
    )
    (net (code "251") (name "unconnected-(U2A-PA0_C{slash}TIM2_CH1{slash}TIM2_ETR{slash}TIM5_CH1{slash}TIM8_ETR{slash}TIM15_BKIN{slash}USART2_CTS{slash}USART2_NSS{slash}UART4_TX{slash}SDMMC2_CMD{slash}SAI2_SD_B{slash}ETH_MII_CRS{slash}EVENTOUT-PadT1)") (class "Default")
      (node (ref "U2") (pin "T1") (pinfunction "PA0_C/TIM2_CH1/TIM2_ETR/TIM5_CH1/TIM8_ETR/TIM15_BKIN/USART2_CTS/USART2_NSS/UART4_TX/SDMMC2_CMD/SAI2_SD_B/ETH_MII_CRS/EVENTOUT_T1") (pintype "bidirectional+no_connect"))
    )
    (net (code "252") (name "unconnected-(U2A-PA0{slash}TIM2_CH1{slash}TIM2_ETR{slash}TIM5_CH1{slash}TIM8_ETR{slash}TIM15_BKIN{slash}USART2_CTS{slash}USART2_NSS{slash}UART4_TX{slash}SDMMC2_CMD{slash}SAI2_SD_B{slash}ETH_MII_CRS{slash}EVENTOUT-PadN5)") (class "Default")
      (node (ref "U2") (pin "N5") (pinfunction "PA0/TIM2_CH1/TIM2_ETR/TIM5_CH1/TIM8_ETR/TIM15_BKIN/USART2_CTS/USART2_NSS/UART4_TX/SDMMC2_CMD/SAI2_SD_B/ETH_MII_CRS/EVENTOUT_N5") (pintype "bidirectional+no_connect"))
    )
    (net (code "253") (name "unconnected-(U2A-PA1_C{slash}TIM2_CH2{slash}TIM5_CH2{slash}LPTIM3_OUT{slash}TIM15_CH1N{slash}USART2_RTS{slash}USART2_DE{slash}UART4_RX{slash}QUADSPI_BK1_IO3{slash}SAI2_MCLK_B{slash}ETH_MII_RX_CLK{slash}ETH_RMII_REF_CLK{slash}LCD_R2{slash}EVENTOUT-PadT2)") (class "Default")
      (node (ref "U2") (pin "T2") (pinfunction "PA1_C/TIM2_CH2/TIM5_CH2/LPTIM3_OUT/TIM15_CH1N/USART2_RTS/USART2_DE/UART4_RX/QUADSPI_BK1_IO3/SAI2_MCLK_B/ETH_MII_RX_CLK/ETH_RMII_REF_CLK/LCD_R2/EVENTOUT_T2") (pintype "bidirectional+no_connect"))
    )
    (net (code "254") (name "unconnected-(U2A-PA1{slash}TIM2_CH2{slash}TIM5_CH2{slash}LPTIM3_OUT{slash}TIM15_CH1N{slash}USART2_RTS{slash}USART2_DE{slash}UART4_RX{slash}QUADSPI_BK1_IO3{slash}SAI2_MCLK_B{slash}ETH_MII_RX_CLK{slash}ETH_RMII_REF_CLK{slash}LCD_R2{slash}EVENTOUT-PadN4)") (class "Default")
      (node (ref "U2") (pin "N4") (pinfunction "PA1/TIM2_CH2/TIM5_CH2/LPTIM3_OUT/TIM15_CH1N/USART2_RTS/USART2_DE/UART4_RX/QUADSPI_BK1_IO3/SAI2_MCLK_B/ETH_MII_RX_CLK/ETH_RMII_REF_CLK/LCD_R2/EVENTOUT_N4") (pintype "bidirectional+no_connect"))
    )
    (net (code "255") (name "unconnected-(U2A-PA2{slash}TIM2_CH3{slash}TIM5_CH3{slash}LPTIM4_OUT{slash}TIM15_CH1{slash}USART2_TX{slash}SAI2_SCK_B{slash}ETH_MDIO{slash}MDIOS_MDIO{slash}LCD_R1{slash}EVENTOUT-PadN3)") (class "Default")
      (node (ref "U2") (pin "N3") (pinfunction "PA2/TIM2_CH3/TIM5_CH3/LPTIM4_OUT/TIM15_CH1/USART2_TX/SAI2_SCK_B/ETH_MDIO/MDIOS_MDIO/LCD_R1/EVENTOUT_N3") (pintype "bidirectional+no_connect"))
    )
    (net (code "256") (name "unconnected-(U2A-PA3{slash}TIM2_CH4{slash}TIM5_CH4{slash}LPTIM5_OUT{slash}TIM15_CH2{slash}USART2_RX{slash}LCD_B2{slash}OTG_HS_ULPI_D0{slash}ETH_MII_COL{slash}LCD_B5{slash}EVENTOUT-PadU2)") (class "Default")
      (node (ref "U2") (pin "U2") (pinfunction "PA3/TIM2_CH4/TIM5_CH4/LPTIM5_OUT/TIM15_CH2/USART2_RX/LCD_B2/OTG_HS_ULPI_D0/ETH_MII_COL/LCD_B5/EVENTOUT_U2") (pintype "bidirectional+no_connect"))
    )
    (net (code "257") (name "unconnected-(U2A-PA5{slash}D2PWREN{slash}TIM2_CH1{slash}TIM2_ETR{slash}TIM8_CH1N{slash}SPI1_SCK{slash}I2S1_CK{slash}SPI6_SCK{slash}OTG_HS_ULPI_CK{slash}LCD_R4{slash}EVENTOUT-PadT3)") (class "Default")
      (node (ref "U2") (pin "T3") (pinfunction "PA5/D2PWREN/TIM2_CH1/TIM2_ETR/TIM8_CH1N/SPI1_SCK/I2S1_CK/SPI6_SCK/OTG_HS_ULPI_CK/LCD_R4/EVENTOUT_T3") (pintype "bidirectional+no_connect"))
    )
    (net (code "258") (name "unconnected-(U2A-PA7{slash}TIM1_CH1N{slash}TIM3_CH2{slash}TIM8_CH1N{slash}SPI1_MOSI{slash}I2S1_SDO{slash}SPI6_MOSI{slash}TIM14_CH1{slash}ETH_MII_RX_DV{slash}ETH_RMII_CRS_DV{slash}FMC_SDNWE{slash}EVENTOUT-PadR5)") (class "Default")
      (node (ref "U2") (pin "R5") (pinfunction "PA7/TIM1_CH1N/TIM3_CH2/TIM8_CH1N/SPI1_MOSI/I2S1_SDO/SPI6_MOSI/TIM14_CH1/ETH_MII_RX_DV/ETH_RMII_CRS_DV/FMC_SDNWE/EVENTOUT_R5") (pintype "bidirectional+no_connect"))
    )
    (net (code "259") (name "unconnected-(U2A-PA8{slash}MCO1{slash}TIM1_CH1{slash}HRTIM_CHB2{slash}TIM8_BKIN2{slash}I2C3_SCL{slash}USART1_CK{slash}OTG_FS_SOF{slash}UART7_RX{slash}TIM8_BKIN2_COMP12{slash}LCD_B3{slash}LCD_R6{slash}EVENTOUT-PadE15)") (class "Default")
      (node (ref "U2") (pin "E15") (pinfunction "PA8/MCO1/TIM1_CH1/HRTIM_CHB2/TIM8_BKIN2/I2C3_SCL/USART1_CK/OTG_FS_SOF/UART7_RX/TIM8_BKIN2_COMP12/LCD_B3/LCD_R6/EVENTOUT_E15") (pintype "bidirectional+no_connect"))
    )
    (net (code "260") (name "unconnected-(U2A-PA15{slash}JTDI{slash}TIM2_CH1{slash}TIM2_ETR{slash}HRTIM_FLT1{slash}CEC{slash}SPI1_NSS{slash}I2S1_WS{slash}SPI3_NSS{slash}I2S3_WS{slash}SPI6_NSS{slash}UART4_RTS{slash}UART4_DE{slash}UART7_TX{slash}EVENTOUT-PadA14)") (class "Default")
      (node (ref "U2") (pin "A14") (pinfunction "PA15/JTDI/TIM2_CH1/TIM2_ETR/HRTIM_FLT1/CEC/SPI1_NSS/I2S1_WS/SPI3_NSS/I2S3_WS/SPI6_NSS/UART4_RTS/UART4_DE/UART7_TX/EVENTOUT_A14") (pintype "bidirectional+no_connect"))
    )
    (net (code "261") (name "unconnected-(U2A-PB0{slash}TIM1_CH2N{slash}TIM3_CH3{slash}TIM8_CH2N{slash}DFSDM1_CKOUT{slash}UART4_CTS{slash}LCD_R3{slash}OTG_HS_ULPI_D1{slash}ETH_MII_RXD2{slash}LCD_G1{slash}EVENTOUT-PadU5)") (class "Default")
      (node (ref "U2") (pin "U5") (pinfunction "PB0/TIM1_CH2N/TIM3_CH3/TIM8_CH2N/DFSDM1_CKOUT/UART4_CTS/LCD_R3/OTG_HS_ULPI_D1/ETH_MII_RXD2/LCD_G1/EVENTOUT_U5") (pintype "bidirectional+no_connect"))
    )
    (net (code "262") (name "unconnected-(U2A-PB1{slash}TIM1_CH3N{slash}TIM3_CH4{slash}TIM8_CH3N{slash}DFSDM1_DATIN1{slash}LCD_R6{slash}OTG_HS_ULPI_D2{slash}ETH_MII_RXD3{slash}LCD_G0{slash}EVENTOUT-PadT5)") (class "Default")
      (node (ref "U2") (pin "T5") (pinfunction "PB1/TIM1_CH3N/TIM3_CH4/TIM8_CH3N/DFSDM1_DATIN1/LCD_R6/OTG_HS_ULPI_D2/ETH_MII_RXD3/LCD_G0/EVENTOUT_T5") (pintype "bidirectional+no_connect"))
    )
    (net (code "263") (name "unconnected-(U2A-PB2{slash}RTC_OUT{slash}SAI1_D1{slash}DFSDM1_CKIN1{slash}SAI1_SD_A{slash}SPI3_MOSI{slash}I2S3_SDO{slash}SAI4_SD_A{slash}QUADSPI_CLK{slash}SAI4_D1{slash}EVENTOUT-PadR6)") (class "Default")
      (node (ref "U2") (pin "R6") (pinfunction "PB2/RTC_OUT/SAI1_D1/DFSDM1_CKIN1/SAI1_SD_A/SPI3_MOSI/I2S3_SDO/SAI4_SD_A/QUADSPI_CLK/SAI4_D1/EVENTOUT_R6") (pintype "bidirectional+no_connect"))
    )
    (net (code "264") (name "unconnected-(U2A-PB3{slash}JTDO{slash}TRACESWO{slash}TIM2_CH2{slash}HRTIM_FLT4{slash}SPI1_SCK{slash}I2S1_CK{slash}SPI3_SCK{slash}I2S3_CK{slash}SPI6_SCK{slash}SDMMC2_D2{slash}CRS_SYNC{slash}UART7_RX{slash}EVENTOUT-PadC6)") (class "Default")
      (node (ref "U2") (pin "C6") (pinfunction "PB3/JTDO/TRACESWO/TIM2_CH2/HRTIM_FLT4/SPI1_SCK/I2S1_CK/SPI3_SCK/I2S3_CK/SPI6_SCK/SDMMC2_D2/CRS_SYNC/UART7_RX/EVENTOUT_C6") (pintype "bidirectional+no_connect"))
    )
    (net (code "265") (name "unconnected-(U2A-PB4{slash}NJTRST{slash}TIM16_BKIN{slash}TIM3_CH1{slash}HRTIM_EEV6{slash}SPI1_MISO{slash}I2S1_SDI{slash}SPI3_MISO{slash}I2S3_SDI{slash}SPI2_NSS{slash}I2S2_WS{slash}SPI6_MISO{slash}SDMMC2_D3{slash}UART7_TX{slash}EVENTOUT-PadB7)") (class "Default")
      (node (ref "U2") (pin "B7") (pinfunction "PB4/NJTRST/TIM16_BKIN/TIM3_CH1/HRTIM_EEV6/SPI1_MISO/I2S1_SDI/SPI3_MISO/I2S3_SDI/SPI2_NSS/I2S2_WS/SPI6_MISO/SDMMC2_D3/UART7_TX/EVENTOUT_B7") (pintype "bidirectional+no_connect"))
    )
    (net (code "266") (name "unconnected-(U2A-PB5{slash}TIM17_BKIN{slash}TIM3_CH2{slash}HRTIM_EEV7{slash}I2C1_SMBA{slash}SPI1_MOSI{slash}I2S1_SDO{slash}I2C4_SMBA{slash}SPI3_MOSI{slash}I2S3_SDO{slash}SPI6_MOSI{slash}FDCAN2_RX{slash}OTG_HS_ULPI_D7{slash}ETH_PPS_OUT{slash}FMC_SDCKE1{slash}DCMI_D10{slash}UART5_RX{slash}EVENTOUT-PadA5)") (class "Default")
      (node (ref "U2") (pin "A5") (pinfunction "PB5/TIM17_BKIN/TIM3_CH2/HRTIM_EEV7/I2C1_SMBA/SPI1_MOSI/I2S1_SDO/I2C4_SMBA/SPI3_MOSI/I2S3_SDO/SPI6_MOSI/FDCAN2_RX/OTG_HS_ULPI_D7/ETH_PPS_OUT/FMC_SDCKE1/DCMI_D10/UART5_RX/EVENTOUT_A5") (pintype "bidirectional+no_connect"))
    )
    (net (code "267") (name "unconnected-(U2A-PB6{slash}TIM16_CH1N{slash}TIM4_CH1{slash}HRTIM_EEV8{slash}I2C1_SCL{slash}CEC{slash}I2C4_SCL{slash}USART1_TX{slash}LPUART1_TX{slash}FDCAN2_TX{slash}QUADSPI_BK1_NCS{slash}DFSDM1_DATIN5{slash}FMC_SDNE1{slash}DCMI_D5{slash}UART5_TX{slash}EVENTOUT-PadB5)") (class "Default")
      (node (ref "U2") (pin "B5") (pinfunction "PB6/TIM16_CH1N/TIM4_CH1/HRTIM_EEV8/I2C1_SCL/CEC/I2C4_SCL/USART1_TX/LPUART1_TX/FDCAN2_TX/QUADSPI_BK1_NCS/DFSDM1_DATIN5/FMC_SDNE1/DCMI_D5/UART5_TX/EVENTOUT_B5") (pintype "bidirectional+no_connect"))
    )
    (net (code "268") (name "unconnected-(U2A-PB7{slash}TIM17_CH1N{slash}TIM4_CH2{slash}HRTIM_EEV9{slash}I2C1_SDA{slash}I2C4_SDA{slash}USART1_RX{slash}LPUART1_RX{slash}FDCAN2_TXFD_MODE{slash}DFSDM1_CKIN5{slash}FMC_NL{slash}DCMI_VSYNC{slash}EVENTOUT-PadC5)") (class "Default")
      (node (ref "U2") (pin "C5") (pinfunction "PB7/TIM17_CH1N/TIM4_CH2/HRTIM_EEV9/I2C1_SDA/I2C4_SDA/USART1_RX/LPUART1_RX/FDCAN2_TXFD_MODE/DFSDM1_CKIN5/FMC_NL/DCMI_VSYNC/EVENTOUT_C5") (pintype "bidirectional+no_connect"))
    )
    (net (code "269") (name "unconnected-(U2A-PB8{slash}TIM16_CH1{slash}TIM4_CH3{slash}DFSDM1_CKIN7{slash}I2C1_SCL{slash}I2C4_SCL{slash}SDMMC1_CKIN{slash}UART4_RX{slash}FDCAN1_RX{slash}SDMMC2_D4{slash}ETH_MII_TXD3{slash}SDMMC1_D4{slash}DCMI_D6{slash}LCD_B6{slash}EVENTOUT-PadD5)") (class "Default")
      (node (ref "U2") (pin "D5") (pinfunction "PB8/TIM16_CH1/TIM4_CH3/DFSDM1_CKIN7/I2C1_SCL/I2C4_SCL/SDMMC1_CKIN/UART4_RX/FDCAN1_RX/SDMMC2_D4/ETH_MII_TXD3/SDMMC1_D4/DCMI_D6/LCD_B6/EVENTOUT_D5") (pintype "bidirectional+no_connect"))
    )
    (net (code "270") (name "unconnected-(U2A-PB9{slash}TIM17_CH1{slash}TIM4_CH4{slash}DFSDM1_DATIN7{slash}I2C1_SDA{slash}SPI2_NSS{slash}I2S2_WS{slash}I2C4_SDA{slash}SDMMC1_CDIR{slash}UART4_TX{slash}FDCAN1_TX{slash}SDMMC2_D5{slash}I2C4_SMBA{slash}SDMMC1_D5{slash}DCMI_D7{slash}LCD_B7{slash}EVENTOUT-PadD4)") (class "Default")
      (node (ref "U2") (pin "D4") (pinfunction "PB9/TIM17_CH1/TIM4_CH4/DFSDM1_DATIN7/I2C1_SDA/SPI2_NSS/I2S2_WS/I2C4_SDA/SDMMC1_CDIR/UART4_TX/FDCAN1_TX/SDMMC2_D5/I2C4_SMBA/SDMMC1_D5/DCMI_D7/LCD_B7/EVENTOUT_D4") (pintype "bidirectional+no_connect"))
    )
    (net (code "271") (name "unconnected-(U2A-PB10{slash}TIM2_CH3{slash}HRTIM_SCOUT{slash}LPTIM2_IN1{slash}I2C2_SCL{slash}SPI2_SCK{slash}I2S2_CK{slash}DFSDM1_DATIN7{slash}USART3_TX{slash}QUADSPI_BK1_NCS{slash}OTG_HS_ULPI_D3{slash}ETH_MII_RX_ER{slash}LCD_G4{slash}EVENTOUT-PadP11)") (class "Default")
      (node (ref "U2") (pin "P11") (pinfunction "PB10/TIM2_CH3/HRTIM_SCOUT/LPTIM2_IN1/I2C2_SCL/SPI2_SCK/I2S2_CK/DFSDM1_DATIN7/USART3_TX/QUADSPI_BK1_NCS/OTG_HS_ULPI_D3/ETH_MII_RX_ER/LCD_G4/EVENTOUT_P11") (pintype "bidirectional+no_connect"))
    )
    (net (code "272") (name "unconnected-(U2A-PB11{slash}TIM2_CH4{slash}HRTIM_SCIN{slash}LPTIM2_ETR{slash}I2C2_SDA{slash}DFSDM1_CKIN7{slash}USART3_RX{slash}OTG_HS_ULPI_D4{slash}ETH_MII_TX_EN{slash}ETH_RMII_TX_EN{slash}LCD_G5{slash}EVENTOUT-PadP12)") (class "Default")
      (node (ref "U2") (pin "P12") (pinfunction "PB11/TIM2_CH4/HRTIM_SCIN/LPTIM2_ETR/I2C2_SDA/DFSDM1_CKIN7/USART3_RX/OTG_HS_ULPI_D4/ETH_MII_TX_EN/ETH_RMII_TX_EN/LCD_G5/EVENTOUT_P12") (pintype "bidirectional+no_connect"))
    )
    (net (code "273") (name "unconnected-(U2A-PB12{slash}TIM1_BKIN{slash}I2C2_SMBA{slash}SPI2_NSS{slash}I2S2_WS{slash}DFSDM1_DATIN1{slash}USART3_CK{slash}FDCAN2_RX{slash}OTG_HS_ULPI_D5{slash}ETH_MII_TXD0{slash}ETH_RMII_TXD0{slash}OTG_HS_ID{slash}TIM1_BKIN_COMP12{slash}UART5_RX{slash}EVENTOUT-PadT14)") (class "Default")
      (node (ref "U2") (pin "T14") (pinfunction "PB12/TIM1_BKIN/I2C2_SMBA/SPI2_NSS/I2S2_WS/DFSDM1_DATIN1/USART3_CK/FDCAN2_RX/OTG_HS_ULPI_D5/ETH_MII_TXD0/ETH_RMII_TXD0/OTG_HS_ID/TIM1_BKIN_COMP12/UART5_RX/EVENTOUT_T14") (pintype "bidirectional+no_connect"))
    )
    (net (code "274") (name "unconnected-(U2A-PB14{slash}TIM1_CH2N{slash}TIM12_CH1{slash}TIM8_CH2N{slash}USART1_TX{slash}SPI2_MISO{slash}I2S2_SDI{slash}DFSDM1_DATIN2{slash}USART3_RTS{slash}USART3_DE{slash}UART4_RTS{slash}UART4_DE{slash}SDMMC2_D0{slash}OTG_HS_DM{slash}EVENTOUT-PadU15)") (class "Default")
      (node (ref "U2") (pin "U15") (pinfunction "PB14/TIM1_CH2N/TIM12_CH1/TIM8_CH2N/USART1_TX/SPI2_MISO/I2S2_SDI/DFSDM1_DATIN2/USART3_RTS/USART3_DE/UART4_RTS/UART4_DE/SDMMC2_D0/OTG_HS_DM/EVENTOUT_U15") (pintype "bidirectional+no_connect"))
    )
    (net (code "275") (name "unconnected-(U2A-PB15{slash}RTC_REFIN{slash}TIM1_CH3N{slash}TIM12_CH2{slash}TIM8_CH3N{slash}USART1_RX{slash}SPI2_MOSI{slash}I2S2_SDO{slash}DFSDM1_CKIN2{slash}UART4_CTS{slash}SDMMC2_D1{slash}OTG_HS_DP{slash}EVENTOUT-PadT15)") (class "Default")
      (node (ref "U2") (pin "T15") (pinfunction "PB15/RTC_REFIN/TIM1_CH3N/TIM12_CH2/TIM8_CH3N/USART1_RX/SPI2_MOSI/I2S2_SDO/DFSDM1_CKIN2/UART4_CTS/SDMMC2_D1/OTG_HS_DP/EVENTOUT_T15") (pintype "bidirectional+no_connect"))
    )
    (net (code "276") (name "unconnected-(U2B-PC1{slash}TRACED0{slash}SAI1_D1{slash}DFSDM1_DATIN0{slash}DFSDM1_CKIN4{slash}SPI2_MOSI{slash}I2S2_SDO{slash}SAI1_SD_A{slash}SAI4_SD_A{slash}SDMMC2_CK{slash}SAI4_D1{slash}ETH_MDC{slash}MDIOS_MDC{slash}EVENTOUT-PadM2)") (class "Default")
      (node (ref "U2") (pin "M2") (pinfunction "PC1/TRACED0/SAI1_D1/DFSDM1_DATIN0/DFSDM1_CKIN4/SPI2_MOSI/I2S2_SDO/SAI1_SD_A/SAI4_SD_A/SDMMC2_CK/SAI4_D1/ETH_MDC/MDIOS_MDC/EVENTOUT_M2") (pintype "bidirectional+no_connect"))
    )
    (net (code "277") (name "unconnected-(U2B-PC2_C{slash}CDSLEEP{slash}DFSDM1_CKIN1{slash}SPI2_MISO{slash}I2S2_SDI{slash}DFSDM1_CKOUT{slash}OTG_HS_ULPI_DIR{slash}ETH_MII_TXD2{slash}FMC_SDNE0{slash}EVENTOUT-PadR1)") (class "Default")
      (node (ref "U2") (pin "R1") (pinfunction "PC2_C/CDSLEEP/DFSDM1_CKIN1/SPI2_MISO/I2S2_SDI/DFSDM1_CKOUT/OTG_HS_ULPI_DIR/ETH_MII_TXD2/FMC_SDNE0/EVENTOUT_R1") (pintype "bidirectional+no_connect"))
    )
    (net (code "278") (name "unconnected-(U2B-PC2{slash}CDSLEEP{slash}DFSDM1_CKIN1{slash}SPI2_MISO{slash}I2S2_SDI{slash}DFSDM1_CKOUT{slash}OTG_HS_ULPI_DIR{slash}ETH_MII_TXD2{slash}FMC_SDNE0{slash}EVENTOUT-PadM3)") (class "Default")
      (node (ref "U2") (pin "M3") (pinfunction "PC2/CDSLEEP/DFSDM1_CKIN1/SPI2_MISO/I2S2_SDI/DFSDM1_CKOUT/OTG_HS_ULPI_DIR/ETH_MII_TXD2/FMC_SDNE0/EVENTOUT_M3") (pintype "bidirectional+no_connect"))
    )
    (net (code "279") (name "unconnected-(U2B-PC3_C{slash}CSLEEP{slash}DFSDM1_DATIN1{slash}SPI2_MOSI{slash}I2S2_SDO{slash}OTG_HS_ULPI_NXT{slash}ETH_MII_TX_CLK{slash}FMC_SDCKE0{slash}EVENTOUT-PadR2)") (class "Default")
      (node (ref "U2") (pin "R2") (pinfunction "PC3_C/CSLEEP/DFSDM1_DATIN1/SPI2_MOSI/I2S2_SDO/OTG_HS_ULPI_NXT/ETH_MII_TX_CLK/FMC_SDCKE0/EVENTOUT_R2") (pintype "bidirectional+no_connect"))
    )
    (net (code "280") (name "unconnected-(U2B-PC3{slash}CSLEEP{slash}DFSDM1_DATIN1{slash}SPI2_MOSI{slash}I2S2_SDO{slash}OTG_HS_ULPI_NXT{slash}ETH_MII_TX_CLK{slash}FMC_SDCKE0{slash}EVENTOUT-PadM4)") (class "Default")
      (node (ref "U2") (pin "M4") (pinfunction "PC3/CSLEEP/DFSDM1_DATIN1/SPI2_MOSI/I2S2_SDO/OTG_HS_ULPI_NXT/ETH_MII_TX_CLK/FMC_SDCKE0/EVENTOUT_M4") (pintype "bidirectional+no_connect"))
    )
    (net (code "281") (name "unconnected-(U2B-PC4{slash}DFSDM1_CKIN2{slash}I2S1_MCK{slash}SPDIFRX1_IN3{slash}ETH_MII_RXD0{slash}ETH_RMII_RXD0{slash}FMC_SDNE0{slash}EVENTOUT-PadT4)") (class "Default")
      (node (ref "U2") (pin "T4") (pinfunction "PC4/DFSDM1_CKIN2/I2S1_MCK/SPDIFRX1_IN3/ETH_MII_RXD0/ETH_RMII_RXD0/FMC_SDNE0/EVENTOUT_T4") (pintype "bidirectional+no_connect"))
    )
    (net (code "282") (name "unconnected-(U2B-PC5{slash}SAI1_D3{slash}DFSDM1_DATIN2{slash}SPDIFRX1_IN4{slash}SAI4_D3{slash}ETH_MII_RXD1{slash}ETH_RMII_RXD1{slash}FMC_SDCKE0{slash}COMP1_OUT{slash}EVENTOUT-PadU4)") (class "Default")
      (node (ref "U2") (pin "U4") (pinfunction "PC5/SAI1_D3/DFSDM1_DATIN2/SPDIFRX1_IN4/SAI4_D3/ETH_MII_RXD1/ETH_RMII_RXD1/FMC_SDCKE0/COMP1_OUT/EVENTOUT_U4") (pintype "bidirectional+no_connect"))
    )
    (net (code "283") (name "unconnected-(U2B-PD4{slash}HRTIM_FLT3{slash}SAI3_FS_A{slash}USART2_RTS{slash}USART2_DE{slash}FDCAN1_RXFD_MODE{slash}FMC_NOE{slash}EVENTOUT-PadA12)") (class "Default")
      (node (ref "U2") (pin "A12") (pinfunction "PD4/HRTIM_FLT3/SAI3_FS_A/USART2_RTS/USART2_DE/FDCAN1_RXFD_MODE/FMC_NOE/EVENTOUT_A12") (pintype "bidirectional+no_connect"))
    )
    (net (code "284") (name "unconnected-(U2B-PD5{slash}HRTIM_EEV3{slash}USART2_TX{slash}FDCAN1_TXFD_MODE{slash}FMC_NWE{slash}EVENTOUT-PadA11)") (class "Default")
      (node (ref "U2") (pin "A11") (pinfunction "PD5/HRTIM_EEV3/USART2_TX/FDCAN1_TXFD_MODE/FMC_NWE/EVENTOUT_A11") (pintype "bidirectional+no_connect"))
    )
    (net (code "285") (name "unconnected-(U2B-PD6{slash}SAI1_D1{slash}DFSDM1_CKIN4{slash}DFSDM1_DATIN1{slash}SPI3_MOSI{slash}I2S3_SDO{slash}SAI1_SD_A{slash}USART2_RX{slash}SAI4_SD_A{slash}FDCAN2_RXFD_MODE{slash}SAI4_D1{slash}SDMMC2_CK{slash}FMC_NWAIT{slash}DCMI_D10{slash}LCD_B2{slash}EVENTOUT-PadB11)") (class "Default")
      (node (ref "U2") (pin "B11") (pinfunction "PD6/SAI1_D1/DFSDM1_CKIN4/DFSDM1_DATIN1/SPI3_MOSI/I2S3_SDO/SAI1_SD_A/USART2_RX/SAI4_SD_A/FDCAN2_RXFD_MODE/SAI4_D1/SDMMC2_CK/FMC_NWAIT/DCMI_D10/LCD_B2/EVENTOUT_B11") (pintype "bidirectional+no_connect"))
    )
    (net (code "286") (name "unconnected-(U2B-PD7{slash}DFSDM1_DATIN4{slash}SPI1_MOSI{slash}I2S1_SDO{slash}DFSDM1_CKIN1{slash}USART2_CK{slash}SPDIFRX1_IN1{slash}SDMMC2_CMD{slash}FMC_NE1{slash}EVENTOUT-PadC11)") (class "Default")
      (node (ref "U2") (pin "C11") (pinfunction "PD7/DFSDM1_DATIN4/SPI1_MOSI/I2S1_SDO/DFSDM1_CKIN1/USART2_CK/SPDIFRX1_IN1/SDMMC2_CMD/FMC_NE1/EVENTOUT_C11") (pintype "bidirectional+no_connect"))
    )
    (net (code "287") (name "unconnected-(U2B-PD11{slash}LPTIM2_IN2{slash}I2C4_SMBA{slash}USART3_CTS{slash}USART3_NSS{slash}QUADSPI_BK1_IO0{slash}SAI2_SD_A{slash}FMC_A16{slash}EVENTOUT-PadR15)") (class "Default")
      (node (ref "U2") (pin "R15") (pinfunction "PD11/LPTIM2_IN2/I2C4_SMBA/USART3_CTS/USART3_NSS/QUADSPI_BK1_IO0/SAI2_SD_A/FMC_A16/EVENTOUT_R15") (pintype "bidirectional+no_connect"))
    )
    (net (code "288") (name "unconnected-(U2B-PD12{slash}LPTIM1_IN1{slash}TIM4_CH1{slash}LPTIM2_IN1{slash}I2C4_SCL{slash}USART3_RTS{slash}USART3_DE{slash}QUADSPI_BK1_IO1{slash}SAI2_FS_A{slash}FMC_A17{slash}EVENTOUT-PadR16)") (class "Default")
      (node (ref "U2") (pin "R16") (pinfunction "PD12/LPTIM1_IN1/TIM4_CH1/LPTIM2_IN1/I2C4_SCL/USART3_RTS/USART3_DE/QUADSPI_BK1_IO1/SAI2_FS_A/FMC_A17/EVENTOUT_R16") (pintype "bidirectional+no_connect"))
    )
    (net (code "289") (name "unconnected-(U2B-PD13{slash}LPTIM1_OUT{slash}TIM4_CH2{slash}I2C4_SDA{slash}QUADSPI_BK1_IO3{slash}SAI2_SCK_A{slash}FMC_A18{slash}EVENTOUT-PadR17)") (class "Default")
      (node (ref "U2") (pin "R17") (pinfunction "PD13/LPTIM1_OUT/TIM4_CH2/I2C4_SDA/QUADSPI_BK1_IO3/SAI2_SCK_A/FMC_A18/EVENTOUT_R17") (pintype "bidirectional+no_connect"))
    )
    (net (code "290") (name "unconnected-(U2C-PE2{slash}TRACECLK{slash}SAI1_CK1{slash}SPI4_SCK{slash}SAI1_MCLK_A{slash}SAI4_MCLK_A{slash}QUADSPI_BK1_IO2{slash}SAI4_CK1{slash}ETH_MII_TXD3{slash}FMC_A23{slash}EVENTOUT-PadC3)") (class "Default")
      (node (ref "U2") (pin "C3") (pinfunction "PE2/TRACECLK/SAI1_CK1/SPI4_SCK/SAI1_MCLK_A/SAI4_MCLK_A/QUADSPI_BK1_IO2/SAI4_CK1/ETH_MII_TXD3/FMC_A23/EVENTOUT_C3") (pintype "bidirectional+no_connect"))
    )
    (net (code "291") (name "unconnected-(U2C-PE3{slash}TRACED0{slash}TIM15_BKIN{slash}SAI1_SD_B{slash}SAI4_SD_B{slash}FMC_A19{slash}EVENTOUT-PadD3)") (class "Default")
      (node (ref "U2") (pin "D3") (pinfunction "PE3/TRACED0/TIM15_BKIN/SAI1_SD_B/SAI4_SD_B/FMC_A19/EVENTOUT_D3") (pintype "bidirectional+no_connect"))
    )
    (net (code "292") (name "unconnected-(U2D-PG12{slash}LPTIM1_IN1{slash}HRTIM_EEV5{slash}SPI6_MISO{slash}USART6_RTS{slash}USART6_DE{slash}SPDIFRX1_IN2{slash}LCD_B4{slash}ETH_MII_TXD1{slash}ETH_RMII_TXD1{slash}FMC_NE4{slash}LCD_B1{slash}EVENTOUT-PadC9)") (class "Default")
      (node (ref "U2") (pin "C9") (pinfunction "PG12/LPTIM1_IN1/HRTIM_EEV5/SPI6_MISO/USART6_RTS/USART6_DE/SPDIFRX1_IN2/LCD_B4/ETH_MII_TXD1/ETH_RMII_TXD1/FMC_NE4/LCD_B1/EVENTOUT_C9") (pintype "bidirectional+no_connect"))
    )
    (net (code "293") (name "unconnected-(U2D-PG13{slash}TRACED0{slash}LPTIM1_OUT{slash}HRTIM_EEV10{slash}SPI6_SCK{slash}USART6_CTS{slash}USART6_NSS{slash}ETH_MII_TXD0{slash}ETH_RMII_TXD0{slash}FMC_A24{slash}LCD_R0{slash}EVENTOUT-PadD9)") (class "Default")
      (node (ref "U2") (pin "D9") (pinfunction "PG13/TRACED0/LPTIM1_OUT/HRTIM_EEV10/SPI6_SCK/USART6_CTS/USART6_NSS/ETH_MII_TXD0/ETH_RMII_TXD0/FMC_A24/LCD_R0/EVENTOUT_D9") (pintype "bidirectional+no_connect"))
    )
    (net (code "294") (name "unconnected-(U2D-PG14{slash}TRACED1{slash}LPTIM1_ETR{slash}SPI6_MOSI{slash}USART6_TX{slash}QUADSPI_BK2_IO3{slash}ETH_MII_TXD1{slash}ETH_RMII_TXD1{slash}FMC_A25{slash}LCD_B0{slash}EVENTOUT-PadD8)") (class "Default")
      (node (ref "U2") (pin "D8") (pinfunction "PG14/TRACED1/LPTIM1_ETR/SPI6_MOSI/USART6_TX/QUADSPI_BK2_IO3/ETH_MII_TXD1/ETH_RMII_TXD1/FMC_A25/LCD_B0/EVENTOUT_D8") (pintype "bidirectional+no_connect"))
    )
    (net (code "295") (name "unconnected-(U2D-PH7{slash}I2C3_SCL{slash}SPI5_MISO{slash}ETH_MII_RXD3{slash}FMC_SDCKE1{slash}DCMI_D9{slash}EVENTOUT-PadU13)") (class "Default")
      (node (ref "U2") (pin "U13") (pinfunction "PH7/I2C3_SCL/SPI5_MISO/ETH_MII_RXD3/FMC_SDCKE1/DCMI_D9/EVENTOUT_U13") (pintype "bidirectional+no_connect"))
    )
    (net (code "296") (name "unconnected-(U2F-NC-PadE1)") (class "Default")
      (node (ref "U2") (pin "E1") (pinfunction "NC_E1") (pintype "passive+no_connect"))
    )
    (net (code "297") (name "unconnected-(U2F-NC-PadK16)") (class "Default")
      (node (ref "U2") (pin "K16") (pinfunction "NC_K16") (pintype "passive+no_connect"))
    )
    (net (code "298") (name "unconnected-(U2F-NC-PadK17)") (class "Default")
      (node (ref "U2") (pin "K17") (pinfunction "NC_K17") (pintype "passive+no_connect"))
    )
    (net (code "299") (name "unconnected-(U2F-NC-PadL16)") (class "Default")
      (node (ref "U2") (pin "L16") (pinfunction "NC_L16") (pintype "passive+no_connect"))
    )
    (net (code "300") (name "unconnected-(U2F-NC-PadL17)") (class "Default")
      (node (ref "U2") (pin "L17") (pinfunction "NC_L17") (pintype "passive+no_connect"))
    )
    (net (code "301") (name "unconnected-(U2F-NC-PadM16)") (class "Default")
      (node (ref "U2") (pin "M16") (pinfunction "NC_M16") (pintype "passive+no_connect"))
    )
    (net (code "302") (name "unconnected-(U2F-NC-PadM17)") (class "Default")
      (node (ref "U2") (pin "M17") (pinfunction "NC_M17") (pintype "passive+no_connect"))
    )
    (net (code "303") (name "unconnected-(U2F-NC-PadN17)") (class "Default")
      (node (ref "U2") (pin "N17") (pinfunction "NC_N17") (pintype "passive+no_connect"))
    )
    (net (code "304") (name "unconnected-(U2F-NC1-PadF1)") (class "Default")
      (node (ref "U2") (pin "F1") (pinfunction "NC1_F1") (pintype "passive+no_connect"))
    )
    (net (code "305") (name "unconnected-(U2F-NC2-PadG2)") (class "Default")
      (node (ref "U2") (pin "G2") (pinfunction "NC2_G2") (pintype "passive+no_connect"))
    )
    (net (code "306") (name "unconnected-(U3-NU-PadK2)") (class "Default")
      (node (ref "U3") (pin "K2") (pinfunction "NU_K2") (pintype "bidirectional+no_connect"))
    )
    (net (code "307") (name "unconnected-(U4-CC1-PadA5)") (class "Default")
      (node (ref "U4") (pin "A5") (pinfunction "CC1_A5") (pintype "passive+no_connect"))
    )
    (net (code "308") (name "unconnected-(U4-CC2-PadB5)") (class "Default")
      (node (ref "U4") (pin "B5") (pinfunction "CC2_B5") (pintype "passive+no_connect"))
    )
    (net (code "309") (name "unconnected-(U4-SBU1-PadA8)") (class "Default")
      (node (ref "U4") (pin "A8") (pinfunction "SBU1_A8") (pintype "passive+no_connect"))
    )
    (net (code "310") (name "unconnected-(U4-SBU2-PadB8)") (class "Default")
      (node (ref "U4") (pin "B8") (pinfunction "SBU2_B8") (pintype "passive+no_connect"))
    )
    (net (code "311") (name "unconnected-(U5-CC1-PadA5)") (class "Default")
      (node (ref "U5") (pin "A5") (pinfunction "CC1_A5") (pintype "passive+no_connect"))
    )
    (net (code "312") (name "unconnected-(U5-CC2-PadB5)") (class "Default")
      (node (ref "U5") (pin "B5") (pinfunction "CC2_B5") (pintype "passive+no_connect"))
    )
    (net (code "313") (name "unconnected-(U5-SBU1-PadA8)") (class "Default")
      (node (ref "U5") (pin "A8") (pinfunction "SBU1_A8") (pintype "passive+no_connect"))
    )
    (net (code "314") (name "unconnected-(U5-SBU2-PadB8)") (class "Default")
      (node (ref "U5") (pin "B8") (pinfunction "SBU2_B8") (pintype "passive+no_connect"))
    )
    (net (code "315") (name "unconnected-(U10-Pad1)") (class "Default")
      (node (ref "U10") (pin "1") (pinfunction "1_1") (pintype "passive+no_connect"))
    )
    (net (code "316") (name "unconnected-(U10-Pad2)") (class "Default")
      (node (ref "U10") (pin "2") (pinfunction "2_2") (pintype "passive+no_connect"))
    )
    (net (code "317") (name "unconnected-(U10-Pad3)") (class "Default")
      (node (ref "U10") (pin "3") (pinfunction "3_3") (pintype "passive+no_connect"))
    )
    (net (code "318") (name "unconnected-(U10-Pad4)") (class "Default")
      (node (ref "U10") (pin "4") (pinfunction "4_4") (pintype "passive+no_connect"))
    )
    (net (code "319") (name "unconnected-(U10-Pad6)") (class "Default")
      (node (ref "U10") (pin "6") (pinfunction "6_6") (pintype "passive+no_connect"))
    )
    (net (code "320") (name "unconnected-(U11-EN1-Pad9)") (class "Default")
      (node (ref "U11") (pin "9") (pinfunction "EN1_9") (pintype "passive+no_connect"))
    )
    (net (code "321") (name "unconnected-(U11-FB1-Pad14)") (class "Default")
      (node (ref "U11") (pin "14") (pinfunction "FB1_14") (pintype "passive+no_connect"))
    )
    (net (code "322") (name "unconnected-(U11-NC-Pad1)") (class "Default")
      (node (ref "U11") (pin "1") (pinfunction "NC_1") (pintype "passive+no_connect"))
    )
    (net (code "323") (name "unconnected-(U11-NC-Pad4)") (class "Default")
      (node (ref "U11") (pin "4") (pinfunction "NC_4") (pintype "passive+no_connect"))
    )
    (net (code "324") (name "unconnected-(U11-NC-Pad5)") (class "Default")
      (node (ref "U11") (pin "5") (pinfunction "NC_5") (pintype "passive+no_connect"))
    )
    (net (code "325") (name "unconnected-(U11-NC-Pad12)") (class "Default")
      (node (ref "U11") (pin "12") (pinfunction "NC_12") (pintype "passive+no_connect"))
    )
    (net (code "326") (name "unconnected-(U11-NC-Pad13)") (class "Default")
      (node (ref "U11") (pin "13") (pinfunction "NC_13") (pintype "passive+no_connect"))
    )
    (net (code "327") (name "unconnected-(U11-NC-Pad15)") (class "Default")
      (node (ref "U11") (pin "15") (pinfunction "NC_15") (pintype "passive+no_connect"))
    )
    (net (code "328") (name "unconnected-(U11-NC-Pad16)") (class "Default")
      (node (ref "U11") (pin "16") (pinfunction "NC_16") (pintype "passive+no_connect"))
    )
    (net (code "329") (name "unconnected-(U11-NC-Pad17)") (class "Default")
      (node (ref "U11") (pin "17") (pinfunction "NC_17") (pintype "passive+no_connect"))
    )
    (net (code "330") (name "unconnected-(U11-SW1-Pad11)") (class "Default")
      (node (ref "U11") (pin "11") (pinfunction "SW1_11") (pintype "passive+no_connect"))
    )
    (net (code "331") (name "unconnected-(U11-VIN1-Pad10)") (class "Default")
      (node (ref "U11") (pin "10") (pinfunction "VIN1_10") (pintype "passive+no_connect"))
    )
  )
)
